# Revised_Schematic.net
KiCad netlist of a schematic drawn in EasyEDA Pro
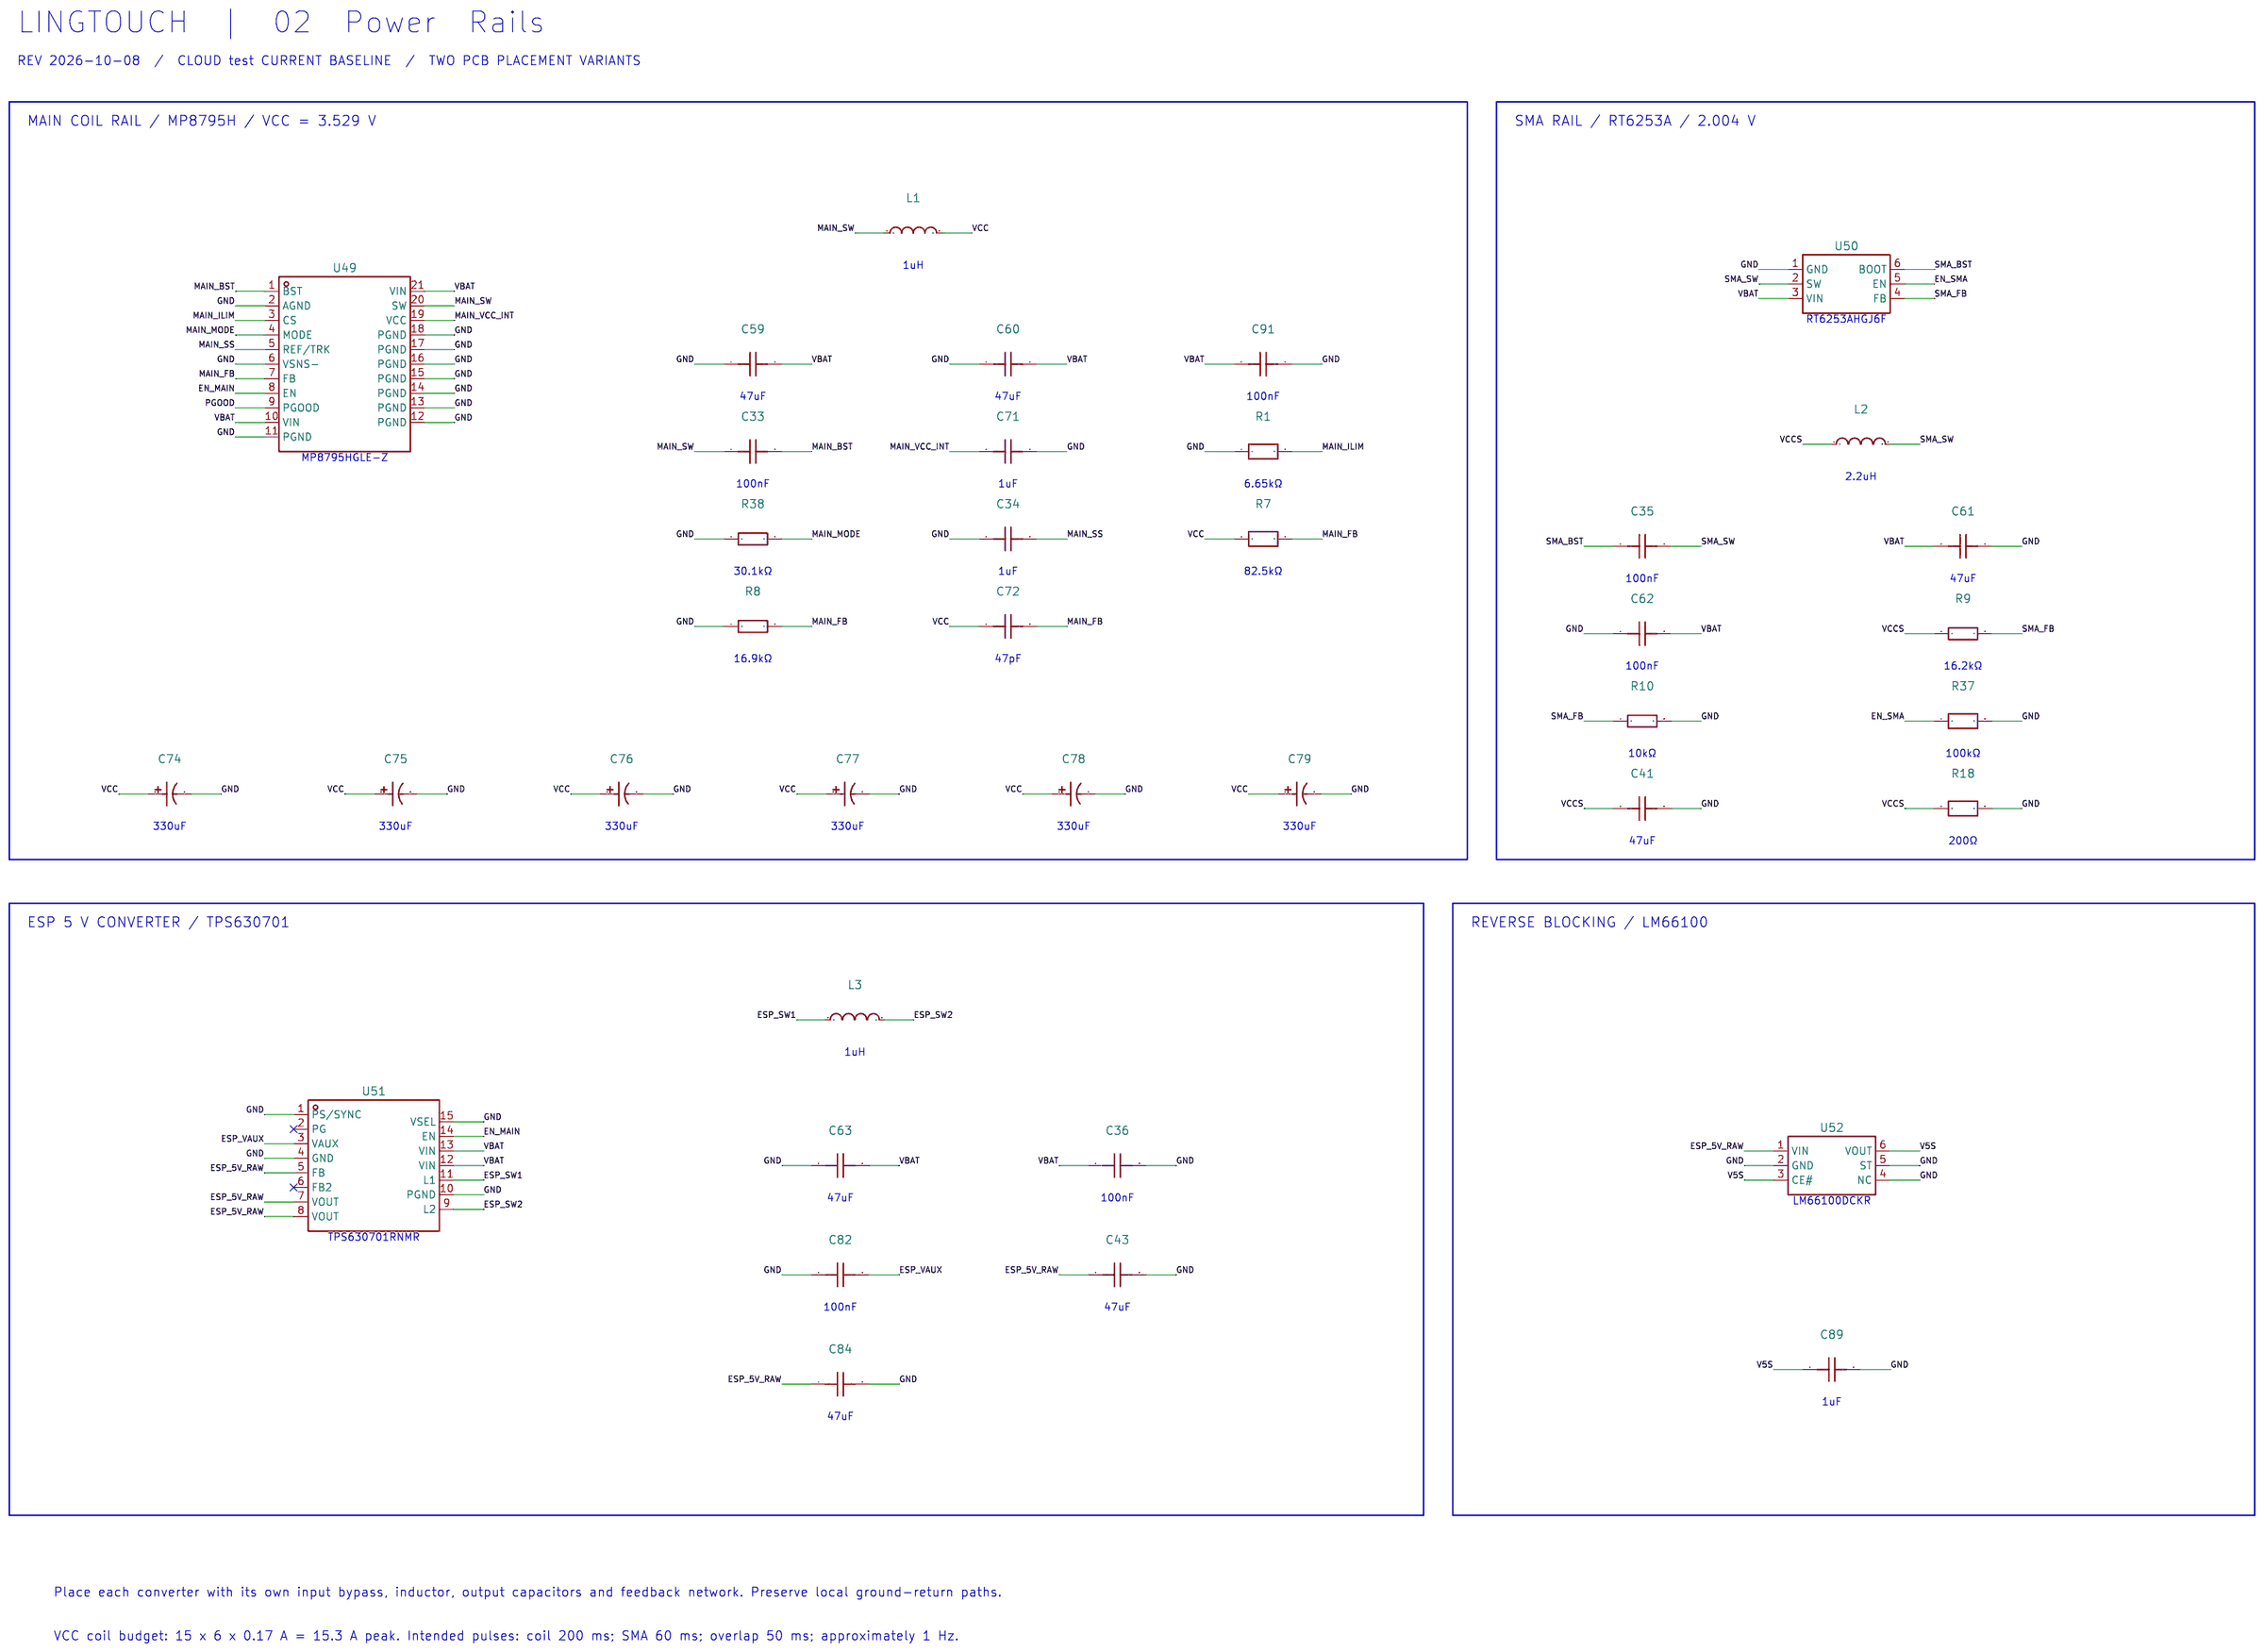
[diagram p0: 02_Power_Rails]
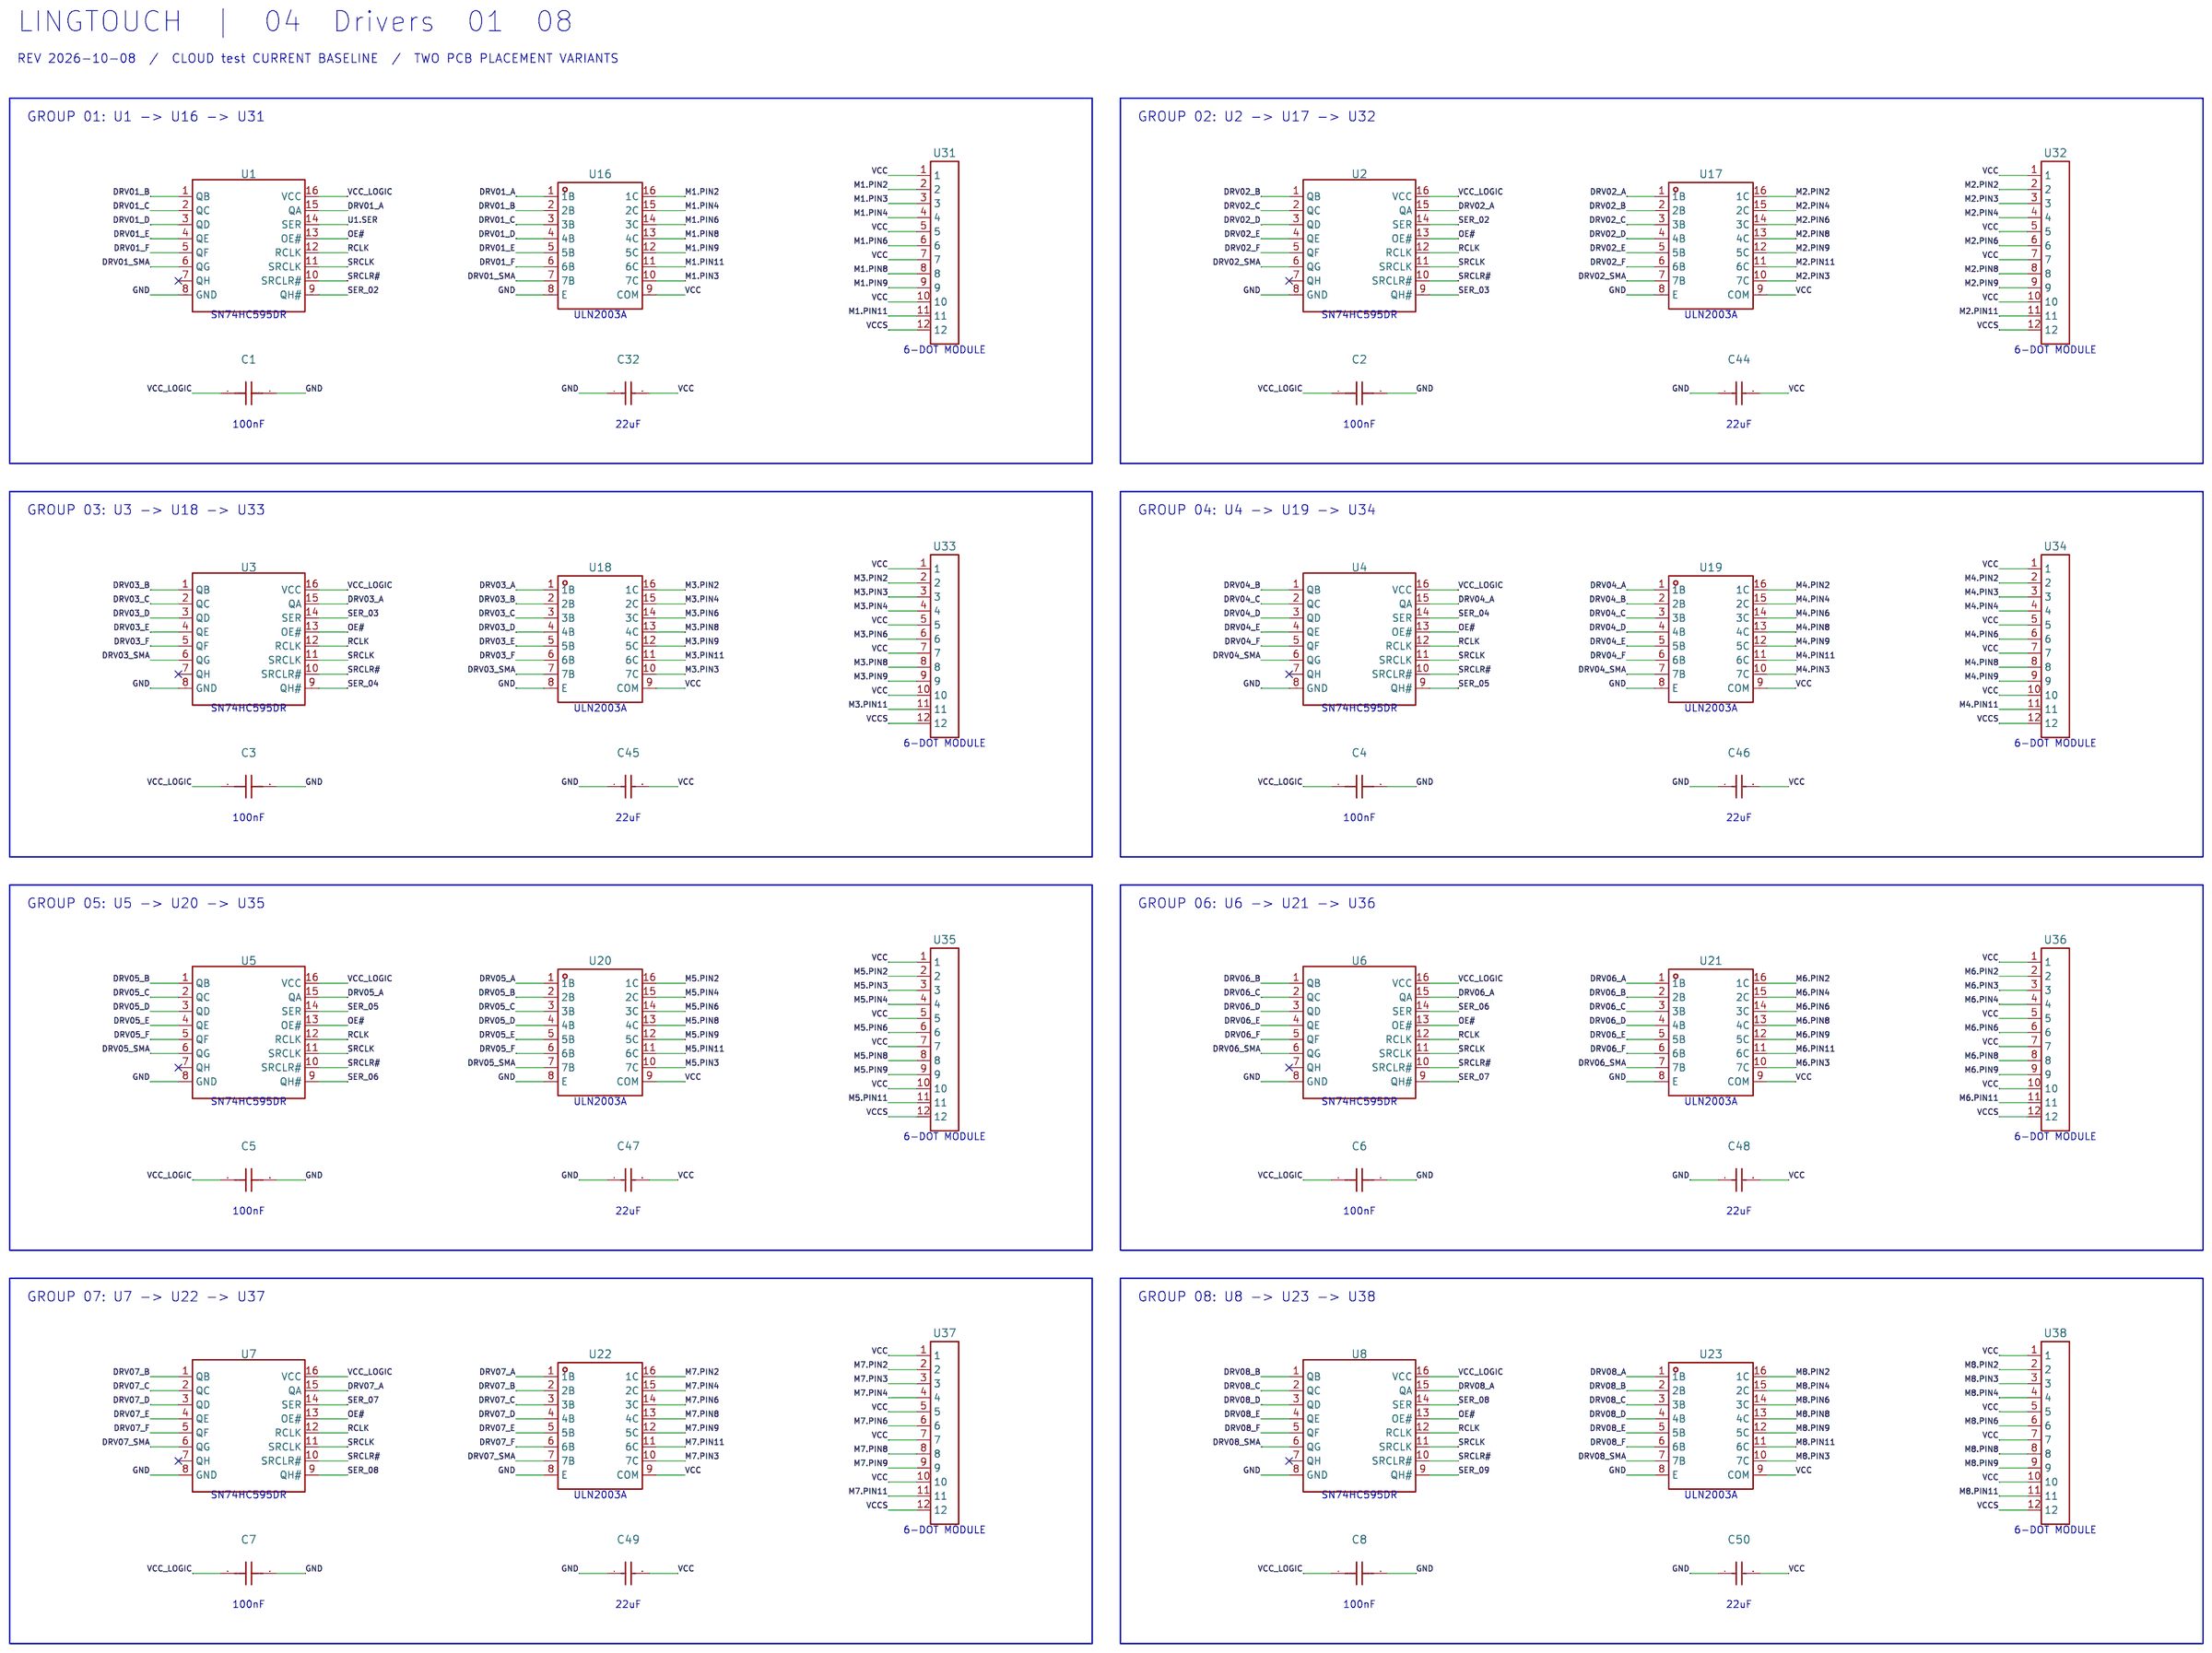
[diagram p1: 04_Drivers_01_08]
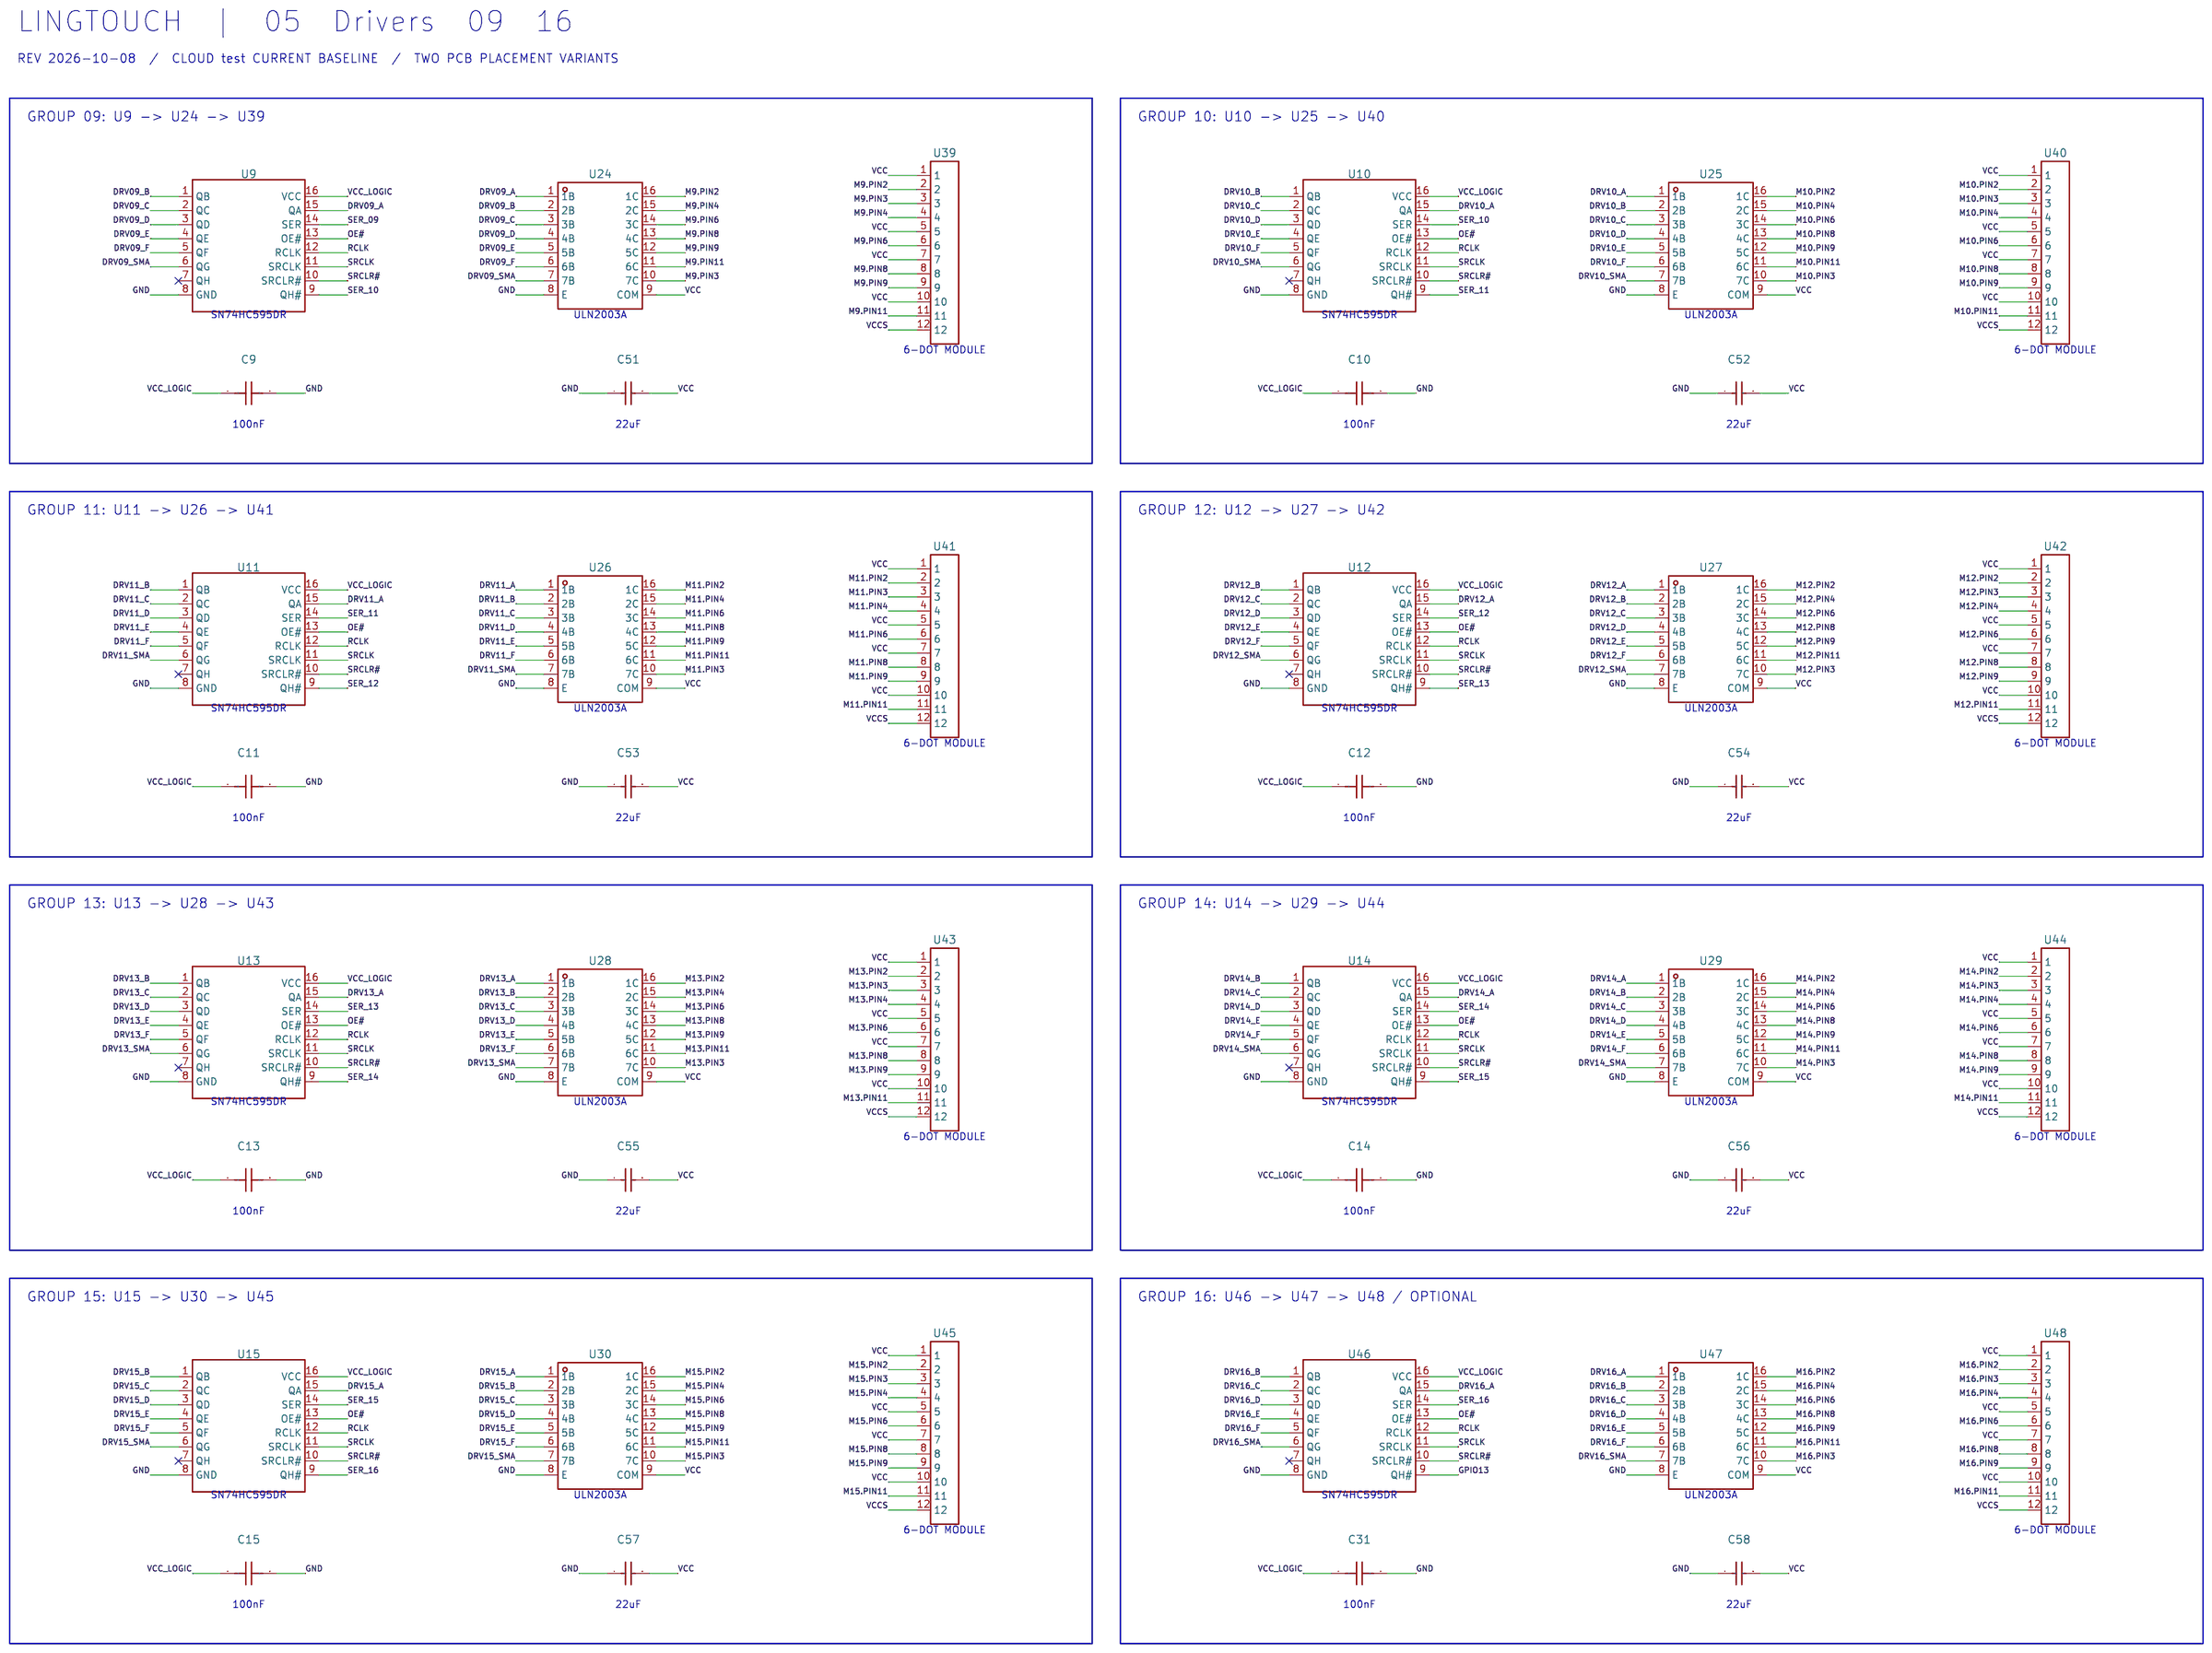
[diagram p2: 05_Drivers_09_16]
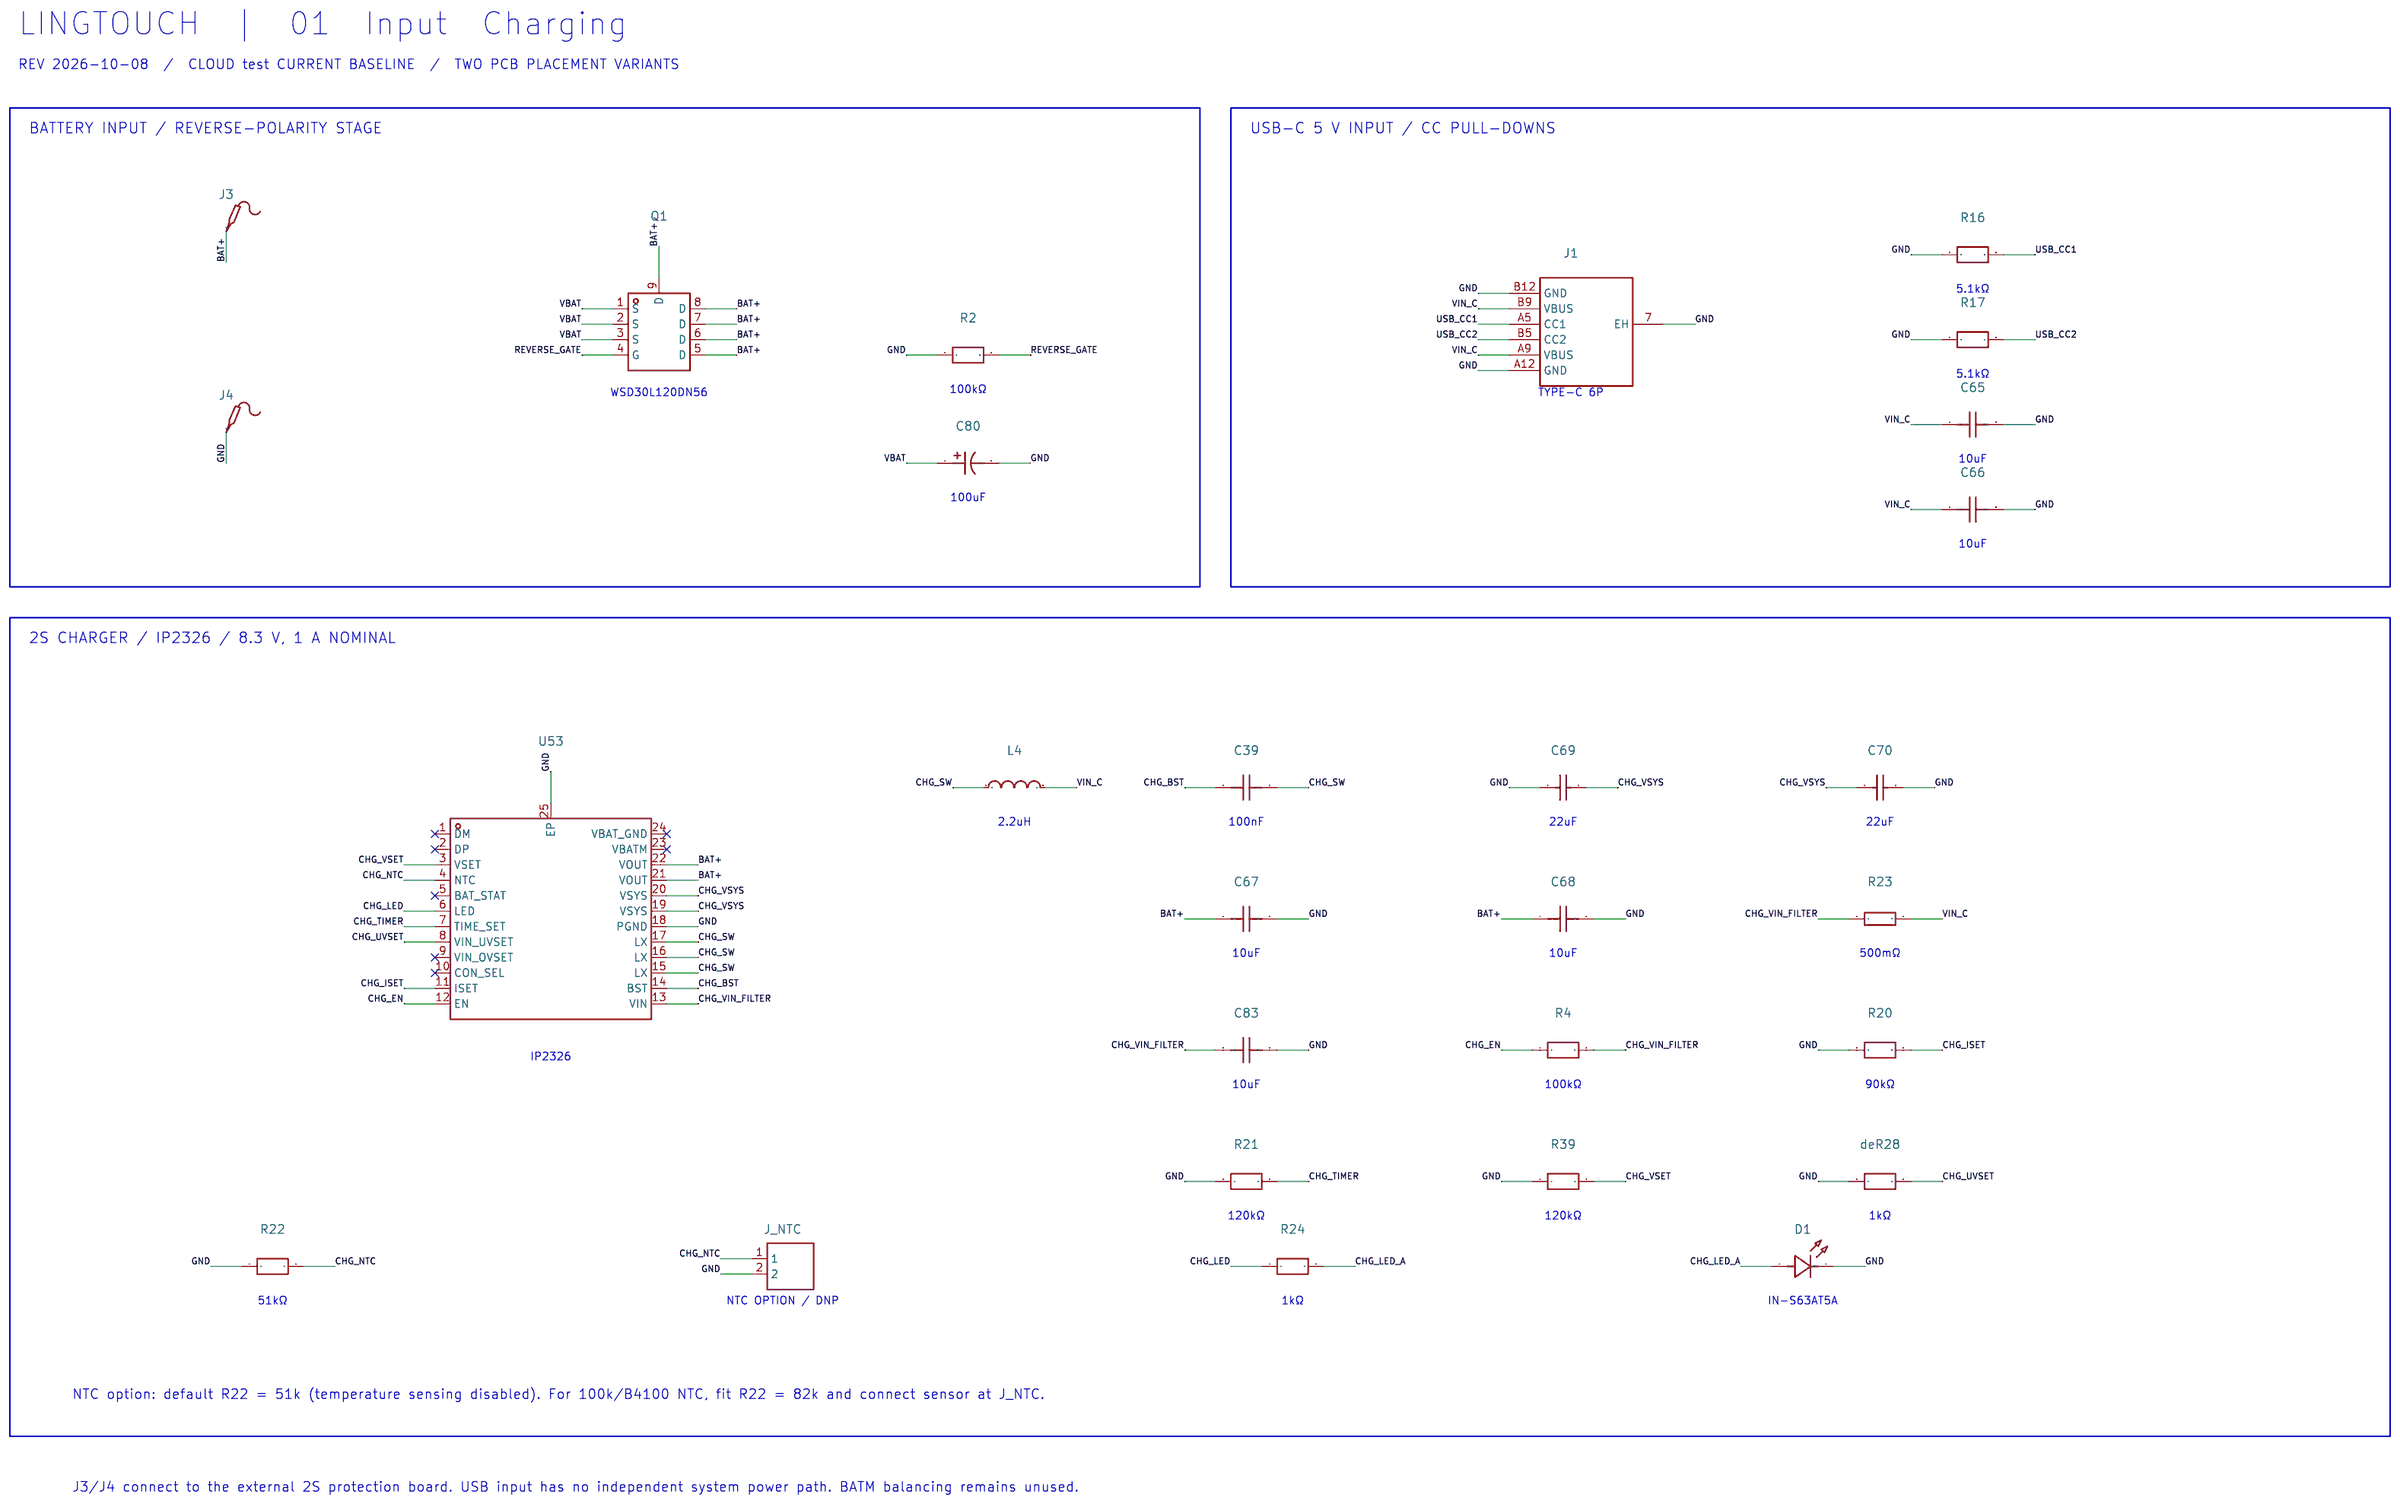
[diagram p3: 01_Input_Charging]
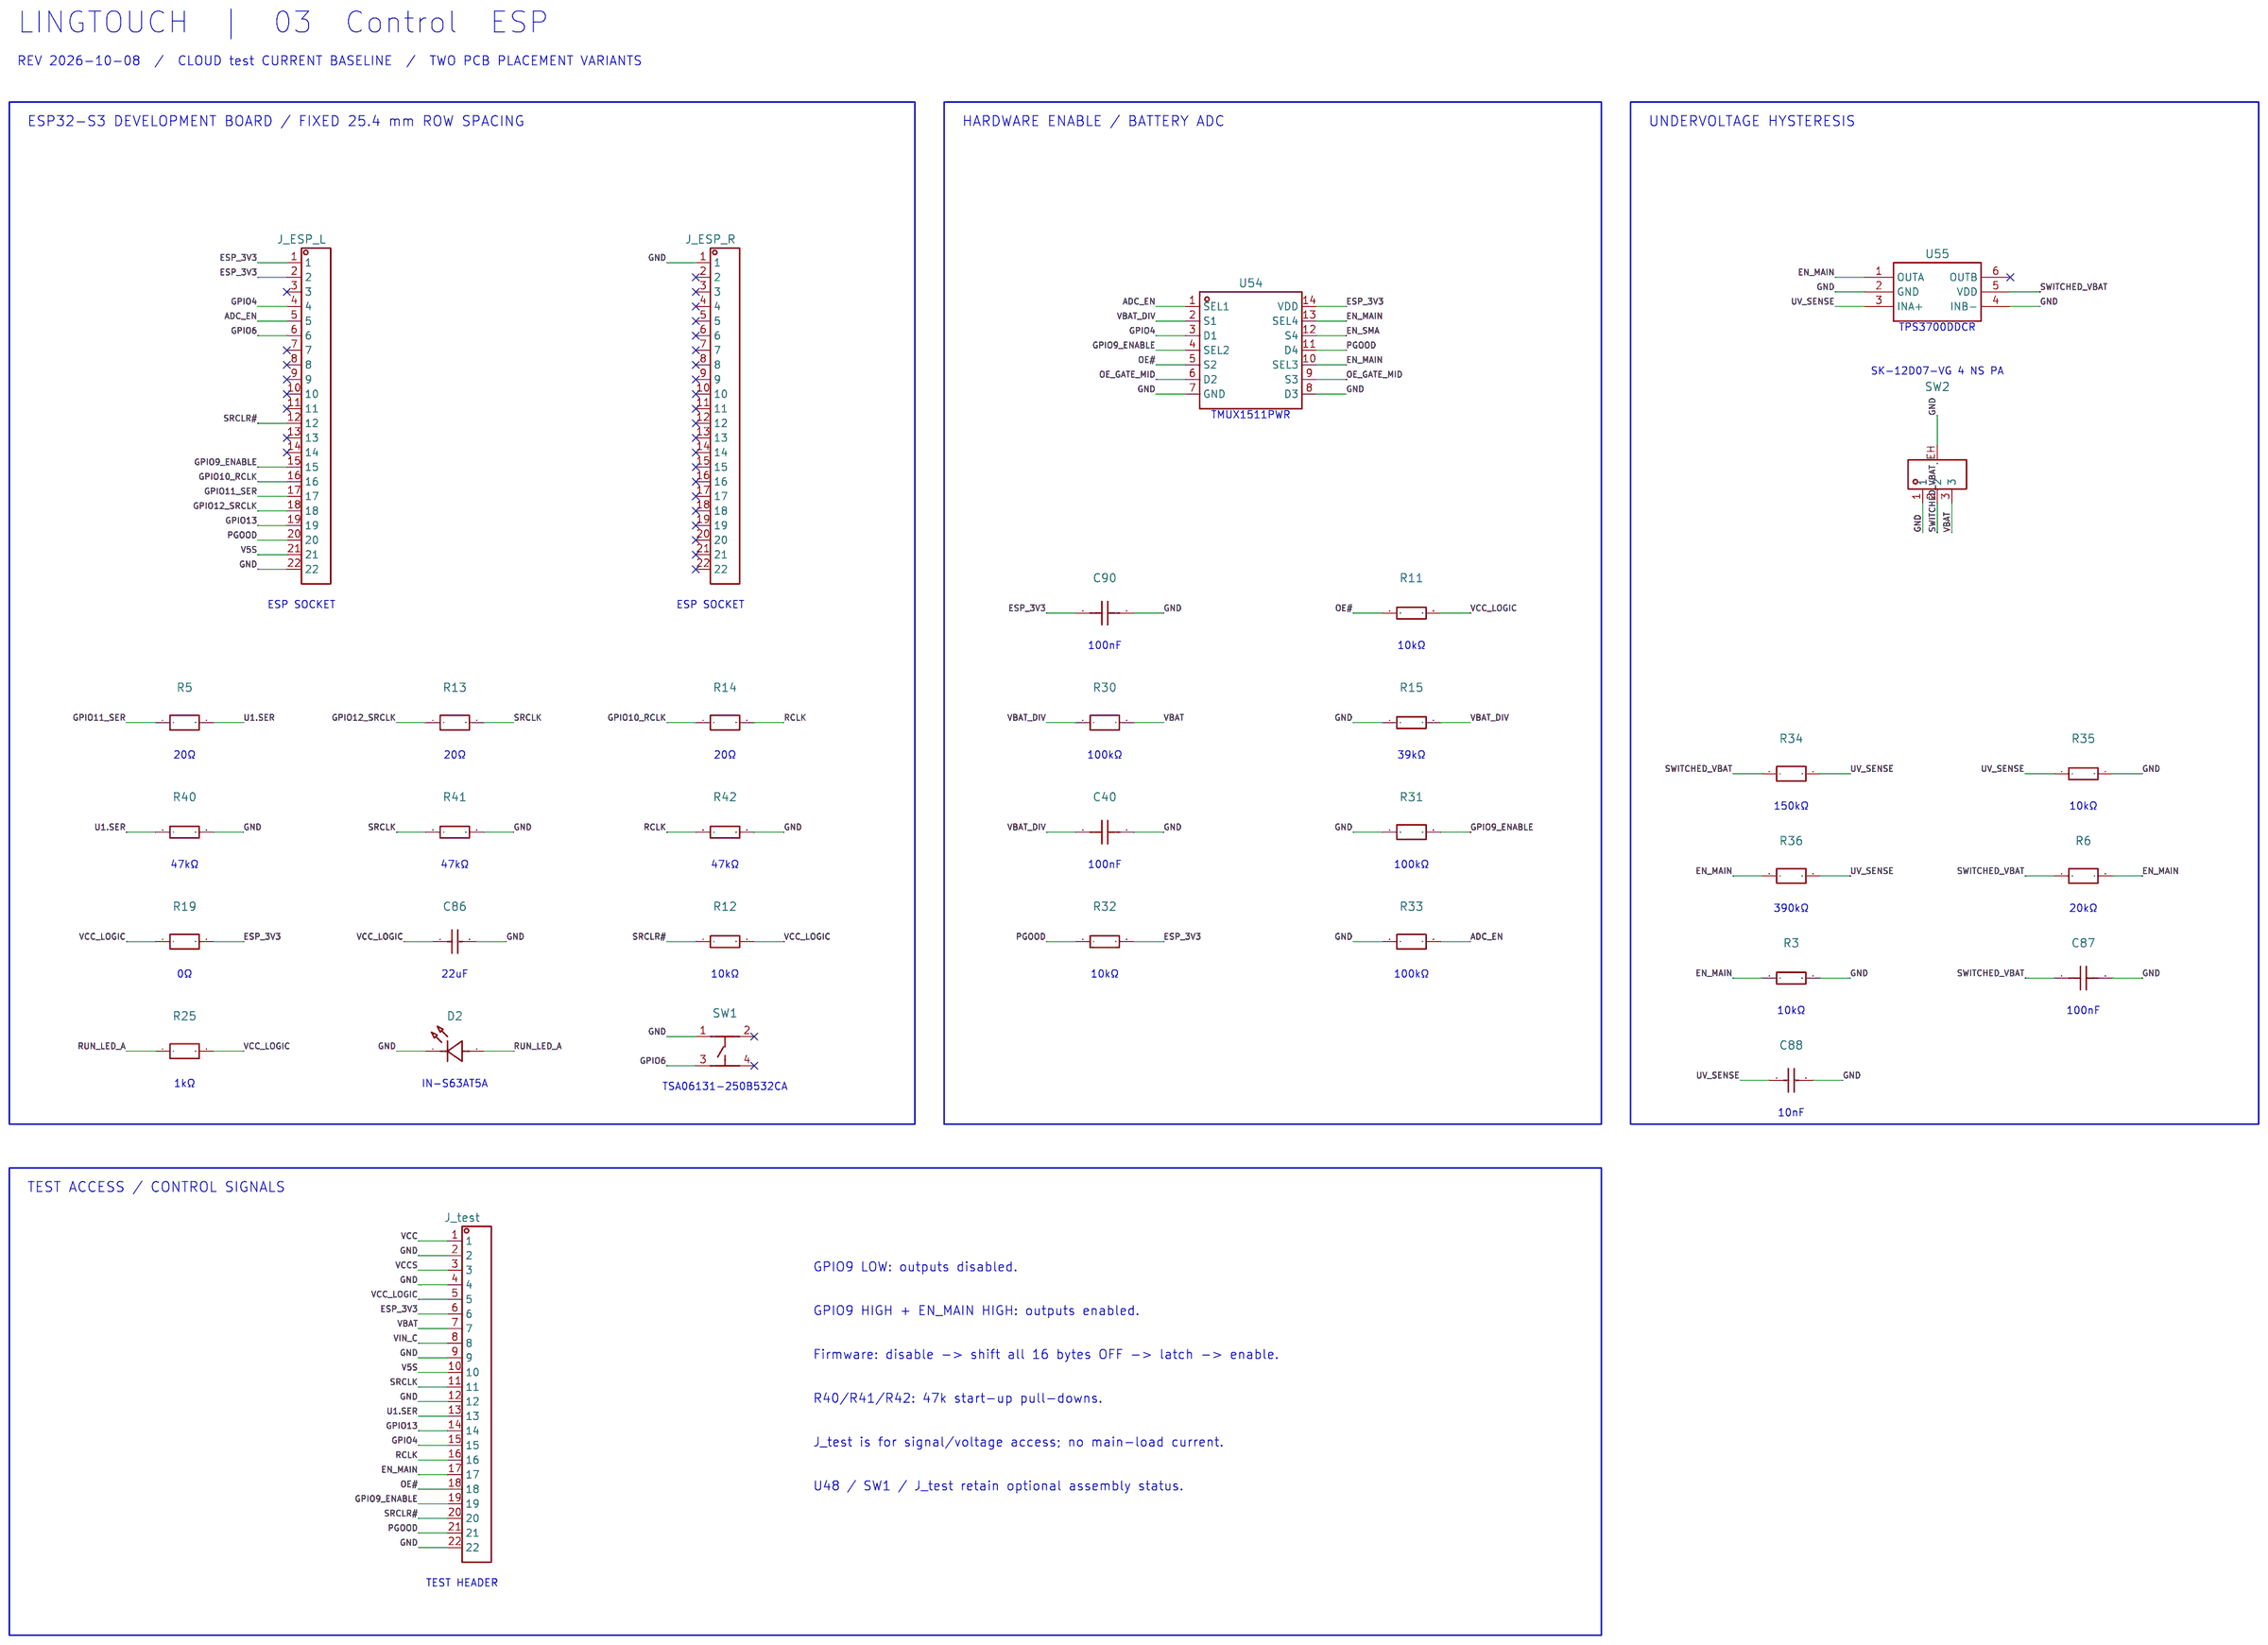
[diagram p4: 03_Control_ESP]

(export (version "E")
  (design (tool "Eeschema 10.0.6"))
  (components
    (comp (ref "C33")
      (value "100nF")
      (footprint "easyedapro:C0603")
      (description "容值:100nF;精度:±10%;额定电压:50V;温度系数:X7R;")
      (fields
        (field (name "Manufacturer Part") "CGA0603X7R104K500JT")
        (field (name "Manufacturer") "HRE(芯声)")
      )
      (libsource (lib "easyedapro") (part "CGA0603X7R104K500JT"))
    )
    (comp (ref "C34")
      (value "1uF")
      (footprint "easyedapro:C0603")
      (description "容值:1uF;精度:±10%;额定电压:16V;温度系数:X7R;")
      (fields
        (field (name "Manufacturer Part") "FCC0603B105K160CT")
        (field (name "Manufacturer") "FOJAN(富捷)")
      )
      (libsource (lib "easyedapro") (part "FCC0603B105K160CT"))
    )
    (comp (ref "C35")
      (value "100nF")
      (footprint "easyedapro:C0603")
      (description "容值:100nF;精度:±10%;额定电压:50V;温度系数:X7R;")
      (fields
        (field (name "Manufacturer Part") "CGA0603X7R104K500JT")
        (field (name "Manufacturer") "HRE(芯声)")
      )
      (libsource (lib "easyedapro") (part "CGA0603X7R104K500JT"))
    )
    (comp (ref "C36")
      (value "100nF")
      (footprint "easyedapro:C0603")
      (description "容值:100nF;精度:±10%;额定电压:50V;温度系数:X7R;")
      (fields
        (field (name "Manufacturer Part") "CGA0603X7R104K500JT")
        (field (name "Manufacturer") "HRE(芯声)")
      )
      (libsource (lib "easyedapro") (part "CGA0603X7R104K500JT"))
    )
    (comp (ref "C41")
      (value "47uF")
      (footprint "easyedapro:C1210")
      (fields
        (field (name "Manufacturer Part") "GRM32ER61C476KE15L")
        (field (name "Manufacturer") "muRata(村田)")
      )
      (libsource (lib "easyedapro") (part "GRM32ER61C476KE15L"))
    )
    (comp (ref "C43")
      (value "47uF")
      (footprint "easyedapro:C1210")
      (fields
        (field (name "Manufacturer Part") "GRM32ER61C476KE15L")
        (field (name "Manufacturer") "muRata(村田)")
      )
      (libsource (lib "easyedapro") (part "GRM32ER61C476KE15L"))
    )
    (comp (ref "C59")
      (value "47uF")
      (footprint "easyedapro:C1210")
      (fields
        (field (name "Manufacturer Part") "GRM32ER61C476KE15L")
        (field (name "Manufacturer") "muRata(村田)")
      )
      (libsource (lib "easyedapro") (part "GRM32ER61C476KE15L"))
    )
    (comp (ref "C60")
      (value "47uF")
      (footprint "easyedapro:C1210")
      (fields
        (field (name "Manufacturer Part") "GRM32ER61C476KE15L")
        (field (name "Manufacturer") "muRata(村田)")
      )
      (libsource (lib "easyedapro") (part "GRM32ER61C476KE15L"))
    )
    (comp (ref "C61")
      (value "47uF")
      (footprint "easyedapro:C1210")
      (fields
        (field (name "Manufacturer Part") "GRM32ER61C476KE15L")
        (field (name "Manufacturer") "muRata(村田)")
      )
      (libsource (lib "easyedapro") (part "GRM32ER61C476KE15L"))
    )
    (comp (ref "C62")
      (value "100nF")
      (footprint "easyedapro:C0603")
      (description "容值:100nF;精度:±10%;额定电压:50V;温度系数:X7R;")
      (fields
        (field (name "Manufacturer Part") "CGA0603X7R104K500JT")
        (field (name "Manufacturer") "HRE(芯声)")
      )
      (libsource (lib "easyedapro") (part "CGA0603X7R104K500JT"))
    )
    (comp (ref "C63")
      (value "47uF")
      (footprint "easyedapro:C1210")
      (fields
        (field (name "Manufacturer Part") "GRM32ER61C476KE15L")
        (field (name "Manufacturer") "muRata(村田)")
      )
      (libsource (lib "easyedapro") (part "GRM32ER61C476KE15L"))
    )
    (comp (ref "C71")
      (value "1uF")
      (footprint "easyedapro:C0603")
      (description "容值:1uF;精度:±10%;额定电压:16V;温度系数:X7R;")
      (fields
        (field (name "Manufacturer Part") "FCC0603B105K160CT")
        (field (name "Manufacturer") "FOJAN(富捷)")
      )
      (libsource (lib "easyedapro") (part "FCC0603B105K160CT"))
    )
    (comp (ref "C72")
      (value "47pF")
      (footprint "easyedapro:C0603")
      (fields (field (name "Manufacturer Part") "C1608C0G1H470J/10") (field (name "Manufacturer") "TDK"))
      (libsource (lib "easyedapro") (part "C1608C0G1H470J/10"))
    )
    (comp (ref "C74")
      (value "330uF")
      (footprint "easyedapro:CAP-SMD_BD6.3-L6.6-W6.6-FD")
      (description "容值:330uF;精度:±20%;额定电压:6.3V;纹波电流:3.39A@100kHz;等效串联电阻(ESR):17mΩ@100kHz;类型:聚合物;")
      (fields (field (name "Manufacturer Part") "6SVPC330M") (field (name "Manufacturer") "PANASONIC(松下)"))
      (libsource (lib "easyedapro") (part "6SVPC330M"))
    )
    (comp (ref "C75")
      (value "330uF")
      (footprint "easyedapro:CAP-SMD_BD6.3-L6.6-W6.6-FD")
      (description "容值:330uF;精度:±20%;额定电压:6.3V;纹波电流:3.39A@100kHz;等效串联电阻(ESR):17mΩ@100kHz;类型:聚合物;")
      (fields (field (name "Manufacturer Part") "6SVPC330M") (field (name "Manufacturer") "PANASONIC(松下)"))
      (libsource (lib "easyedapro") (part "6SVPC330M"))
    )
    (comp (ref "C76")
      (value "330uF")
      (footprint "easyedapro:CAP-SMD_BD6.3-L6.6-W6.6-FD")
      (description "容值:330uF;精度:±20%;额定电压:6.3V;纹波电流:3.39A@100kHz;等效串联电阻(ESR):17mΩ@100kHz;类型:聚合物;")
      (fields (field (name "Manufacturer Part") "6SVPC330M") (field (name "Manufacturer") "PANASONIC(松下)"))
      (libsource (lib "easyedapro") (part "6SVPC330M"))
    )
    (comp (ref "C77")
      (value "330uF")
      (footprint "easyedapro:CAP-SMD_BD6.3-L6.6-W6.6-FD")
      (description "容值:330uF;精度:±20%;额定电压:6.3V;纹波电流:3.39A@100kHz;等效串联电阻(ESR):17mΩ@100kHz;类型:聚合物;")
      (fields (field (name "Manufacturer Part") "6SVPC330M") (field (name "Manufacturer") "PANASONIC(松下)"))
      (libsource (lib "easyedapro") (part "6SVPC330M"))
    )
    (comp (ref "C78")
      (value "330uF")
      (footprint "easyedapro:CAP-SMD_BD6.3-L6.6-W6.6-FD")
      (description "容值:330uF;精度:±20%;额定电压:6.3V;纹波电流:3.39A@100kHz;等效串联电阻(ESR):17mΩ@100kHz;类型:聚合物;")
      (fields (field (name "Manufacturer Part") "6SVPC330M") (field (name "Manufacturer") "PANASONIC(松下)"))
      (libsource (lib "easyedapro") (part "6SVPC330M"))
    )
    (comp (ref "C79")
      (value "330uF")
      (footprint "easyedapro:CAP-SMD_BD6.3-L6.6-W6.6-FD")
      (description "容值:330uF;精度:±20%;额定电压:6.3V;纹波电流:3.39A@100kHz;等效串联电阻(ESR):17mΩ@100kHz;类型:聚合物;")
      (fields (field (name "Manufacturer Part") "6SVPC330M") (field (name "Manufacturer") "PANASONIC(松下)"))
      (libsource (lib "easyedapro") (part "6SVPC330M"))
    )
    (comp (ref "C82")
      (value "100nF")
      (footprint "easyedapro:C0603")
      (description "容值:100nF;精度:±10%;额定电压:50V;温度系数:X7R;")
      (fields
        (field (name "Manufacturer Part") "CGA0603X7R104K500JT")
        (field (name "Manufacturer") "HRE(芯声)")
      )
      (libsource (lib "easyedapro") (part "CGA0603X7R104K500JT"))
    )
    (comp (ref "C84")
      (value "47uF")
      (footprint "easyedapro:C1210")
      (fields
        (field (name "Manufacturer Part") "GRM32ER61C476KE15L")
        (field (name "Manufacturer") "muRata(村田)")
      )
      (libsource (lib "easyedapro") (part "GRM32ER61C476KE15L"))
    )
    (comp (ref "C89")
      (value "1uF")
      (footprint "easyedapro:C0603")
      (description "容值:1uF;精度:±10%;额定电压:16V;温度系数:X7R;")
      (fields
        (field (name "Manufacturer Part") "FCC0603B105K160CT")
        (field (name "Manufacturer") "FOJAN(富捷)")
      )
      (libsource (lib "easyedapro") (part "FCC0603B105K160CT"))
    )
    (comp (ref "C91")
      (value "100nF")
      (footprint "easyedapro:C0603")
      (description "容值:100nF;精度:±10%;额定电压:50V;温度系数:X7R;")
      (fields
        (field (name "Manufacturer Part") "CGA0603X7R104K500JT")
        (field (name "Manufacturer") "HRE(芯声)")
      )
      (libsource (lib "easyedapro") (part "CGA0603X7R104K500JT"))
    )
    (comp (ref "L1")
      (value "1uH")
      (footprint "easyedapro:IND-SMD_YSPI1365-1R0M")
      (description "电感值:1uH;精度:±20%;饱和电流(Isat):36A;")
      (fields (field (name "Manufacturer Part") "YSPI1365-1R0M") (field (name "Manufacturer") "YJYCOIN(益嘉源)"))
      (libsource (lib "easyedapro") (part "YSPI1365-1R0M"))
    )
    (comp (ref "L2")
      (value "2.2uH")
      (footprint "easyedapro:IND-SMD_L5.3-W5.1")
      (description "电感值:2.2uH;精度:±20%;额定电流:6.6A;饱和电流(Isat):9A;")
      (fields (field (name "Manufacturer Part") "SPM5030VT-2R2M-D") (field (name "Manufacturer") "TDK"))
      (libsource (lib "easyedapro") (part "SPM5030VT-2R2M-D"))
    )
    (comp (ref "L3")
      (value "1uH")
      (footprint "easyedapro:IND-SMD_L5.4-W5.1_SPM5020T-100M-LR")
      (fields (field (name "Manufacturer Part") "SPM5030VT-1R0M-D") (field (name "Manufacturer") "TDK"))
      (libsource (lib "easyedapro") (part "SPM5030VT-1R0M-D"))
    )
    (comp (ref "R1")
      (value "6.65kΩ")
      (footprint "easyedapro:R0603")
      (fields (field (name "Manufacturer Part") "PTFR0603B6K65P9") (field (name "Manufacturer") "RESI(开步睿思)"))
      (libsource (lib "easyedapro") (part "PTFR0603B6K65P9"))
    )
    (comp (ref "R7")
      (value "82.5kΩ")
      (footprint "easyedapro:R0603")
      (fields (field (name "Manufacturer Part") "FRC0603F8252TS") (field (name "Manufacturer") "FOJAN(富捷)"))
      (libsource (lib "easyedapro") (part "FRC0603F8252TS"))
    )
    (comp (ref "R8")
      (value "16.9kΩ")
      (footprint "easyedapro:R0603")
      (fields
        (field (name "Manufacturer Part") "0603WAF1692T5E")
        (field (name "Manufacturer") "UNI-ROYAL(厚声)")
      )
      (libsource (lib "easyedapro") (part "0603WAF1692T5E"))
    )
    (comp (ref "R9")
      (value "16.2kΩ")
      (footprint "easyedapro:R0603")
      (fields
        (field (name "Manufacturer Part") "0603WAF1622T5E")
        (field (name "Manufacturer") "UNI-ROYAL(厚声)")
      )
      (libsource (lib "easyedapro") (part "0603WAF1622T5E"))
    )
    (comp (ref "R10")
      (value "10kΩ")
      (footprint "easyedapro:R0603")
      (fields (field (name "Manufacturer Part") "RT0603BRD0710KL") (field (name "Manufacturer") "YAGEO(国巨)"))
      (libsource (lib "easyedapro") (part "RT0603BRD0710KL"))
    )
    (comp (ref "R18")
      (value "200Ω")
      (footprint "easyedapro:R0603")
      (fields (field (name "Manufacturer Part") "RCA03200RFLF") (field (name "Manufacturer") "HKR(香港电阻)"))
      (libsource (lib "easyedapro") (part "RCA03200RFLF"))
    )
    (comp (ref "R37")
      (value "100kΩ")
      (footprint "easyedapro:R0603")
      (fields (field (name "Manufacturer Part") "RCA03100KFLF") (field (name "Manufacturer") "HKR(香港电阻)"))
      (libsource (lib "easyedapro") (part "RCA03100KFLF"))
    )
    (comp (ref "R38")
      (value "30.1kΩ")
      (footprint "easyedapro:R0603")
      (fields
        (field (name "Manufacturer Part") "0603WAF3012T5E")
        (field (name "Manufacturer") "UNI-ROYAL(厚声)")
      )
      (libsource (lib "easyedapro") (part "0603WAF3012T5E"))
    )
    (comp (ref "U49")
      (value "MP8795HGLE-Z")
      (footprint "easyedapro:TQFN-21_L4.0-W3.0-P0.40-TL_MPQ8633BGLE-Z")
      (description "功能类型:降压型;工作电压:4V~16V;输出电压:600mV~5.5V;输出电流:20A;输出类型:可调;")
      (fields (field (name "Manufacturer") "MPS(芯源)"))
      (libsource (lib "easyedapro") (part "MP8795HGLE-Z"))
    )
    (comp (ref "U50")
      (value "RT6253AHGJ6F")
      (footprint "easyedapro:TSOT-23-6_L2.9-W1.6-P0.95-LS2.8-BR")
      (description "功能类型:降压型;工作电压:4.5V~17V;输出电压:765mV~7V;输出电流:3A;输出类型:可调;")
      (fields (field (name "Manufacturer") "RICHTEK(立锜)"))
      (libsource (lib "easyedapro") (part "RT6253AHGJ6F"))
    )
    (comp (ref "U51")
      (value "TPS630701RNMR")
      (footprint "easyedapro:VQFN-HR-15_L3.0-W2.5-P0.50-BL_TPS63070RNMR")
      (fields (field (name "Manufacturer") "TI(德州仪器)"))
      (libsource (lib "easyedapro") (part "TPS630701RNMR"))
    )
    (comp (ref "U52")
      (value "LM66100DCKR")
      (footprint "easyedapro:SC-70-6_L2.0-W1.3-P0.65-LS2.1-BL")
      (fields (field (name "Manufacturer") "TI(德州仪器)"))
      (libsource (lib "easyedapro") (part "LM66100DCKR"))
    )
    (comp (ref "C1")
      (value "100nF")
      (footprint "easyedapro:C0603")
      (description "容值:100nF;精度:±10%;额定电压:50V;温度系数:X7R;")
      (fields
        (field (name "Manufacturer Part") "CGA0603X7R104K500JT")
        (field (name "Manufacturer") "HRE(芯声)")
      )
      (libsource (lib "easyedapro") (part "CGA0603X7R104K500JT"))
    )
    (comp (ref "C2")
      (value "100nF")
      (footprint "easyedapro:C0603")
      (description "容值:100nF;精度:±10%;额定电压:50V;温度系数:X7R;")
      (fields
        (field (name "Manufacturer Part") "CGA0603X7R104K500JT")
        (field (name "Manufacturer") "HRE(芯声)")
      )
      (libsource (lib "easyedapro") (part "CGA0603X7R104K500JT"))
    )
    (comp (ref "C3")
      (value "100nF")
      (footprint "easyedapro:C0603")
      (description "容值:100nF;精度:±10%;额定电压:50V;温度系数:X7R;")
      (fields
        (field (name "Manufacturer Part") "CGA0603X7R104K500JT")
        (field (name "Manufacturer") "HRE(芯声)")
      )
      (libsource (lib "easyedapro") (part "CGA0603X7R104K500JT"))
    )
    (comp (ref "C4")
      (value "100nF")
      (footprint "easyedapro:C0603")
      (description "容值:100nF;精度:±10%;额定电压:50V;温度系数:X7R;")
      (fields
        (field (name "Manufacturer Part") "CGA0603X7R104K500JT")
        (field (name "Manufacturer") "HRE(芯声)")
      )
      (libsource (lib "easyedapro") (part "CGA0603X7R104K500JT"))
    )
    (comp (ref "C5")
      (value "100nF")
      (footprint "easyedapro:C0603")
      (description "容值:100nF;精度:±10%;额定电压:50V;温度系数:X7R;")
      (fields
        (field (name "Manufacturer Part") "CGA0603X7R104K500JT")
        (field (name "Manufacturer") "HRE(芯声)")
      )
      (libsource (lib "easyedapro") (part "CGA0603X7R104K500JT"))
    )
    (comp (ref "C6")
      (value "100nF")
      (footprint "easyedapro:C0603")
      (description "容值:100nF;精度:±10%;额定电压:50V;温度系数:X7R;")
      (fields
        (field (name "Manufacturer Part") "CGA0603X7R104K500JT")
        (field (name "Manufacturer") "HRE(芯声)")
      )
      (libsource (lib "easyedapro") (part "CGA0603X7R104K500JT"))
    )
    (comp (ref "C7")
      (value "100nF")
      (footprint "easyedapro:C0603")
      (description "容值:100nF;精度:±10%;额定电压:50V;温度系数:X7R;")
      (fields
        (field (name "Manufacturer Part") "CGA0603X7R104K500JT")
        (field (name "Manufacturer") "HRE(芯声)")
      )
      (libsource (lib "easyedapro") (part "CGA0603X7R104K500JT"))
    )
    (comp (ref "C8")
      (value "100nF")
      (footprint "easyedapro:C0603")
      (description "容值:100nF;精度:±10%;额定电压:50V;温度系数:X7R;")
      (fields
        (field (name "Manufacturer Part") "CGA0603X7R104K500JT")
        (field (name "Manufacturer") "HRE(芯声)")
      )
      (libsource (lib "easyedapro") (part "CGA0603X7R104K500JT"))
    )
    (comp (ref "C32")
      (value "22uF")
      (footprint "easyedapro:C1206")
      (fields
        (field (name "Manufacturer Part") "GRM31CR61E226KE15L")
        (field (name "Manufacturer") "muRata(村田)")
      )
      (libsource (lib "easyedapro") (part "GRM31CR61E226KE15L"))
    )
    (comp (ref "C44")
      (value "22uF")
      (footprint "easyedapro:C1206")
      (fields
        (field (name "Manufacturer Part") "GRM31CR61E226KE15L")
        (field (name "Manufacturer") "muRata(村田)")
      )
      (libsource (lib "easyedapro") (part "GRM31CR61E226KE15L"))
    )
    (comp (ref "C45")
      (value "22uF")
      (footprint "easyedapro:C1206")
      (fields
        (field (name "Manufacturer Part") "GRM31CR61E226KE15L")
        (field (name "Manufacturer") "muRata(村田)")
      )
      (libsource (lib "easyedapro") (part "GRM31CR61E226KE15L"))
    )
    (comp (ref "C46")
      (value "22uF")
      (footprint "easyedapro:C1206")
      (fields
        (field (name "Manufacturer Part") "GRM31CR61E226KE15L")
        (field (name "Manufacturer") "muRata(村田)")
      )
      (libsource (lib "easyedapro") (part "GRM31CR61E226KE15L"))
    )
    (comp (ref "C47")
      (value "22uF")
      (footprint "easyedapro:C1206")
      (fields
        (field (name "Manufacturer Part") "GRM31CR61E226KE15L")
        (field (name "Manufacturer") "muRata(村田)")
      )
      (libsource (lib "easyedapro") (part "GRM31CR61E226KE15L"))
    )
    (comp (ref "C48")
      (value "22uF")
      (footprint "easyedapro:C1206")
      (fields
        (field (name "Manufacturer Part") "GRM31CR61E226KE15L")
        (field (name "Manufacturer") "muRata(村田)")
      )
      (libsource (lib "easyedapro") (part "GRM31CR61E226KE15L"))
    )
    (comp (ref "C49")
      (value "22uF")
      (footprint "easyedapro:C1206")
      (fields
        (field (name "Manufacturer Part") "GRM31CR61E226KE15L")
        (field (name "Manufacturer") "muRata(村田)")
      )
      (libsource (lib "easyedapro") (part "GRM31CR61E226KE15L"))
    )
    (comp (ref "C50")
      (value "22uF")
      (footprint "easyedapro:C1206")
      (fields
        (field (name "Manufacturer Part") "GRM31CR61E226KE15L")
        (field (name "Manufacturer") "muRata(村田)")
      )
      (libsource (lib "easyedapro") (part "GRM31CR61E226KE15L"))
    )
    (comp (ref "U1")
      (value "SN74HC595DR")
      (footprint "easyedapro:SOIC-16_L9.9-W3.9-P1.27-LS6.0-BL")
      (description "功能:串行至串行或并行;工作电压:2V~6V;时钟频率(fc):29MHz;元件数:1;每个元件位数:8;")
      (fields (field (name "Manufacturer") "TI(德州仪器)"))
      (libsource (lib "easyedapro") (part "SN74HC595DR"))
    )
    (comp (ref "U2")
      (value "SN74HC595DR")
      (footprint "easyedapro:SOIC-16_L9.9-W3.9-P1.27-LS6.0-BL")
      (description "功能:串行至串行或并行;工作电压:2V~6V;时钟频率(fc):29MHz;元件数:1;每个元件位数:8;")
      (fields (field (name "Manufacturer") "TI(德州仪器)"))
      (libsource (lib "easyedapro") (part "SN74HC595DR"))
    )
    (comp (ref "U3")
      (value "SN74HC595DR")
      (footprint "easyedapro:SOIC-16_L9.9-W3.9-P1.27-LS6.0-BL")
      (description "功能:串行至串行或并行;工作电压:2V~6V;时钟频率(fc):29MHz;元件数:1;每个元件位数:8;")
      (fields (field (name "Manufacturer") "TI(德州仪器)"))
      (libsource (lib "easyedapro") (part "SN74HC595DR"))
    )
    (comp (ref "U4")
      (value "SN74HC595DR")
      (footprint "easyedapro:SOIC-16_L9.9-W3.9-P1.27-LS6.0-BL")
      (description "功能:串行至串行或并行;工作电压:2V~6V;时钟频率(fc):29MHz;元件数:1;每个元件位数:8;")
      (fields (field (name "Manufacturer") "TI(德州仪器)"))
      (libsource (lib "easyedapro") (part "SN74HC595DR"))
    )
    (comp (ref "U5")
      (value "SN74HC595DR")
      (footprint "easyedapro:SOIC-16_L9.9-W3.9-P1.27-LS6.0-BL")
      (description "功能:串行至串行或并行;工作电压:2V~6V;时钟频率(fc):29MHz;元件数:1;每个元件位数:8;")
      (fields (field (name "Manufacturer") "TI(德州仪器)"))
      (libsource (lib "easyedapro") (part "SN74HC595DR"))
    )
    (comp (ref "U6")
      (value "SN74HC595DR")
      (footprint "easyedapro:SOIC-16_L9.9-W3.9-P1.27-LS6.0-BL")
      (description "功能:串行至串行或并行;工作电压:2V~6V;时钟频率(fc):29MHz;元件数:1;每个元件位数:8;")
      (fields (field (name "Manufacturer") "TI(德州仪器)"))
      (libsource (lib "easyedapro") (part "SN74HC595DR"))
    )
    (comp (ref "U7")
      (value "SN74HC595DR")
      (footprint "easyedapro:SOIC-16_L9.9-W3.9-P1.27-LS6.0-BL")
      (description "功能:串行至串行或并行;工作电压:2V~6V;时钟频率(fc):29MHz;元件数:1;每个元件位数:8;")
      (fields (field (name "Manufacturer") "TI(德州仪器)"))
      (libsource (lib "easyedapro") (part "SN74HC595DR"))
    )
    (comp (ref "U8")
      (value "SN74HC595DR")
      (footprint "easyedapro:SOIC-16_L9.9-W3.9-P1.27-LS6.0-BL")
      (description "功能:串行至串行或并行;工作电压:2V~6V;时钟频率(fc):29MHz;元件数:1;每个元件位数:8;")
      (fields (field (name "Manufacturer") "TI(德州仪器)"))
      (libsource (lib "easyedapro") (part "SN74HC595DR"))
    )
    (comp (ref "U16")
      (value "ULN2003A")
      (footprint "easyedapro:SOP-16_L10.0-W3.9-P1.27-LS6.0-BL")
      (description "通道数:七路;集射极击穿电压(Vceo):50V;集电极电流(Ic):500mA;")
      (fields (field (name "Manufacturer") "Mixic(中科芯亿达)"))
      (libsource (lib "easyedapro") (part "ULN2003A_C181730"))
    )
    (comp (ref "U17")
      (value "ULN2003A")
      (footprint "easyedapro:SOP-16_L10.0-W3.9-P1.27-LS6.0-BL")
      (description "通道数:七路;集射极击穿电压(Vceo):50V;集电极电流(Ic):500mA;")
      (fields (field (name "Manufacturer") "Mixic(中科芯亿达)"))
      (libsource (lib "easyedapro") (part "ULN2003A_C181730"))
    )
    (comp (ref "U18")
      (value "ULN2003A")
      (footprint "easyedapro:SOP-16_L10.0-W3.9-P1.27-LS6.0-BL")
      (description "通道数:七路;集射极击穿电压(Vceo):50V;集电极电流(Ic):500mA;")
      (fields (field (name "Manufacturer") "Mixic(中科芯亿达)"))
      (libsource (lib "easyedapro") (part "ULN2003A_C181730"))
    )
    (comp (ref "U19")
      (value "ULN2003A")
      (footprint "easyedapro:SOP-16_L10.0-W3.9-P1.27-LS6.0-BL")
      (description "通道数:七路;集射极击穿电压(Vceo):50V;集电极电流(Ic):500mA;")
      (fields (field (name "Manufacturer") "Mixic(中科芯亿达)"))
      (libsource (lib "easyedapro") (part "ULN2003A_C181730"))
    )
    (comp (ref "U20")
      (value "ULN2003A")
      (footprint "easyedapro:SOP-16_L10.0-W3.9-P1.27-LS6.0-BL")
      (description "通道数:七路;集射极击穿电压(Vceo):50V;集电极电流(Ic):500mA;")
      (fields (field (name "Manufacturer") "Mixic(中科芯亿达)"))
      (libsource (lib "easyedapro") (part "ULN2003A_C181730"))
    )
    (comp (ref "U21")
      (value "ULN2003A")
      (footprint "easyedapro:SOP-16_L10.0-W3.9-P1.27-LS6.0-BL")
      (description "通道数:七路;集射极击穿电压(Vceo):50V;集电极电流(Ic):500mA;")
      (fields (field (name "Manufacturer") "Mixic(中科芯亿达)"))
      (libsource (lib "easyedapro") (part "ULN2003A_C181730"))
    )
    (comp (ref "U22")
      (value "ULN2003A")
      (footprint "easyedapro:SOP-16_L10.0-W3.9-P1.27-LS6.0-BL")
      (description "通道数:七路;集射极击穿电压(Vceo):50V;集电极电流(Ic):500mA;")
      (fields (field (name "Manufacturer") "Mixic(中科芯亿达)"))
      (libsource (lib "easyedapro") (part "ULN2003A_C181730"))
    )
    (comp (ref "U23")
      (value "ULN2003A")
      (footprint "easyedapro:SOP-16_L10.0-W3.9-P1.27-LS6.0-BL")
      (description "通道数:七路;集射极击穿电压(Vceo):50V;集电极电流(Ic):500mA;")
      (fields (field (name "Manufacturer") "Mixic(中科芯亿达)"))
      (libsource (lib "easyedapro") (part "ULN2003A_C181730"))
    )
    (comp (ref "U31")
      (value "HC-PM127-4.3H-1x12PZ")
      (footprint "easyedapro:HDR-TH_12P-P1.27-V-F")
      (fields (field (name "Manufacturer") "HC(虹成电子)"))
      (libsource (lib "easyedapro") (part "HC-PM127-4.3H-1X12PZ"))
    )
    (comp (ref "U32")
      (value "HC-PM127-4.3H-1x12PZ")
      (footprint "easyedapro:HDR-TH_12P-P1.27-V-F")
      (fields (field (name "Manufacturer") "HC(虹成电子)"))
      (libsource (lib "easyedapro") (part "HC-PM127-4.3H-1X12PZ"))
    )
    (comp (ref "U33")
      (value "HC-PM127-4.3H-1x12PZ")
      (footprint "easyedapro:HDR-TH_12P-P1.27-V-F")
      (fields (field (name "Manufacturer") "HC(虹成电子)"))
      (libsource (lib "easyedapro") (part "HC-PM127-4.3H-1X12PZ"))
    )
    (comp (ref "U34")
      (value "HC-PM127-4.3H-1x12PZ")
      (footprint "easyedapro:HDR-TH_12P-P1.27-V-F")
      (fields (field (name "Manufacturer") "HC(虹成电子)"))
      (libsource (lib "easyedapro") (part "HC-PM127-4.3H-1X12PZ"))
    )
    (comp (ref "U35")
      (value "HC-PM127-4.3H-1x12PZ")
      (footprint "easyedapro:HDR-TH_12P-P1.27-V-F")
      (fields (field (name "Manufacturer") "HC(虹成电子)"))
      (libsource (lib "easyedapro") (part "HC-PM127-4.3H-1X12PZ"))
    )
    (comp (ref "U36")
      (value "HC-PM127-4.3H-1x12PZ")
      (footprint "easyedapro:HDR-TH_12P-P1.27-V-F")
      (fields (field (name "Manufacturer") "HC(虹成电子)"))
      (libsource (lib "easyedapro") (part "HC-PM127-4.3H-1X12PZ"))
    )
    (comp (ref "U37")
      (value "HC-PM127-4.3H-1x12PZ")
      (footprint "easyedapro:HDR-TH_12P-P1.27-V-F")
      (fields (field (name "Manufacturer") "HC(虹成电子)"))
      (libsource (lib "easyedapro") (part "HC-PM127-4.3H-1X12PZ"))
    )
    (comp (ref "U38")
      (value "HC-PM127-4.3H-1x12PZ")
      (footprint "easyedapro:HDR-TH_12P-P1.27-V-F")
      (fields (field (name "Manufacturer") "HC(虹成电子)"))
      (libsource (lib "easyedapro") (part "HC-PM127-4.3H-1X12PZ"))
    )
    (comp (ref "C9")
      (value "100nF")
      (footprint "easyedapro:C0603")
      (description "容值:100nF;精度:±10%;额定电压:50V;温度系数:X7R;")
      (fields
        (field (name "Manufacturer Part") "CGA0603X7R104K500JT")
        (field (name "Manufacturer") "HRE(芯声)")
      )
      (libsource (lib "easyedapro") (part "CGA0603X7R104K500JT"))
    )
    (comp (ref "C10")
      (value "100nF")
      (footprint "easyedapro:C0603")
      (description "容值:100nF;精度:±10%;额定电压:50V;温度系数:X7R;")
      (fields
        (field (name "Manufacturer Part") "CGA0603X7R104K500JT")
        (field (name "Manufacturer") "HRE(芯声)")
      )
      (libsource (lib "easyedapro") (part "CGA0603X7R104K500JT"))
    )
    (comp (ref "C11")
      (value "100nF")
      (footprint "easyedapro:C0603")
      (description "容值:100nF;精度:±10%;额定电压:50V;温度系数:X7R;")
      (fields
        (field (name "Manufacturer Part") "CGA0603X7R104K500JT")
        (field (name "Manufacturer") "HRE(芯声)")
      )
      (libsource (lib "easyedapro") (part "CGA0603X7R104K500JT"))
    )
    (comp (ref "C12")
      (value "100nF")
      (footprint "easyedapro:C0603")
      (description "容值:100nF;精度:±10%;额定电压:50V;温度系数:X7R;")
      (fields
        (field (name "Manufacturer Part") "CGA0603X7R104K500JT")
        (field (name "Manufacturer") "HRE(芯声)")
      )
      (libsource (lib "easyedapro") (part "CGA0603X7R104K500JT"))
    )
    (comp (ref "C13")
      (value "100nF")
      (footprint "easyedapro:C0603")
      (description "容值:100nF;精度:±10%;额定电压:50V;温度系数:X7R;")
      (fields
        (field (name "Manufacturer Part") "CGA0603X7R104K500JT")
        (field (name "Manufacturer") "HRE(芯声)")
      )
      (libsource (lib "easyedapro") (part "CGA0603X7R104K500JT"))
    )
    (comp (ref "C14")
      (value "100nF")
      (footprint "easyedapro:C0603")
      (description "容值:100nF;精度:±10%;额定电压:50V;温度系数:X7R;")
      (fields
        (field (name "Manufacturer Part") "CGA0603X7R104K500JT")
        (field (name "Manufacturer") "HRE(芯声)")
      )
      (libsource (lib "easyedapro") (part "CGA0603X7R104K500JT"))
    )
    (comp (ref "C15")
      (value "100nF")
      (footprint "easyedapro:C0603")
      (description "容值:100nF;精度:±10%;额定电压:50V;温度系数:X7R;")
      (fields
        (field (name "Manufacturer Part") "CGA0603X7R104K500JT")
        (field (name "Manufacturer") "HRE(芯声)")
      )
      (libsource (lib "easyedapro") (part "CGA0603X7R104K500JT"))
    )
    (comp (ref "C31")
      (value "100nF")
      (footprint "easyedapro:C0603")
      (description "容值:100nF;精度:±10%;额定电压:50V;温度系数:X7R;")
      (fields
        (field (name "Manufacturer Part") "CGA0603X7R104K500JT")
        (field (name "Manufacturer") "HRE(芯声)")
      )
      (libsource (lib "easyedapro") (part "CGA0603X7R104K500JT"))
    )
    (comp (ref "C51")
      (value "22uF")
      (footprint "easyedapro:C1206")
      (fields
        (field (name "Manufacturer Part") "GRM31CR61E226KE15L")
        (field (name "Manufacturer") "muRata(村田)")
      )
      (libsource (lib "easyedapro") (part "GRM31CR61E226KE15L"))
    )
    (comp (ref "C52")
      (value "22uF")
      (footprint "easyedapro:C1206")
      (fields
        (field (name "Manufacturer Part") "GRM31CR61E226KE15L")
        (field (name "Manufacturer") "muRata(村田)")
      )
      (libsource (lib "easyedapro") (part "GRM31CR61E226KE15L"))
    )
    (comp (ref "C53")
      (value "22uF")
      (footprint "easyedapro:C1206")
      (fields
        (field (name "Manufacturer Part") "GRM31CR61E226KE15L")
        (field (name "Manufacturer") "muRata(村田)")
      )
      (libsource (lib "easyedapro") (part "GRM31CR61E226KE15L"))
    )
    (comp (ref "C54")
      (value "22uF")
      (footprint "easyedapro:C1206")
      (fields
        (field (name "Manufacturer Part") "GRM31CR61E226KE15L")
        (field (name "Manufacturer") "muRata(村田)")
      )
      (libsource (lib "easyedapro") (part "GRM31CR61E226KE15L"))
    )
    (comp (ref "C55")
      (value "22uF")
      (footprint "easyedapro:C1206")
      (fields
        (field (name "Manufacturer Part") "GRM31CR61E226KE15L")
        (field (name "Manufacturer") "muRata(村田)")
      )
      (libsource (lib "easyedapro") (part "GRM31CR61E226KE15L"))
    )
    (comp (ref "C56")
      (value "22uF")
      (footprint "easyedapro:C1206")
      (fields
        (field (name "Manufacturer Part") "GRM31CR61E226KE15L")
        (field (name "Manufacturer") "muRata(村田)")
      )
      (libsource (lib "easyedapro") (part "GRM31CR61E226KE15L"))
    )
    (comp (ref "C57")
      (value "22uF")
      (footprint "easyedapro:C1206")
      (fields
        (field (name "Manufacturer Part") "GRM31CR61E226KE15L")
        (field (name "Manufacturer") "muRata(村田)")
      )
      (libsource (lib "easyedapro") (part "GRM31CR61E226KE15L"))
    )
    (comp (ref "C58")
      (value "22uF")
      (footprint "easyedapro:C1206")
      (fields
        (field (name "Manufacturer Part") "GRM31CR61E226KE15L")
        (field (name "Manufacturer") "muRata(村田)")
      )
      (libsource (lib "easyedapro") (part "GRM31CR61E226KE15L"))
    )
    (comp (ref "U9")
      (value "SN74HC595DR")
      (footprint "easyedapro:SOIC-16_L9.9-W3.9-P1.27-LS6.0-BL")
      (description "功能:串行至串行或并行;工作电压:2V~6V;时钟频率(fc):29MHz;元件数:1;每个元件位数:8;")
      (fields (field (name "Manufacturer") "TI(德州仪器)"))
      (libsource (lib "easyedapro") (part "SN74HC595DR"))
    )
    (comp (ref "U10")
      (value "SN74HC595DR")
      (footprint "easyedapro:SOIC-16_L9.9-W3.9-P1.27-LS6.0-BL")
      (description "功能:串行至串行或并行;工作电压:2V~6V;时钟频率(fc):29MHz;元件数:1;每个元件位数:8;")
      (fields (field (name "Manufacturer") "TI(德州仪器)"))
      (libsource (lib "easyedapro") (part "SN74HC595DR"))
    )
    (comp (ref "U11")
      (value "SN74HC595DR")
      (footprint "easyedapro:SOIC-16_L9.9-W3.9-P1.27-LS6.0-BL")
      (description "功能:串行至串行或并行;工作电压:2V~6V;时钟频率(fc):29MHz;元件数:1;每个元件位数:8;")
      (fields (field (name "Manufacturer") "TI(德州仪器)"))
      (libsource (lib "easyedapro") (part "SN74HC595DR"))
    )
    (comp (ref "U12")
      (value "SN74HC595DR")
      (footprint "easyedapro:SOIC-16_L9.9-W3.9-P1.27-LS6.0-BL")
      (description "功能:串行至串行或并行;工作电压:2V~6V;时钟频率(fc):29MHz;元件数:1;每个元件位数:8;")
      (fields (field (name "Manufacturer") "TI(德州仪器)"))
      (libsource (lib "easyedapro") (part "SN74HC595DR"))
    )
    (comp (ref "U13")
      (value "SN74HC595DR")
      (footprint "easyedapro:SOIC-16_L9.9-W3.9-P1.27-LS6.0-BL")
      (description "功能:串行至串行或并行;工作电压:2V~6V;时钟频率(fc):29MHz;元件数:1;每个元件位数:8;")
      (fields (field (name "Manufacturer") "TI(德州仪器)"))
      (libsource (lib "easyedapro") (part "SN74HC595DR"))
    )
    (comp (ref "U14")
      (value "SN74HC595DR")
      (footprint "easyedapro:SOIC-16_L9.9-W3.9-P1.27-LS6.0-BL")
      (description "功能:串行至串行或并行;工作电压:2V~6V;时钟频率(fc):29MHz;元件数:1;每个元件位数:8;")
      (fields (field (name "Manufacturer") "TI(德州仪器)"))
      (libsource (lib "easyedapro") (part "SN74HC595DR"))
    )
    (comp (ref "U15")
      (value "SN74HC595DR")
      (footprint "easyedapro:SOIC-16_L9.9-W3.9-P1.27-LS6.0-BL")
      (description "功能:串行至串行或并行;工作电压:2V~6V;时钟频率(fc):29MHz;元件数:1;每个元件位数:8;")
      (fields (field (name "Manufacturer") "TI(德州仪器)"))
      (libsource (lib "easyedapro") (part "SN74HC595DR"))
    )
    (comp (ref "U24")
      (value "ULN2003A")
      (footprint "easyedapro:SOP-16_L10.0-W3.9-P1.27-LS6.0-BL")
      (description "通道数:七路;集射极击穿电压(Vceo):50V;集电极电流(Ic):500mA;")
      (fields (field (name "Manufacturer") "Mixic(中科芯亿达)"))
      (libsource (lib "easyedapro") (part "ULN2003A_C181730"))
    )
    (comp (ref "U25")
      (value "ULN2003A")
      (footprint "easyedapro:SOP-16_L10.0-W3.9-P1.27-LS6.0-BL")
      (description "通道数:七路;集射极击穿电压(Vceo):50V;集电极电流(Ic):500mA;")
      (fields (field (name "Manufacturer") "Mixic(中科芯亿达)"))
      (libsource (lib "easyedapro") (part "ULN2003A_C181730"))
    )
    (comp (ref "U26")
      (value "ULN2003A")
      (footprint "easyedapro:SOP-16_L10.0-W3.9-P1.27-LS6.0-BL")
      (description "通道数:七路;集射极击穿电压(Vceo):50V;集电极电流(Ic):500mA;")
      (fields (field (name "Manufacturer") "Mixic(中科芯亿达)"))
      (libsource (lib "easyedapro") (part "ULN2003A_C181730"))
    )
    (comp (ref "U27")
      (value "ULN2003A")
      (footprint "easyedapro:SOP-16_L10.0-W3.9-P1.27-LS6.0-BL")
      (description "通道数:七路;集射极击穿电压(Vceo):50V;集电极电流(Ic):500mA;")
      (fields (field (name "Manufacturer") "Mixic(中科芯亿达)"))
      (libsource (lib "easyedapro") (part "ULN2003A_C181730"))
    )
    (comp (ref "U28")
      (value "ULN2003A")
      (footprint "easyedapro:SOP-16_L10.0-W3.9-P1.27-LS6.0-BL")
      (description "通道数:七路;集射极击穿电压(Vceo):50V;集电极电流(Ic):500mA;")
      (fields (field (name "Manufacturer") "Mixic(中科芯亿达)"))
      (libsource (lib "easyedapro") (part "ULN2003A_C181730"))
    )
    (comp (ref "U29")
      (value "ULN2003A")
      (footprint "easyedapro:SOP-16_L10.0-W3.9-P1.27-LS6.0-BL")
      (description "通道数:七路;集射极击穿电压(Vceo):50V;集电极电流(Ic):500mA;")
      (fields (field (name "Manufacturer") "Mixic(中科芯亿达)"))
      (libsource (lib "easyedapro") (part "ULN2003A_C181730"))
    )
    (comp (ref "U30")
      (value "ULN2003A")
      (footprint "easyedapro:SOP-16_L10.0-W3.9-P1.27-LS6.0-BL")
      (description "通道数:七路;集射极击穿电压(Vceo):50V;集电极电流(Ic):500mA;")
      (fields (field (name "Manufacturer") "Mixic(中科芯亿达)"))
      (libsource (lib "easyedapro") (part "ULN2003A_C181730"))
    )
    (comp (ref "U39")
      (value "HC-PM127-4.3H-1x12PZ")
      (footprint "easyedapro:HDR-TH_12P-P1.27-V-F")
      (fields (field (name "Manufacturer") "HC(虹成电子)"))
      (libsource (lib "easyedapro") (part "HC-PM127-4.3H-1X12PZ"))
    )
    (comp (ref "U40")
      (value "HC-PM127-4.3H-1x12PZ")
      (footprint "easyedapro:HDR-TH_12P-P1.27-V-F")
      (fields (field (name "Manufacturer") "HC(虹成电子)"))
      (libsource (lib "easyedapro") (part "HC-PM127-4.3H-1X12PZ"))
    )
    (comp (ref "U41")
      (value "HC-PM127-4.3H-1x12PZ")
      (footprint "easyedapro:HDR-TH_12P-P1.27-V-F")
      (fields (field (name "Manufacturer") "HC(虹成电子)"))
      (libsource (lib "easyedapro") (part "HC-PM127-4.3H-1X12PZ"))
    )
    (comp (ref "U42")
      (value "HC-PM127-4.3H-1x12PZ")
      (footprint "easyedapro:HDR-TH_12P-P1.27-V-F")
      (fields (field (name "Manufacturer") "HC(虹成电子)"))
      (libsource (lib "easyedapro") (part "HC-PM127-4.3H-1X12PZ"))
    )
    (comp (ref "U43")
      (value "HC-PM127-4.3H-1x12PZ")
      (footprint "easyedapro:HDR-TH_12P-P1.27-V-F")
      (fields (field (name "Manufacturer") "HC(虹成电子)"))
      (libsource (lib "easyedapro") (part "HC-PM127-4.3H-1X12PZ"))
    )
    (comp (ref "U44")
      (value "HC-PM127-4.3H-1x12PZ")
      (footprint "easyedapro:HDR-TH_12P-P1.27-V-F")
      (fields (field (name "Manufacturer") "HC(虹成电子)"))
      (libsource (lib "easyedapro") (part "HC-PM127-4.3H-1X12PZ"))
    )
    (comp (ref "U45")
      (value "HC-PM127-4.3H-1x12PZ")
      (footprint "easyedapro:HDR-TH_12P-P1.27-V-F")
      (fields (field (name "Manufacturer") "HC(虹成电子)"))
      (libsource (lib "easyedapro") (part "HC-PM127-4.3H-1X12PZ"))
    )
    (comp (ref "U46")
      (value "SN74HC595DR")
      (footprint "easyedapro:SOIC-16_L9.9-W3.9-P1.27-LS6.0-BL")
      (description "功能:串行至串行或并行;工作电压:2V~6V;时钟频率(fc):29MHz;元件数:1;每个元件位数:8;")
      (fields (field (name "Manufacturer") "TI(德州仪器)"))
      (libsource (lib "easyedapro") (part "SN74HC595DR"))
    )
    (comp (ref "U47")
      (value "ULN2003A")
      (footprint "easyedapro:SOP-16_L10.0-W3.9-P1.27-LS6.0-BL")
      (description "通道数:七路;集射极击穿电压(Vceo):50V;集电极电流(Ic):500mA;")
      (fields (field (name "Manufacturer") "Mixic(中科芯亿达)"))
      (libsource (lib "easyedapro") (part "ULN2003A_C181730"))
    )
    (comp (ref "U48")
      (value "HC-PM127-4.3H-1x12PZ")
      (footprint "easyedapro:HDR-TH_12P-P1.27-V-F")
      (fields (field (name "Manufacturer") "HC(虹成电子)"))
      (libsource (lib "easyedapro") (part "HC-PM127-4.3H-1X12PZ"))
    )
    (comp (ref "C39")
      (value "100nF")
      (footprint "easyedapro:C0603")
      (description "容值:100nF;精度:±10%;额定电压:50V;温度系数:X7R;")
      (fields
        (field (name "Manufacturer Part") "CGA0603X7R104K500JT")
        (field (name "Manufacturer") "HRE(芯声)")
      )
      (libsource (lib "easyedapro") (part "CGA0603X7R104K500JT"))
    )
    (comp (ref "C65")
      (value "10uF")
      (footprint "easyedapro:C0805")
      (description "容值:10uF;精度:±10%;额定电压:25V;温度系数:X5R;")
      (fields
        (field (name "Manufacturer Part") "GRM21BR61E106KA73L")
        (field (name "Manufacturer") "muRata(村田)")
      )
      (libsource (lib "easyedapro") (part "GRM21BR61E106KA73L"))
    )
    (comp (ref "C66")
      (value "10uF")
      (footprint "easyedapro:C0805")
      (description "容值:10uF;精度:±10%;额定电压:25V;温度系数:X5R;")
      (fields
        (field (name "Manufacturer Part") "GRM21BR61E106KA73L")
        (field (name "Manufacturer") "muRata(村田)")
      )
      (libsource (lib "easyedapro") (part "GRM21BR61E106KA73L"))
    )
    (comp (ref "C67")
      (value "10uF")
      (footprint "easyedapro:C0805")
      (description "容值:10uF;精度:±10%;额定电压:25V;温度系数:X5R;")
      (fields
        (field (name "Manufacturer Part") "GRM21BR61E106KA73L")
        (field (name "Manufacturer") "muRata(村田)")
      )
      (libsource (lib "easyedapro") (part "GRM21BR61E106KA73L"))
    )
    (comp (ref "C68")
      (value "10uF")
      (footprint "easyedapro:C0805")
      (description "容值:10uF;精度:±10%;额定电压:25V;温度系数:X5R;")
      (fields
        (field (name "Manufacturer Part") "GRM21BR61E106KA73L")
        (field (name "Manufacturer") "muRata(村田)")
      )
      (libsource (lib "easyedapro") (part "GRM21BR61E106KA73L"))
    )
    (comp (ref "C69")
      (value "22uF")
      (footprint "easyedapro:C1206")
      (fields
        (field (name "Manufacturer Part") "GRM31CR61E226KE15L")
        (field (name "Manufacturer") "muRata(村田)")
      )
      (libsource (lib "easyedapro") (part "GRM31CR61E226KE15L"))
    )
    (comp (ref "C70")
      (value "22uF")
      (footprint "easyedapro:C1206")
      (fields
        (field (name "Manufacturer Part") "GRM31CR61E226KE15L")
        (field (name "Manufacturer") "muRata(村田)")
      )
      (libsource (lib "easyedapro") (part "GRM31CR61E226KE15L"))
    )
    (comp (ref "C80")
      (value "100uF")
      (footprint "easyedapro:CAP-SMD_BD6.3-L6.6-W6.6-LS7.2-FD")
      (description "容值:100uF;精度:±20%;额定电压:16V;纹波电流:93mA@120Hz;等效串联电阻(ESR):-;")
      (fields
        (field (name "Manufacturer Part") "RVT100UF16V67RV0016")
        (field (name "Manufacturer") "KNSCHA(科尼盛)")
      )
      (libsource (lib "easyedapro") (part "RVT100UF16V67RV0016"))
    )
    (comp (ref "C83")
      (value "10uF")
      (footprint "easyedapro:C0805")
      (description "容值:10uF;精度:±10%;额定电压:25V;温度系数:X5R;")
      (fields
        (field (name "Manufacturer Part") "GRM21BR61E106KA73L")
        (field (name "Manufacturer") "muRata(村田)")
      )
      (libsource (lib "easyedapro") (part "GRM21BR61E106KA73L"))
    )
    (comp (ref "D1")
      (value "IN-S63AT5A")
      (footprint "easyedapro:LED0603-RD")
      (fields (field (name "Manufacturer") "Inolux"))
      (libsource (lib "easyedapro") (part "IN-S63AT5A"))
    )
    (comp (ref "deR28")
      (value "1kΩ")
      (footprint "easyedapro:R0603")
      (fields (field (name "Manufacturer Part") "RCA031KFLF") (field (name "Manufacturer") "HKR(香港电阻)"))
      (libsource (lib "easyedapro") (part "RCA031KFLF"))
    )
    (comp (ref "J1")
      (value "TYPE-C 6P")
      (footprint "easyedapro:TYPE-C-SMD_TYPE-C-6P_1")
      (description "连接器类型:Type-C;协议标准:-;公母:母;安装方式:卧贴;触点数量:6P;端口数量:1;额定电流 - 电源:3A;工作温度:-40℃~+85℃;")
      (fields (field (name "Manufacturer") "SHOU HAN(首韩)"))
      (libsource (lib "easyedapro") (part "TYPE-C 6P"))
    )
    (comp (ref "J3")
      (value "~")
      (footprint "easyedapro:Test-Point-0.5mm")
      (description "Test Point 测试点")
      (libsource (lib "easyedapro") (part "Test-Point"))
    )
    (comp (ref "J4")
      (value "~")
      (footprint "easyedapro:Test-Point-0.5mm")
      (description "Test Point 测试点")
      (libsource (lib "easyedapro") (part "Test-Point"))
    )
    (comp (ref "J_NTC")
      (value "B-2100S02P-A110")
      (footprint "easyedapro:HDR-TH_2P-P2.54-V-M-1")
      (fields (field (name "Manufacturer") "Ckmtw(灿科盟)"))
      (libsource (lib "easyedapro") (part "210S-1*2P L=11.6MMGold-plated black"))
    )
    (comp (ref "L4")
      (value "2.2uH")
      (footprint "easyedapro:IND-SMD_L5.3-W5.1")
      (description "电感值:2.2uH;精度:±20%;额定电流:6.6A;饱和电流(Isat):9A;")
      (fields (field (name "Manufacturer Part") "SPM5030VT-2R2M-D") (field (name "Manufacturer") "TDK"))
      (libsource (lib "easyedapro") (part "SPM5030VT-2R2M-D"))
    )
    (comp (ref "Q1")
      (value "WSD30L120DN56")
      (footprint "easyedapro:POWERVDFN-8_L6.0-W5.0-P1.27-BL")
      (description "数量:1个P沟道;漏源电压(Vdss):30V;连续漏极电流(Id):120A;导通电阻(RDS(on)):6.8mΩ@4.5V;耗散功率(Pd):78W;阈值电压(Vgs(th)):2.5V;")
      (fields (field (name "Manufacturer") "WINSOK(微硕)"))
      (libsource (lib "easyedapro") (part "WSD30L120DN56"))
    )
    (comp (ref "R2")
      (value "100kΩ")
      (footprint "easyedapro:R0603")
      (fields (field (name "Manufacturer Part") "RCA03100KFLF") (field (name "Manufacturer") "HKR(香港电阻)"))
      (libsource (lib "easyedapro") (part "RCA03100KFLF"))
    )
    (comp (ref "R4")
      (value "100kΩ")
      (footprint "easyedapro:R0603")
      (fields (field (name "Manufacturer Part") "RCA03100KFLF") (field (name "Manufacturer") "HKR(香港电阻)"))
      (libsource (lib "easyedapro") (part "RCA03100KFLF"))
    )
    (comp (ref "R16")
      (value "5.1kΩ")
      (footprint "easyedapro:R0603")
      (fields (field (name "Manufacturer Part") "RCA035K1FLF") (field (name "Manufacturer") "HKR(香港电阻)"))
      (libsource (lib "easyedapro") (part "RCA035K1FLF"))
    )
    (comp (ref "R17")
      (value "5.1kΩ")
      (footprint "easyedapro:R0603")
      (fields (field (name "Manufacturer Part") "RCA035K1FLF") (field (name "Manufacturer") "HKR(香港电阻)"))
      (libsource (lib "easyedapro") (part "RCA035K1FLF"))
    )
    (comp (ref "R20")
      (value "90kΩ")
      (footprint "easyedapro:R0603")
      (description "电阻类型:厚膜电阻;阻值:90kΩ;精度:±1%;功率:100mW;最大工作电压:75V;温度系数:±100ppm/℃;")
      (fields
        (field (name "Manufacturer Part") "0603WAF9002T5E")
        (field (name "Manufacturer") "UNI-ROYAL(厚声)")
      )
      (libsource (lib "easyedapro") (part "0603WAF9002T5E"))
    )
    (comp (ref "R21")
      (value "120kΩ")
      (footprint "easyedapro:R0603")
      (fields (field (name "Manufacturer Part") "RCA03120KFLF") (field (name "Manufacturer") "HKR(香港电阻)"))
      (libsource (lib "easyedapro") (part "RCA03120KFLF"))
    )
    (comp (ref "R22")
      (value "51kΩ")
      (footprint "easyedapro:R0603")
      (fields (field (name "Manufacturer Part") "RCA0351KFLF") (field (name "Manufacturer") "HKR(香港电阻)"))
      (libsource (lib "easyedapro") (part "RCA0351KFLF"))
    )
    (comp (ref "R23")
      (value "500mΩ")
      (footprint "easyedapro:R0603")
      (fields (field (name "Manufacturer Part") "RL0603FR-070R5L") (field (name "Manufacturer") "YAGEO(国巨)"))
      (libsource (lib "easyedapro") (part "RL0603FR-070R5L"))
    )
    (comp (ref "R24")
      (value "1kΩ")
      (footprint "easyedapro:R0603")
      (fields (field (name "Manufacturer Part") "RCA031KFLF") (field (name "Manufacturer") "HKR(香港电阻)"))
      (libsource (lib "easyedapro") (part "RCA031KFLF"))
    )
    (comp (ref "R39")
      (value "120kΩ")
      (footprint "easyedapro:R0603")
      (fields (field (name "Manufacturer Part") "RCA03120KFLF") (field (name "Manufacturer") "HKR(香港电阻)"))
      (libsource (lib "easyedapro") (part "RCA03120KFLF"))
    )
    (comp (ref "U53")
      (value "IP2326")
      (footprint "easyedapro:VQFN-24_L4.0-W4.0-P0.50-BL-EP2.5")
      (description "工作电压:4.5V~9.5V;最大充电电流:1.5A;电池类型:锂电池;电池节数:2~3;")
      (fields (field (name "Manufacturer") "INJOINIC(英集芯)"))
      (libsource (lib "easyedapro") (part "IP2326"))
    )
    (comp (ref "C40")
      (value "100nF")
      (footprint "easyedapro:C0603")
      (description "容值:100nF;精度:±10%;额定电压:50V;温度系数:X7R;")
      (fields
        (field (name "Manufacturer Part") "CGA0603X7R104K500JT")
        (field (name "Manufacturer") "HRE(芯声)")
      )
      (libsource (lib "easyedapro") (part "CGA0603X7R104K500JT"))
    )
    (comp (ref "C86")
      (value "22uF")
      (footprint "easyedapro:C1206")
      (fields
        (field (name "Manufacturer Part") "GRM31CR61E226KE15L")
        (field (name "Manufacturer") "muRata(村田)")
      )
      (libsource (lib "easyedapro") (part "GRM31CR61E226KE15L"))
    )
    (comp (ref "C87")
      (value "100nF")
      (footprint "easyedapro:C0603")
      (description "容值:100nF;精度:±10%;额定电压:50V;温度系数:X7R;")
      (fields
        (field (name "Manufacturer Part") "CGA0603X7R104K500JT")
        (field (name "Manufacturer") "HRE(芯声)")
      )
      (libsource (lib "easyedapro") (part "CGA0603X7R104K500JT"))
    )
    (comp (ref "C88")
      (value "10nF")
      (footprint "easyedapro:C0603")
      (fields
        (field (name "Manufacturer Part") "GRM188R71H103KA01D")
        (field (name "Manufacturer") "muRata(村田)")
      )
      (libsource (lib "easyedapro") (part "GRM188R71H103KA01D"))
    )
    (comp (ref "C90")
      (value "100nF")
      (footprint "easyedapro:C0603")
      (description "容值:100nF;精度:±10%;额定电压:50V;温度系数:X7R;")
      (fields
        (field (name "Manufacturer Part") "CGA0603X7R104K500JT")
        (field (name "Manufacturer") "HRE(芯声)")
      )
      (libsource (lib "easyedapro") (part "CGA0603X7R104K500JT"))
    )
    (comp (ref "D2")
      (value "IN-S63AT5A")
      (footprint "easyedapro:LED0603-RD")
      (fields (field (name "Manufacturer") "Inolux"))
      (libsource (lib "easyedapro") (part "IN-S63AT5A"))
    )
    (comp (ref "J_ESP_L")
      (value "CS-1165SDIG-1*22")
      (footprint "easyedapro:HDR-TH_22P-P2.54-V-F")
      (fields (field (name "Manufacturer") "CST(永丰盈)"))
      (libsource (lib "easyedapro") (part "CS-1165SDIG-1*22"))
    )
    (comp (ref "J_ESP_R")
      (value "CS-1165SDIG-1*22")
      (footprint "easyedapro:HDR-TH_22P-P2.54-V-F")
      (fields (field (name "Manufacturer") "CST(永丰盈)"))
      (libsource (lib "easyedapro") (part "CS-1165SDIG-1*22"))
    )
    (comp (ref "J_test")
      (value "CS-1165SDIG-1*22")
      (footprint "easyedapro:HDR-TH_22P-P2.54-V-F")
      (fields (field (name "Manufacturer") "CST(永丰盈)"))
      (libsource (lib "easyedapro") (part "CS-1165SDIG-1*22"))
    )
    (comp (ref "R3")
      (value "10kΩ")
      (footprint "easyedapro:R0603")
      (fields (field (name "Manufacturer Part") "RT0603BRD0710KL") (field (name "Manufacturer") "YAGEO(国巨)"))
      (libsource (lib "easyedapro") (part "RT0603BRD0710KL"))
    )
    (comp (ref "R5")
      (value "20Ω")
      (footprint "easyedapro:R0603")
      (fields (field (name "Manufacturer Part") "RCA0320RFLF") (field (name "Manufacturer") "HKR(香港电阻)"))
      (libsource (lib "easyedapro") (part "RCA0320RFLF"))
    )
    (comp (ref "R6")
      (value "20kΩ")
      (footprint "easyedapro:R0603")
      (fields (field (name "Manufacturer Part") "RT0603BRD0720KL") (field (name "Manufacturer") "YAGEO(国巨)"))
      (libsource (lib "easyedapro") (part "RT0603BRD0720KL"))
    )
    (comp (ref "R11")
      (value "10kΩ")
      (footprint "easyedapro:R0603")
      (fields (field (name "Manufacturer Part") "RT0603BRD0710KL") (field (name "Manufacturer") "YAGEO(国巨)"))
      (libsource (lib "easyedapro") (part "RT0603BRD0710KL"))
    )
    (comp (ref "R12")
      (value "10kΩ")
      (footprint "easyedapro:R0603")
      (fields (field (name "Manufacturer Part") "RT0603BRD0710KL") (field (name "Manufacturer") "YAGEO(国巨)"))
      (libsource (lib "easyedapro") (part "RT0603BRD0710KL"))
    )
    (comp (ref "R13")
      (value "20Ω")
      (footprint "easyedapro:R0603")
      (fields (field (name "Manufacturer Part") "RCA0320RFLF") (field (name "Manufacturer") "HKR(香港电阻)"))
      (libsource (lib "easyedapro") (part "RCA0320RFLF"))
    )
    (comp (ref "R14")
      (value "20Ω")
      (footprint "easyedapro:R0603")
      (fields (field (name "Manufacturer Part") "RCA0320RFLF") (field (name "Manufacturer") "HKR(香港电阻)"))
      (libsource (lib "easyedapro") (part "RCA0320RFLF"))
    )
    (comp (ref "R15")
      (value "39kΩ")
      (footprint "easyedapro:R0603")
      (fields (field (name "Manufacturer Part") "RCT0339KFLF") (field (name "Manufacturer") "HKR(香港电阻)"))
      (libsource (lib "easyedapro") (part "RCT0339KFLF"))
    )
    (comp (ref "R19")
      (value "0Ω")
      (footprint "easyedapro:R0805")
      (description "电阻类型:厚膜电阻;阻值:0Ω;精度:±5%;功率:125mW;工作电压:150V;")
      (fields (field (name "Manufacturer Part") "FRC0805P000 TS") (field (name "Manufacturer") "FOJAN(富捷)"))
      (libsource (lib "easyedapro") (part "FRC0805P000 TS"))
    )
    (comp (ref "R25")
      (value "1kΩ")
      (footprint "easyedapro:R0603")
      (fields (field (name "Manufacturer Part") "RCA031KFLF") (field (name "Manufacturer") "HKR(香港电阻)"))
      (libsource (lib "easyedapro") (part "RCA031KFLF"))
    )
    (comp (ref "R30")
      (value "100kΩ")
      (footprint "easyedapro:R0603")
      (fields (field (name "Manufacturer Part") "RCA03100KFLF") (field (name "Manufacturer") "HKR(香港电阻)"))
      (libsource (lib "easyedapro") (part "RCA03100KFLF"))
    )
    (comp (ref "R31")
      (value "100kΩ")
      (footprint "easyedapro:R0603")
      (fields (field (name "Manufacturer Part") "RCA03100KFLF") (field (name "Manufacturer") "HKR(香港电阻)"))
      (libsource (lib "easyedapro") (part "RCA03100KFLF"))
    )
    (comp (ref "R32")
      (value "10kΩ")
      (footprint "easyedapro:R0603")
      (fields (field (name "Manufacturer Part") "RT0603BRD0710KL") (field (name "Manufacturer") "YAGEO(国巨)"))
      (libsource (lib "easyedapro") (part "RT0603BRD0710KL"))
    )
    (comp (ref "R33")
      (value "100kΩ")
      (footprint "easyedapro:R0603")
      (fields (field (name "Manufacturer Part") "RCA03100KFLF") (field (name "Manufacturer") "HKR(香港电阻)"))
      (libsource (lib "easyedapro") (part "RCA03100KFLF"))
    )
    (comp (ref "R34")
      (value "150kΩ")
      (footprint "easyedapro:R0603")
      (fields (field (name "Manufacturer Part") "FRC0603F1503TS") (field (name "Manufacturer") "FOJAN(富捷)"))
      (libsource (lib "easyedapro") (part "FRC0603F1503TS"))
    )
    (comp (ref "R35")
      (value "10kΩ")
      (footprint "easyedapro:R0603")
      (fields (field (name "Manufacturer Part") "RT0603BRD0710KL") (field (name "Manufacturer") "YAGEO(国巨)"))
      (libsource (lib "easyedapro") (part "RT0603BRD0710KL"))
    )
    (comp (ref "R36")
      (value "390kΩ")
      (footprint "easyedapro:R0603")
      (fields (field (name "Manufacturer Part") "TD03G3903BT") (field (name "Manufacturer") "FH(风华)"))
      (libsource (lib "easyedapro") (part "TD03G3903BT"))
    )
    (comp (ref "R40")
      (value "47kΩ")
      (footprint "easyedapro:R0603")
      (description "电阻类型:厚膜电阻;阻值:47kΩ;精度:±1%;功率:100mW;工作电压:75V;温度系数:±100ppm/℃;")
      (fields
        (field (name "Manufacturer Part") "0603WAF4702T5E")
        (field (name "Manufacturer") "UNI-ROYAL(厚声)")
      )
      (libsource (lib "easyedapro") (part "0603WAF4702T5E"))
    )
    (comp (ref "R41")
      (value "47kΩ")
      (footprint "easyedapro:R0603")
      (description "电阻类型:厚膜电阻;阻值:47kΩ;精度:±1%;功率:100mW;工作电压:75V;温度系数:±100ppm/℃;")
      (fields
        (field (name "Manufacturer Part") "0603WAF4702T5E")
        (field (name "Manufacturer") "UNI-ROYAL(厚声)")
      )
      (libsource (lib "easyedapro") (part "0603WAF4702T5E"))
    )
    (comp (ref "R42")
      (value "47kΩ")
      (footprint "easyedapro:R0603")
      (description "电阻类型:厚膜电阻;阻值:47kΩ;精度:±1%;功率:100mW;工作电压:75V;温度系数:±100ppm/℃;")
      (fields
        (field (name "Manufacturer Part") "0603WAF4702T5E")
        (field (name "Manufacturer") "UNI-ROYAL(厚声)")
      )
      (libsource (lib "easyedapro") (part "0603WAF4702T5E"))
    )
    (comp (ref "SW1")
      (value "TSA06131-250B532CA")
      (footprint "easyedapro:SW-TH_4P-L6.1-W6.1-P4.50-LS6.5")
      (description "6*6*25插件轻触开关、280g、Fe盖、PC黑柄")
      (fields (field (name "Manufacturer") "Khon(康宏电子)"))
      (libsource (lib "easyedapro") (part "TSA06131-250B532CA"))
    )
    (comp (ref "SW2")
      (value "SK-12D07-VG 4 NS PA")
      (footprint "easyedapro:SW-TH_SK-12D07-VG4-NS-PA")
      (description "电路结构:单刀双掷;安装方式:直插;额定电压(DC):30V;")
      (fields (field (name "Manufacturer") "C&K"))
      (libsource (lib "easyedapro") (part "SK-12D07-VG 4 NS PA"))
    )
    (comp (ref "U54")
      (value "TMUX1511PWR")
      (footprint "easyedapro:TSSOP-14_L5.0-W4.4-P0.65-LS6.4-BL")
      (fields (field (name "Manufacturer") "TI(德州仪器)"))
      (libsource (lib "easyedapro") (part "TMUX1511PWR"))
    )
    (comp (ref "U55")
      (value "TPS3700DDCR")
      (footprint "easyedapro:SOT-23-6_L2.9-W1.6-P0.95-LS2.8-BL")
      (fields (field (name "Manufacturer") "TI(德州仪器)"))
      (libsource (lib "easyedapro") (part "TPS3700DDCR"))
    )
  )
  (nets
    (net (code "1") (name "ADC_EN") (class "Default")
      (node (ref "J_ESP_L") (pin "5") (pinfunction "5_5") (pintype "unspecified"))
      (node (ref "R33") (pin "2") (pinfunction "2_2") (pintype "unspecified"))
      (node (ref "U54") (pin "1") (pinfunction "SEL1_1") (pintype "unspecified"))
    )
    (net (code "2") (name "BAT+") (class "Default")
      (node (ref "C67") (pin "1") (pinfunction "1_1") (pintype "unspecified"))
      (node (ref "C68") (pin "1") (pinfunction "1_1") (pintype "unspecified"))
      (node (ref "J3") (pin "1") (pinfunction "1_1") (pintype "input"))
      (node (ref "Q1") (pin "5") (pinfunction "D_5") (pintype "unspecified"))
      (node (ref "Q1") (pin "6") (pinfunction "D_6") (pintype "unspecified"))
      (node (ref "Q1") (pin "7") (pinfunction "D_7") (pintype "unspecified"))
      (node (ref "Q1") (pin "8") (pinfunction "D_8") (pintype "unspecified"))
      (node (ref "Q1") (pin "9") (pinfunction "D_9") (pintype "unspecified"))
      (node (ref "U53") (pin "21") (pinfunction "VOUT_21") (pintype "unspecified"))
      (node (ref "U53") (pin "22") (pinfunction "VOUT_22") (pintype "unspecified"))
    )
    (net (code "3") (name "CHG_BST") (class "Default")
      (node (ref "C39") (pin "1") (pinfunction "1_1") (pintype "unspecified"))
      (node (ref "U53") (pin "14") (pinfunction "BST_14") (pintype "unspecified"))
    )
    (net (code "4") (name "CHG_EN") (class "Default")
      (node (ref "R4") (pin "1") (pinfunction "1_1") (pintype "unspecified"))
      (node (ref "U53") (pin "12") (pinfunction "EN_12") (pintype "unspecified"))
    )
    (net (code "5") (name "CHG_ISET") (class "Default")
      (node (ref "R20") (pin "2") (pinfunction "2_2") (pintype "unspecified"))
      (node (ref "U53") (pin "11") (pinfunction "ISET_11") (pintype "unspecified"))
    )
    (net (code "6") (name "CHG_LED") (class "Default")
      (node (ref "R24") (pin "1") (pinfunction "1_1") (pintype "unspecified"))
      (node (ref "U53") (pin "6") (pinfunction "LED_6") (pintype "unspecified"))
    )
    (net (code "7") (name "CHG_LED_A") (class "Default")
      (node (ref "D1") (pin "2") (pinfunction "A_2") (pintype "unspecified"))
      (node (ref "R24") (pin "2") (pinfunction "2_2") (pintype "unspecified"))
    )
    (net (code "8") (name "CHG_NTC") (class "Default")
      (node (ref "J_NTC") (pin "1") (pinfunction "1_1") (pintype "unspecified"))
      (node (ref "R22") (pin "2") (pinfunction "2_2") (pintype "unspecified"))
      (node (ref "U53") (pin "4") (pinfunction "NTC_4") (pintype "unspecified"))
    )
    (net (code "9") (name "CHG_SW") (class "Default")
      (node (ref "C39") (pin "2") (pinfunction "2_2") (pintype "unspecified"))
      (node (ref "L4") (pin "1") (pinfunction "1_1") (pintype "unspecified"))
      (node (ref "U53") (pin "15") (pinfunction "LX_15") (pintype "unspecified"))
      (node (ref "U53") (pin "16") (pinfunction "LX_16") (pintype "unspecified"))
      (node (ref "U53") (pin "17") (pinfunction "LX_17") (pintype "unspecified"))
    )
    (net (code "10") (name "CHG_TIMER") (class "Default")
      (node (ref "R21") (pin "2") (pinfunction "2_2") (pintype "unspecified"))
      (node (ref "U53") (pin "7") (pinfunction "TIME_SET_7") (pintype "unspecified"))
    )
    (net (code "11") (name "CHG_UVSET") (class "Default")
      (node (ref "U53") (pin "8") (pinfunction "VIN_UVSET_8") (pintype "unspecified"))
      (node (ref "deR28") (pin "2") (pinfunction "2_2") (pintype "unspecified"))
    )
    (net (code "12") (name "CHG_VIN_FILTER") (class "Default")
      (node (ref "C83") (pin "1") (pinfunction "1_1") (pintype "unspecified"))
      (node (ref "R23") (pin "1") (pinfunction "1_1") (pintype "unspecified"))
      (node (ref "R4") (pin "2") (pinfunction "2_2") (pintype "unspecified"))
      (node (ref "U53") (pin "13") (pinfunction "VIN_13") (pintype "unspecified"))
    )
    (net (code "13") (name "CHG_VSET") (class "Default")
      (node (ref "R39") (pin "2") (pinfunction "2_2") (pintype "unspecified"))
      (node (ref "U53") (pin "3") (pinfunction "VSET_3") (pintype "unspecified"))
    )
    (net (code "14") (name "CHG_VSYS") (class "Default")
      (node (ref "C69") (pin "2") (pinfunction "2_2") (pintype "input"))
      (node (ref "C70") (pin "1") (pinfunction "1_1") (pintype "input"))
      (node (ref "U53") (pin "19") (pinfunction "VSYS_19") (pintype "unspecified"))
      (node (ref "U53") (pin "20") (pinfunction "VSYS_20") (pintype "unspecified"))
    )
    (net (code "15") (name "DRV01_A") (class "Default")
      (node (ref "U1") (pin "15") (pinfunction "QA_15") (pintype "unspecified"))
      (node (ref "U16") (pin "1") (pinfunction "1B_1") (pintype "unspecified"))
    )
    (net (code "16") (name "DRV01_B") (class "Default")
      (node (ref "U1") (pin "1") (pinfunction "QB_1") (pintype "unspecified"))
      (node (ref "U16") (pin "2") (pinfunction "2B_2") (pintype "unspecified"))
    )
    (net (code "17") (name "DRV01_C") (class "Default")
      (node (ref "U1") (pin "2") (pinfunction "QC_2") (pintype "unspecified"))
      (node (ref "U16") (pin "3") (pinfunction "3B_3") (pintype "unspecified"))
    )
    (net (code "18") (name "DRV01_D") (class "Default")
      (node (ref "U1") (pin "3") (pinfunction "QD_3") (pintype "unspecified"))
      (node (ref "U16") (pin "4") (pinfunction "4B_4") (pintype "unspecified"))
    )
    (net (code "19") (name "DRV01_E") (class "Default")
      (node (ref "U1") (pin "4") (pinfunction "QE_4") (pintype "unspecified"))
      (node (ref "U16") (pin "5") (pinfunction "5B_5") (pintype "unspecified"))
    )
    (net (code "20") (name "DRV01_F") (class "Default")
      (node (ref "U1") (pin "5") (pinfunction "QF_5") (pintype "unspecified"))
      (node (ref "U16") (pin "6") (pinfunction "6B_6") (pintype "unspecified"))
    )
    (net (code "21") (name "DRV01_SMA") (class "Default")
      (node (ref "U1") (pin "6") (pinfunction "QG_6") (pintype "unspecified"))
      (node (ref "U16") (pin "7") (pinfunction "7B_7") (pintype "unspecified"))
    )
    (net (code "22") (name "DRV02_A") (class "Default")
      (node (ref "U17") (pin "1") (pinfunction "1B_1") (pintype "unspecified"))
      (node (ref "U2") (pin "15") (pinfunction "QA_15") (pintype "unspecified"))
    )
    (net (code "23") (name "DRV02_B") (class "Default")
      (node (ref "U17") (pin "2") (pinfunction "2B_2") (pintype "unspecified"))
      (node (ref "U2") (pin "1") (pinfunction "QB_1") (pintype "unspecified"))
    )
    (net (code "24") (name "DRV02_C") (class "Default")
      (node (ref "U17") (pin "3") (pinfunction "3B_3") (pintype "unspecified"))
      (node (ref "U2") (pin "2") (pinfunction "QC_2") (pintype "unspecified"))
    )
    (net (code "25") (name "DRV02_D") (class "Default")
      (node (ref "U17") (pin "4") (pinfunction "4B_4") (pintype "unspecified"))
      (node (ref "U2") (pin "3") (pinfunction "QD_3") (pintype "unspecified"))
    )
    (net (code "26") (name "DRV02_E") (class "Default")
      (node (ref "U17") (pin "5") (pinfunction "5B_5") (pintype "unspecified"))
      (node (ref "U2") (pin "4") (pinfunction "QE_4") (pintype "unspecified"))
    )
    (net (code "27") (name "DRV02_F") (class "Default")
      (node (ref "U17") (pin "6") (pinfunction "6B_6") (pintype "unspecified"))
      (node (ref "U2") (pin "5") (pinfunction "QF_5") (pintype "unspecified"))
    )
    (net (code "28") (name "DRV02_SMA") (class "Default")
      (node (ref "U17") (pin "7") (pinfunction "7B_7") (pintype "unspecified"))
      (node (ref "U2") (pin "6") (pinfunction "QG_6") (pintype "unspecified"))
    )
    (net (code "29") (name "DRV03_A") (class "Default")
      (node (ref "U18") (pin "1") (pinfunction "1B_1") (pintype "unspecified"))
      (node (ref "U3") (pin "15") (pinfunction "QA_15") (pintype "unspecified"))
    )
    (net (code "30") (name "DRV03_B") (class "Default")
      (node (ref "U18") (pin "2") (pinfunction "2B_2") (pintype "unspecified"))
      (node (ref "U3") (pin "1") (pinfunction "QB_1") (pintype "unspecified"))
    )
    (net (code "31") (name "DRV03_C") (class "Default")
      (node (ref "U18") (pin "3") (pinfunction "3B_3") (pintype "unspecified"))
      (node (ref "U3") (pin "2") (pinfunction "QC_2") (pintype "unspecified"))
    )
    (net (code "32") (name "DRV03_D") (class "Default")
      (node (ref "U18") (pin "4") (pinfunction "4B_4") (pintype "unspecified"))
      (node (ref "U3") (pin "3") (pinfunction "QD_3") (pintype "unspecified"))
    )
    (net (code "33") (name "DRV03_E") (class "Default")
      (node (ref "U18") (pin "5") (pinfunction "5B_5") (pintype "unspecified"))
      (node (ref "U3") (pin "4") (pinfunction "QE_4") (pintype "unspecified"))
    )
    (net (code "34") (name "DRV03_F") (class "Default")
      (node (ref "U18") (pin "6") (pinfunction "6B_6") (pintype "unspecified"))
      (node (ref "U3") (pin "5") (pinfunction "QF_5") (pintype "unspecified"))
    )
    (net (code "35") (name "DRV03_SMA") (class "Default")
      (node (ref "U18") (pin "7") (pinfunction "7B_7") (pintype "unspecified"))
      (node (ref "U3") (pin "6") (pinfunction "QG_6") (pintype "unspecified"))
    )
    (net (code "36") (name "DRV04_A") (class "Default")
      (node (ref "U19") (pin "1") (pinfunction "1B_1") (pintype "unspecified"))
      (node (ref "U4") (pin "15") (pinfunction "QA_15") (pintype "unspecified"))
    )
    (net (code "37") (name "DRV04_B") (class "Default")
      (node (ref "U19") (pin "2") (pinfunction "2B_2") (pintype "unspecified"))
      (node (ref "U4") (pin "1") (pinfunction "QB_1") (pintype "unspecified"))
    )
    (net (code "38") (name "DRV04_C") (class "Default")
      (node (ref "U19") (pin "3") (pinfunction "3B_3") (pintype "unspecified"))
      (node (ref "U4") (pin "2") (pinfunction "QC_2") (pintype "unspecified"))
    )
    (net (code "39") (name "DRV04_D") (class "Default")
      (node (ref "U19") (pin "4") (pinfunction "4B_4") (pintype "unspecified"))
      (node (ref "U4") (pin "3") (pinfunction "QD_3") (pintype "unspecified"))
    )
    (net (code "40") (name "DRV04_E") (class "Default")
      (node (ref "U19") (pin "5") (pinfunction "5B_5") (pintype "unspecified"))
      (node (ref "U4") (pin "4") (pinfunction "QE_4") (pintype "unspecified"))
    )
    (net (code "41") (name "DRV04_F") (class "Default")
      (node (ref "U19") (pin "6") (pinfunction "6B_6") (pintype "unspecified"))
      (node (ref "U4") (pin "5") (pinfunction "QF_5") (pintype "unspecified"))
    )
    (net (code "42") (name "DRV04_SMA") (class "Default")
      (node (ref "U19") (pin "7") (pinfunction "7B_7") (pintype "unspecified"))
      (node (ref "U4") (pin "6") (pinfunction "QG_6") (pintype "unspecified"))
    )
    (net (code "43") (name "DRV05_A") (class "Default")
      (node (ref "U20") (pin "1") (pinfunction "1B_1") (pintype "unspecified"))
      (node (ref "U5") (pin "15") (pinfunction "QA_15") (pintype "unspecified"))
    )
    (net (code "44") (name "DRV05_B") (class "Default")
      (node (ref "U20") (pin "2") (pinfunction "2B_2") (pintype "unspecified"))
      (node (ref "U5") (pin "1") (pinfunction "QB_1") (pintype "unspecified"))
    )
    (net (code "45") (name "DRV05_C") (class "Default")
      (node (ref "U20") (pin "3") (pinfunction "3B_3") (pintype "unspecified"))
      (node (ref "U5") (pin "2") (pinfunction "QC_2") (pintype "unspecified"))
    )
    (net (code "46") (name "DRV05_D") (class "Default")
      (node (ref "U20") (pin "4") (pinfunction "4B_4") (pintype "unspecified"))
      (node (ref "U5") (pin "3") (pinfunction "QD_3") (pintype "unspecified"))
    )
    (net (code "47") (name "DRV05_E") (class "Default")
      (node (ref "U20") (pin "5") (pinfunction "5B_5") (pintype "unspecified"))
      (node (ref "U5") (pin "4") (pinfunction "QE_4") (pintype "unspecified"))
    )
    (net (code "48") (name "DRV05_F") (class "Default")
      (node (ref "U20") (pin "6") (pinfunction "6B_6") (pintype "unspecified"))
      (node (ref "U5") (pin "5") (pinfunction "QF_5") (pintype "unspecified"))
    )
    (net (code "49") (name "DRV05_SMA") (class "Default")
      (node (ref "U20") (pin "7") (pinfunction "7B_7") (pintype "unspecified"))
      (node (ref "U5") (pin "6") (pinfunction "QG_6") (pintype "unspecified"))
    )
    (net (code "50") (name "DRV06_A") (class "Default")
      (node (ref "U21") (pin "1") (pinfunction "1B_1") (pintype "unspecified"))
      (node (ref "U6") (pin "15") (pinfunction "QA_15") (pintype "unspecified"))
    )
    (net (code "51") (name "DRV06_B") (class "Default")
      (node (ref "U21") (pin "2") (pinfunction "2B_2") (pintype "unspecified"))
      (node (ref "U6") (pin "1") (pinfunction "QB_1") (pintype "unspecified"))
    )
    (net (code "52") (name "DRV06_C") (class "Default")
      (node (ref "U21") (pin "3") (pinfunction "3B_3") (pintype "unspecified"))
      (node (ref "U6") (pin "2") (pinfunction "QC_2") (pintype "unspecified"))
    )
    (net (code "53") (name "DRV06_D") (class "Default")
      (node (ref "U21") (pin "4") (pinfunction "4B_4") (pintype "unspecified"))
      (node (ref "U6") (pin "3") (pinfunction "QD_3") (pintype "unspecified"))
    )
    (net (code "54") (name "DRV06_E") (class "Default")
      (node (ref "U21") (pin "5") (pinfunction "5B_5") (pintype "unspecified"))
      (node (ref "U6") (pin "4") (pinfunction "QE_4") (pintype "unspecified"))
    )
    (net (code "55") (name "DRV06_F") (class "Default")
      (node (ref "U21") (pin "6") (pinfunction "6B_6") (pintype "unspecified"))
      (node (ref "U6") (pin "5") (pinfunction "QF_5") (pintype "unspecified"))
    )
    (net (code "56") (name "DRV06_SMA") (class "Default")
      (node (ref "U21") (pin "7") (pinfunction "7B_7") (pintype "unspecified"))
      (node (ref "U6") (pin "6") (pinfunction "QG_6") (pintype "unspecified"))
    )
    (net (code "57") (name "DRV07_A") (class "Default")
      (node (ref "U22") (pin "1") (pinfunction "1B_1") (pintype "unspecified"))
      (node (ref "U7") (pin "15") (pinfunction "QA_15") (pintype "unspecified"))
    )
    (net (code "58") (name "DRV07_B") (class "Default")
      (node (ref "U22") (pin "2") (pinfunction "2B_2") (pintype "unspecified"))
      (node (ref "U7") (pin "1") (pinfunction "QB_1") (pintype "unspecified"))
    )
    (net (code "59") (name "DRV07_C") (class "Default")
      (node (ref "U22") (pin "3") (pinfunction "3B_3") (pintype "unspecified"))
      (node (ref "U7") (pin "2") (pinfunction "QC_2") (pintype "unspecified"))
    )
    (net (code "60") (name "DRV07_D") (class "Default")
      (node (ref "U22") (pin "4") (pinfunction "4B_4") (pintype "unspecified"))
      (node (ref "U7") (pin "3") (pinfunction "QD_3") (pintype "unspecified"))
    )
    (net (code "61") (name "DRV07_E") (class "Default")
      (node (ref "U22") (pin "5") (pinfunction "5B_5") (pintype "unspecified"))
      (node (ref "U7") (pin "4") (pinfunction "QE_4") (pintype "unspecified"))
    )
    (net (code "62") (name "DRV07_F") (class "Default")
      (node (ref "U22") (pin "6") (pinfunction "6B_6") (pintype "unspecified"))
      (node (ref "U7") (pin "5") (pinfunction "QF_5") (pintype "unspecified"))
    )
    (net (code "63") (name "DRV07_SMA") (class "Default")
      (node (ref "U22") (pin "7") (pinfunction "7B_7") (pintype "unspecified"))
      (node (ref "U7") (pin "6") (pinfunction "QG_6") (pintype "unspecified"))
    )
    (net (code "64") (name "DRV08_A") (class "Default")
      (node (ref "U23") (pin "1") (pinfunction "1B_1") (pintype "unspecified"))
      (node (ref "U8") (pin "15") (pinfunction "QA_15") (pintype "unspecified"))
    )
    (net (code "65") (name "DRV08_B") (class "Default")
      (node (ref "U23") (pin "2") (pinfunction "2B_2") (pintype "unspecified"))
      (node (ref "U8") (pin "1") (pinfunction "QB_1") (pintype "unspecified"))
    )
    (net (code "66") (name "DRV08_C") (class "Default")
      (node (ref "U23") (pin "3") (pinfunction "3B_3") (pintype "unspecified"))
      (node (ref "U8") (pin "2") (pinfunction "QC_2") (pintype "unspecified"))
    )
    (net (code "67") (name "DRV08_D") (class "Default")
      (node (ref "U23") (pin "4") (pinfunction "4B_4") (pintype "unspecified"))
      (node (ref "U8") (pin "3") (pinfunction "QD_3") (pintype "unspecified"))
    )
    (net (code "68") (name "DRV08_E") (class "Default")
      (node (ref "U23") (pin "5") (pinfunction "5B_5") (pintype "unspecified"))
      (node (ref "U8") (pin "4") (pinfunction "QE_4") (pintype "unspecified"))
    )
    (net (code "69") (name "DRV08_F") (class "Default")
      (node (ref "U23") (pin "6") (pinfunction "6B_6") (pintype "unspecified"))
      (node (ref "U8") (pin "5") (pinfunction "QF_5") (pintype "unspecified"))
    )
    (net (code "70") (name "DRV08_SMA") (class "Default")
      (node (ref "U23") (pin "7") (pinfunction "7B_7") (pintype "unspecified"))
      (node (ref "U8") (pin "6") (pinfunction "QG_6") (pintype "unspecified"))
    )
    (net (code "71") (name "DRV09_A") (class "Default")
      (node (ref "U24") (pin "1") (pinfunction "1B_1") (pintype "unspecified"))
      (node (ref "U9") (pin "15") (pinfunction "QA_15") (pintype "unspecified"))
    )
    (net (code "72") (name "DRV09_B") (class "Default")
      (node (ref "U24") (pin "2") (pinfunction "2B_2") (pintype "unspecified"))
      (node (ref "U9") (pin "1") (pinfunction "QB_1") (pintype "unspecified"))
    )
    (net (code "73") (name "DRV09_C") (class "Default")
      (node (ref "U24") (pin "3") (pinfunction "3B_3") (pintype "unspecified"))
      (node (ref "U9") (pin "2") (pinfunction "QC_2") (pintype "unspecified"))
    )
    (net (code "74") (name "DRV09_D") (class "Default")
      (node (ref "U24") (pin "4") (pinfunction "4B_4") (pintype "unspecified"))
      (node (ref "U9") (pin "3") (pinfunction "QD_3") (pintype "unspecified"))
    )
    (net (code "75") (name "DRV09_E") (class "Default")
      (node (ref "U24") (pin "5") (pinfunction "5B_5") (pintype "unspecified"))
      (node (ref "U9") (pin "4") (pinfunction "QE_4") (pintype "unspecified"))
    )
    (net (code "76") (name "DRV09_F") (class "Default")
      (node (ref "U24") (pin "6") (pinfunction "6B_6") (pintype "unspecified"))
      (node (ref "U9") (pin "5") (pinfunction "QF_5") (pintype "unspecified"))
    )
    (net (code "77") (name "DRV09_SMA") (class "Default")
      (node (ref "U24") (pin "7") (pinfunction "7B_7") (pintype "unspecified"))
      (node (ref "U9") (pin "6") (pinfunction "QG_6") (pintype "unspecified"))
    )
    (net (code "78") (name "DRV10_A") (class "Default")
      (node (ref "U10") (pin "15") (pinfunction "QA_15") (pintype "unspecified"))
      (node (ref "U25") (pin "1") (pinfunction "1B_1") (pintype "unspecified"))
    )
    (net (code "79") (name "DRV10_B") (class "Default")
      (node (ref "U10") (pin "1") (pinfunction "QB_1") (pintype "unspecified"))
      (node (ref "U25") (pin "2") (pinfunction "2B_2") (pintype "unspecified"))
    )
    (net (code "80") (name "DRV10_C") (class "Default")
      (node (ref "U10") (pin "2") (pinfunction "QC_2") (pintype "unspecified"))
      (node (ref "U25") (pin "3") (pinfunction "3B_3") (pintype "unspecified"))
    )
    (net (code "81") (name "DRV10_D") (class "Default")
      (node (ref "U10") (pin "3") (pinfunction "QD_3") (pintype "unspecified"))
      (node (ref "U25") (pin "4") (pinfunction "4B_4") (pintype "unspecified"))
    )
    (net (code "82") (name "DRV10_E") (class "Default")
      (node (ref "U10") (pin "4") (pinfunction "QE_4") (pintype "unspecified"))
      (node (ref "U25") (pin "5") (pinfunction "5B_5") (pintype "unspecified"))
    )
    (net (code "83") (name "DRV10_F") (class "Default")
      (node (ref "U10") (pin "5") (pinfunction "QF_5") (pintype "unspecified"))
      (node (ref "U25") (pin "6") (pinfunction "6B_6") (pintype "unspecified"))
    )
    (net (code "84") (name "DRV10_SMA") (class "Default")
      (node (ref "U10") (pin "6") (pinfunction "QG_6") (pintype "unspecified"))
      (node (ref "U25") (pin "7") (pinfunction "7B_7") (pintype "unspecified"))
    )
    (net (code "85") (name "DRV11_A") (class "Default")
      (node (ref "U11") (pin "15") (pinfunction "QA_15") (pintype "unspecified"))
      (node (ref "U26") (pin "1") (pinfunction "1B_1") (pintype "unspecified"))
    )
    (net (code "86") (name "DRV11_B") (class "Default")
      (node (ref "U11") (pin "1") (pinfunction "QB_1") (pintype "unspecified"))
      (node (ref "U26") (pin "2") (pinfunction "2B_2") (pintype "unspecified"))
    )
    (net (code "87") (name "DRV11_C") (class "Default")
      (node (ref "U11") (pin "2") (pinfunction "QC_2") (pintype "unspecified"))
      (node (ref "U26") (pin "3") (pinfunction "3B_3") (pintype "unspecified"))
    )
    (net (code "88") (name "DRV11_D") (class "Default")
      (node (ref "U11") (pin "3") (pinfunction "QD_3") (pintype "unspecified"))
      (node (ref "U26") (pin "4") (pinfunction "4B_4") (pintype "unspecified"))
    )
    (net (code "89") (name "DRV11_E") (class "Default")
      (node (ref "U11") (pin "4") (pinfunction "QE_4") (pintype "unspecified"))
      (node (ref "U26") (pin "5") (pinfunction "5B_5") (pintype "unspecified"))
    )
    (net (code "90") (name "DRV11_F") (class "Default")
      (node (ref "U11") (pin "5") (pinfunction "QF_5") (pintype "unspecified"))
      (node (ref "U26") (pin "6") (pinfunction "6B_6") (pintype "unspecified"))
    )
    (net (code "91") (name "DRV11_SMA") (class "Default")
      (node (ref "U11") (pin "6") (pinfunction "QG_6") (pintype "unspecified"))
      (node (ref "U26") (pin "7") (pinfunction "7B_7") (pintype "unspecified"))
    )
    (net (code "92") (name "DRV12_A") (class "Default")
      (node (ref "U12") (pin "15") (pinfunction "QA_15") (pintype "unspecified"))
      (node (ref "U27") (pin "1") (pinfunction "1B_1") (pintype "unspecified"))
    )
    (net (code "93") (name "DRV12_B") (class "Default")
      (node (ref "U12") (pin "1") (pinfunction "QB_1") (pintype "unspecified"))
      (node (ref "U27") (pin "2") (pinfunction "2B_2") (pintype "unspecified"))
    )
    (net (code "94") (name "DRV12_C") (class "Default")
      (node (ref "U12") (pin "2") (pinfunction "QC_2") (pintype "unspecified"))
      (node (ref "U27") (pin "3") (pinfunction "3B_3") (pintype "unspecified"))
    )
    (net (code "95") (name "DRV12_D") (class "Default")
      (node (ref "U12") (pin "3") (pinfunction "QD_3") (pintype "unspecified"))
      (node (ref "U27") (pin "4") (pinfunction "4B_4") (pintype "unspecified"))
    )
    (net (code "96") (name "DRV12_E") (class "Default")
      (node (ref "U12") (pin "4") (pinfunction "QE_4") (pintype "unspecified"))
      (node (ref "U27") (pin "5") (pinfunction "5B_5") (pintype "unspecified"))
    )
    (net (code "97") (name "DRV12_F") (class "Default")
      (node (ref "U12") (pin "5") (pinfunction "QF_5") (pintype "unspecified"))
      (node (ref "U27") (pin "6") (pinfunction "6B_6") (pintype "unspecified"))
    )
    (net (code "98") (name "DRV12_SMA") (class "Default")
      (node (ref "U12") (pin "6") (pinfunction "QG_6") (pintype "unspecified"))
      (node (ref "U27") (pin "7") (pinfunction "7B_7") (pintype "unspecified"))
    )
    (net (code "99") (name "DRV13_A") (class "Default")
      (node (ref "U13") (pin "15") (pinfunction "QA_15") (pintype "unspecified"))
      (node (ref "U28") (pin "1") (pinfunction "1B_1") (pintype "unspecified"))
    )
    (net (code "100") (name "DRV13_B") (class "Default")
      (node (ref "U13") (pin "1") (pinfunction "QB_1") (pintype "unspecified"))
      (node (ref "U28") (pin "2") (pinfunction "2B_2") (pintype "unspecified"))
    )
    (net (code "101") (name "DRV13_C") (class "Default")
      (node (ref "U13") (pin "2") (pinfunction "QC_2") (pintype "unspecified"))
      (node (ref "U28") (pin "3") (pinfunction "3B_3") (pintype "unspecified"))
    )
    (net (code "102") (name "DRV13_D") (class "Default")
      (node (ref "U13") (pin "3") (pinfunction "QD_3") (pintype "unspecified"))
      (node (ref "U28") (pin "4") (pinfunction "4B_4") (pintype "unspecified"))
    )
    (net (code "103") (name "DRV13_E") (class "Default")
      (node (ref "U13") (pin "4") (pinfunction "QE_4") (pintype "unspecified"))
      (node (ref "U28") (pin "5") (pinfunction "5B_5") (pintype "unspecified"))
    )
    (net (code "104") (name "DRV13_F") (class "Default")
      (node (ref "U13") (pin "5") (pinfunction "QF_5") (pintype "unspecified"))
      (node (ref "U28") (pin "6") (pinfunction "6B_6") (pintype "unspecified"))
    )
    (net (code "105") (name "DRV13_SMA") (class "Default")
      (node (ref "U13") (pin "6") (pinfunction "QG_6") (pintype "unspecified"))
      (node (ref "U28") (pin "7") (pinfunction "7B_7") (pintype "unspecified"))
    )
    (net (code "106") (name "DRV14_A") (class "Default")
      (node (ref "U14") (pin "15") (pinfunction "QA_15") (pintype "unspecified"))
      (node (ref "U29") (pin "1") (pinfunction "1B_1") (pintype "unspecified"))
    )
    (net (code "107") (name "DRV14_B") (class "Default")
      (node (ref "U14") (pin "1") (pinfunction "QB_1") (pintype "unspecified"))
      (node (ref "U29") (pin "2") (pinfunction "2B_2") (pintype "unspecified"))
    )
    (net (code "108") (name "DRV14_C") (class "Default")
      (node (ref "U14") (pin "2") (pinfunction "QC_2") (pintype "unspecified"))
      (node (ref "U29") (pin "3") (pinfunction "3B_3") (pintype "unspecified"))
    )
    (net (code "109") (name "DRV14_D") (class "Default")
      (node (ref "U14") (pin "3") (pinfunction "QD_3") (pintype "unspecified"))
      (node (ref "U29") (pin "4") (pinfunction "4B_4") (pintype "unspecified"))
    )
    (net (code "110") (name "DRV14_E") (class "Default")
      (node (ref "U14") (pin "4") (pinfunction "QE_4") (pintype "unspecified"))
      (node (ref "U29") (pin "5") (pinfunction "5B_5") (pintype "unspecified"))
    )
    (net (code "111") (name "DRV14_F") (class "Default")
      (node (ref "U14") (pin "5") (pinfunction "QF_5") (pintype "unspecified"))
      (node (ref "U29") (pin "6") (pinfunction "6B_6") (pintype "unspecified"))
    )
    (net (code "112") (name "DRV14_SMA") (class "Default")
      (node (ref "U14") (pin "6") (pinfunction "QG_6") (pintype "unspecified"))
      (node (ref "U29") (pin "7") (pinfunction "7B_7") (pintype "unspecified"))
    )
    (net (code "113") (name "DRV15_A") (class "Default")
      (node (ref "U15") (pin "15") (pinfunction "QA_15") (pintype "unspecified"))
      (node (ref "U30") (pin "1") (pinfunction "1B_1") (pintype "unspecified"))
    )
    (net (code "114") (name "DRV15_B") (class "Default")
      (node (ref "U15") (pin "1") (pinfunction "QB_1") (pintype "unspecified"))
      (node (ref "U30") (pin "2") (pinfunction "2B_2") (pintype "unspecified"))
    )
    (net (code "115") (name "DRV15_C") (class "Default")
      (node (ref "U15") (pin "2") (pinfunction "QC_2") (pintype "unspecified"))
      (node (ref "U30") (pin "3") (pinfunction "3B_3") (pintype "unspecified"))
    )
    (net (code "116") (name "DRV15_D") (class "Default")
      (node (ref "U15") (pin "3") (pinfunction "QD_3") (pintype "unspecified"))
      (node (ref "U30") (pin "4") (pinfunction "4B_4") (pintype "unspecified"))
    )
    (net (code "117") (name "DRV15_E") (class "Default")
      (node (ref "U15") (pin "4") (pinfunction "QE_4") (pintype "unspecified"))
      (node (ref "U30") (pin "5") (pinfunction "5B_5") (pintype "unspecified"))
    )
    (net (code "118") (name "DRV15_F") (class "Default")
      (node (ref "U15") (pin "5") (pinfunction "QF_5") (pintype "unspecified"))
      (node (ref "U30") (pin "6") (pinfunction "6B_6") (pintype "unspecified"))
    )
    (net (code "119") (name "DRV15_SMA") (class "Default")
      (node (ref "U15") (pin "6") (pinfunction "QG_6") (pintype "unspecified"))
      (node (ref "U30") (pin "7") (pinfunction "7B_7") (pintype "unspecified"))
    )
    (net (code "120") (name "DRV16_A") (class "Default")
      (node (ref "U46") (pin "15") (pinfunction "QA_15") (pintype "unspecified"))
      (node (ref "U47") (pin "1") (pinfunction "1B_1") (pintype "unspecified"))
    )
    (net (code "121") (name "DRV16_B") (class "Default")
      (node (ref "U46") (pin "1") (pinfunction "QB_1") (pintype "unspecified"))
      (node (ref "U47") (pin "2") (pinfunction "2B_2") (pintype "unspecified"))
    )
    (net (code "122") (name "DRV16_C") (class "Default")
      (node (ref "U46") (pin "2") (pinfunction "QC_2") (pintype "unspecified"))
      (node (ref "U47") (pin "3") (pinfunction "3B_3") (pintype "unspecified"))
    )
    (net (code "123") (name "DRV16_D") (class "Default")
      (node (ref "U46") (pin "3") (pinfunction "QD_3") (pintype "unspecified"))
      (node (ref "U47") (pin "4") (pinfunction "4B_4") (pintype "unspecified"))
    )
    (net (code "124") (name "DRV16_E") (class "Default")
      (node (ref "U46") (pin "4") (pinfunction "QE_4") (pintype "unspecified"))
      (node (ref "U47") (pin "5") (pinfunction "5B_5") (pintype "unspecified"))
    )
    (net (code "125") (name "DRV16_F") (class "Default")
      (node (ref "U46") (pin "5") (pinfunction "QF_5") (pintype "unspecified"))
      (node (ref "U47") (pin "6") (pinfunction "6B_6") (pintype "unspecified"))
    )
    (net (code "126") (name "DRV16_SMA") (class "Default")
      (node (ref "U46") (pin "6") (pinfunction "QG_6") (pintype "unspecified"))
      (node (ref "U47") (pin "7") (pinfunction "7B_7") (pintype "unspecified"))
    )
    (net (code "127") (name "EN_MAIN") (class "Default")
      (node (ref "J_test") (pin "17") (pinfunction "17_17") (pintype "unspecified"))
      (node (ref "R3") (pin "1") (pinfunction "1_1") (pintype "input"))
      (node (ref "R36") (pin "1") (pinfunction "1_1") (pintype "unspecified"))
      (node (ref "R6") (pin "2") (pinfunction "2_2") (pintype "unspecified"))
      (node (ref "U49") (pin "8") (pinfunction "EN_8") (pintype "unspecified"))
      (node (ref "U51") (pin "14") (pinfunction "EN_14") (pintype "unspecified"))
      (node (ref "U54") (pin "10") (pinfunction "SEL3_10") (pintype "unspecified"))
      (node (ref "U54") (pin "13") (pinfunction "SEL4_13") (pintype "unspecified"))
      (node (ref "U55") (pin "1") (pinfunction "OUTA_1") (pintype "unspecified"))
    )
    (net (code "128") (name "EN_SMA") (class "Default")
      (node (ref "R37") (pin "1") (pinfunction "1_1") (pintype "unspecified"))
      (node (ref "U50") (pin "5") (pinfunction "EN_5") (pintype "unspecified"))
      (node (ref "U54") (pin "12") (pinfunction "S4_12") (pintype "unspecified"))
    )
    (net (code "129") (name "ESP_3V3") (class "Default")
      (node (ref "C90") (pin "1") (pinfunction "1_1") (pintype "unspecified"))
      (node (ref "J_ESP_L") (pin "1") (pinfunction "1_1") (pintype "unspecified"))
      (node (ref "J_ESP_L") (pin "2") (pinfunction "2_2") (pintype "unspecified"))
      (node (ref "J_test") (pin "6") (pinfunction "6_6") (pintype "unspecified"))
      (node (ref "R19") (pin "2") (pinfunction "2_2") (pintype "unspecified"))
      (node (ref "R32") (pin "2") (pinfunction "2_2") (pintype "input"))
      (node (ref "U54") (pin "14") (pinfunction "VDD_14") (pintype "unspecified"))
    )
    (net (code "130") (name "ESP_5V_RAW") (class "Default")
      (node (ref "C43") (pin "1") (pinfunction "1_1") (pintype "unspecified"))
      (node (ref "C84") (pin "1") (pinfunction "1_1") (pintype "unspecified"))
      (node (ref "U51") (pin "5") (pinfunction "FB_5") (pintype "unspecified"))
      (node (ref "U51") (pin "7") (pinfunction "VOUT_7") (pintype "unspecified"))
      (node (ref "U51") (pin "8") (pinfunction "VOUT_8") (pintype "unspecified"))
      (node (ref "U52") (pin "1") (pinfunction "VIN_1") (pintype "unspecified"))
    )
    (net (code "131") (name "ESP_SW1") (class "Default")
      (node (ref "L3") (pin "1") (pinfunction "1_1") (pintype "unspecified"))
      (node (ref "U51") (pin "11") (pinfunction "L1_11") (pintype "unspecified"))
    )
    (net (code "132") (name "ESP_SW2") (class "Default")
      (node (ref "L3") (pin "2") (pinfunction "2_2") (pintype "unspecified"))
      (node (ref "U51") (pin "9") (pinfunction "L2_9") (pintype "unspecified"))
    )
    (net (code "133") (name "ESP_VAUX") (class "Default")
      (node (ref "C82") (pin "2") (pinfunction "2_2") (pintype "unspecified"))
      (node (ref "U51") (pin "3") (pinfunction "VAUX_3") (pintype "unspecified"))
    )
    (net (code "134") (name "GND") (class "Default")
      (node (ref "C1") (pin "2") (pinfunction "2_2") (pintype "unspecified"))
      (node (ref "C10") (pin "2") (pinfunction "2_2") (pintype "unspecified"))
      (node (ref "C11") (pin "2") (pinfunction "2_2") (pintype "unspecified"))
      (node (ref "C12") (pin "2") (pinfunction "2_2") (pintype "unspecified"))
      (node (ref "C13") (pin "2") (pinfunction "2_2") (pintype "unspecified"))
      (node (ref "C14") (pin "2") (pinfunction "2_2") (pintype "unspecified"))
      (node (ref "C15") (pin "2") (pinfunction "2_2") (pintype "unspecified"))
      (node (ref "C2") (pin "2") (pinfunction "2_2") (pintype "unspecified"))
      (node (ref "C3") (pin "2") (pinfunction "2_2") (pintype "unspecified"))
      (node (ref "C31") (pin "2") (pinfunction "2_2") (pintype "unspecified"))
      (node (ref "C32") (pin "1") (pinfunction "1_1") (pintype "input"))
      (node (ref "C34") (pin "1") (pinfunction "1_1") (pintype "unspecified"))
      (node (ref "C36") (pin "2") (pinfunction "2_2") (pintype "unspecified"))
      (node (ref "C4") (pin "2") (pinfunction "2_2") (pintype "unspecified"))
      (node (ref "C40") (pin "2") (pinfunction "2_2") (pintype "unspecified"))
      (node (ref "C41") (pin "2") (pinfunction "2_2") (pintype "unspecified"))
      (node (ref "C43") (pin "2") (pinfunction "2_2") (pintype "unspecified"))
      (node (ref "C44") (pin "1") (pinfunction "1_1") (pintype "input"))
      (node (ref "C45") (pin "1") (pinfunction "1_1") (pintype "input"))
      (node (ref "C46") (pin "1") (pinfunction "1_1") (pintype "input"))
      (node (ref "C47") (pin "1") (pinfunction "1_1") (pintype "input"))
      (node (ref "C48") (pin "1") (pinfunction "1_1") (pintype "input"))
      (node (ref "C49") (pin "1") (pinfunction "1_1") (pintype "input"))
      (node (ref "C5") (pin "2") (pinfunction "2_2") (pintype "unspecified"))
      (node (ref "C50") (pin "1") (pinfunction "1_1") (pintype "input"))
      (node (ref "C51") (pin "1") (pinfunction "1_1") (pintype "input"))
      (node (ref "C52") (pin "1") (pinfunction "1_1") (pintype "input"))
      (node (ref "C53") (pin "1") (pinfunction "1_1") (pintype "input"))
      (node (ref "C54") (pin "1") (pinfunction "1_1") (pintype "input"))
      (node (ref "C55") (pin "1") (pinfunction "1_1") (pintype "input"))
      (node (ref "C56") (pin "1") (pinfunction "1_1") (pintype "input"))
      (node (ref "C57") (pin "1") (pinfunction "1_1") (pintype "input"))
      (node (ref "C58") (pin "1") (pinfunction "1_1") (pintype "input"))
      (node (ref "C59") (pin "1") (pinfunction "1_1") (pintype "unspecified"))
      (node (ref "C6") (pin "2") (pinfunction "2_2") (pintype "unspecified"))
      (node (ref "C60") (pin "1") (pinfunction "1_1") (pintype "unspecified"))
      (node (ref "C61") (pin "2") (pinfunction "2_2") (pintype "unspecified"))
      (node (ref "C62") (pin "1") (pinfunction "1_1") (pintype "unspecified"))
      (node (ref "C63") (pin "1") (pinfunction "1_1") (pintype "unspecified"))
      (node (ref "C65") (pin "2") (pinfunction "2_2") (pintype "unspecified"))
      (node (ref "C66") (pin "2") (pinfunction "2_2") (pintype "unspecified"))
      (node (ref "C67") (pin "2") (pinfunction "2_2") (pintype "unspecified"))
      (node (ref "C68") (pin "2") (pinfunction "2_2") (pintype "unspecified"))
      (node (ref "C69") (pin "1") (pinfunction "1_1") (pintype "input"))
      (node (ref "C7") (pin "2") (pinfunction "2_2") (pintype "unspecified"))
      (node (ref "C70") (pin "2") (pinfunction "2_2") (pintype "input"))
      (node (ref "C71") (pin "2") (pinfunction "2_2") (pintype "unspecified"))
      (node (ref "C74") (pin "2") (pinfunction "2_2") (pintype "input"))
      (node (ref "C75") (pin "2") (pinfunction "2_2") (pintype "input"))
      (node (ref "C76") (pin "2") (pinfunction "2_2") (pintype "input"))
      (node (ref "C77") (pin "2") (pinfunction "2_2") (pintype "input"))
      (node (ref "C78") (pin "2") (pinfunction "2_2") (pintype "input"))
      (node (ref "C79") (pin "2") (pinfunction "2_2") (pintype "input"))
      (node (ref "C8") (pin "2") (pinfunction "2_2") (pintype "unspecified"))
      (node (ref "C80") (pin "2") (pinfunction "2_2") (pintype "input"))
      (node (ref "C82") (pin "1") (pinfunction "1_1") (pintype "unspecified"))
      (node (ref "C83") (pin "2") (pinfunction "2_2") (pintype "unspecified"))
      (node (ref "C84") (pin "2") (pinfunction "2_2") (pintype "unspecified"))
      (node (ref "C86") (pin "2") (pinfunction "2_2") (pintype "input"))
      (node (ref "C87") (pin "2") (pinfunction "2_2") (pintype "unspecified"))
      (node (ref "C88") (pin "2") (pinfunction "2_2") (pintype "input"))
      (node (ref "C89") (pin "2") (pinfunction "2_2") (pintype "unspecified"))
      (node (ref "C9") (pin "2") (pinfunction "2_2") (pintype "unspecified"))
      (node (ref "C90") (pin "2") (pinfunction "2_2") (pintype "unspecified"))
      (node (ref "C91") (pin "2") (pinfunction "2_2") (pintype "unspecified"))
      (node (ref "D1") (pin "1") (pinfunction "C_1") (pintype "unspecified"))
      (node (ref "D2") (pin "1") (pinfunction "C_1") (pintype "unspecified"))
      (node (ref "J1") (pin "7") (pinfunction "EH_7") (pintype "unspecified"))
      (node (ref "J1") (pin "A12") (pinfunction "GND_A12") (pintype "unspecified"))
      (node (ref "J1") (pin "B12") (pinfunction "GND_B12") (pintype "unspecified"))
      (node (ref "J4") (pin "1") (pinfunction "1_1") (pintype "input"))
      (node (ref "J_ESP_L") (pin "22") (pinfunction "22_22") (pintype "unspecified"))
      (node (ref "J_ESP_R") (pin "1") (pinfunction "1_1") (pintype "unspecified"))
      (node (ref "J_NTC") (pin "2") (pinfunction "2_2") (pintype "unspecified"))
      (node (ref "J_test") (pin "12") (pinfunction "12_12") (pintype "unspecified"))
      (node (ref "J_test") (pin "2") (pinfunction "2_2") (pintype "unspecified"))
      (node (ref "J_test") (pin "22") (pinfunction "22_22") (pintype "unspecified"))
      (node (ref "J_test") (pin "4") (pinfunction "4_4") (pintype "unspecified"))
      (node (ref "J_test") (pin "9") (pinfunction "9_9") (pintype "unspecified"))
      (node (ref "R1") (pin "1") (pinfunction "1_1") (pintype "unspecified"))
      (node (ref "R10") (pin "2") (pinfunction "2_2") (pintype "input"))
      (node (ref "R15") (pin "1") (pinfunction "1_1") (pintype "unspecified"))
      (node (ref "R16") (pin "1") (pinfunction "1_1") (pintype "unspecified"))
      (node (ref "R17") (pin "1") (pinfunction "1_1") (pintype "unspecified"))
      (node (ref "R18") (pin "2") (pinfunction "2_2") (pintype "unspecified"))
      (node (ref "R2") (pin "1") (pinfunction "1_1") (pintype "unspecified"))
      (node (ref "R20") (pin "1") (pinfunction "1_1") (pintype "unspecified"))
      (node (ref "R21") (pin "1") (pinfunction "1_1") (pintype "unspecified"))
      (node (ref "R22") (pin "1") (pinfunction "1_1") (pintype "unspecified"))
      (node (ref "R3") (pin "2") (pinfunction "2_2") (pintype "input"))
      (node (ref "R31") (pin "1") (pinfunction "1_1") (pintype "unspecified"))
      (node (ref "R33") (pin "1") (pinfunction "1_1") (pintype "unspecified"))
      (node (ref "R35") (pin "2") (pinfunction "2_2") (pintype "input"))
      (node (ref "R37") (pin "2") (pinfunction "2_2") (pintype "unspecified"))
      (node (ref "R38") (pin "1") (pinfunction "1_1") (pintype "input"))
      (node (ref "R39") (pin "1") (pinfunction "1_1") (pintype "unspecified"))
      (node (ref "R40") (pin "2") (pinfunction "2_2") (pintype "input"))
      (node (ref "R41") (pin "2") (pinfunction "2_2") (pintype "input"))
      (node (ref "R42") (pin "2") (pinfunction "2_2") (pintype "input"))
      (node (ref "R8") (pin "1") (pinfunction "1_1") (pintype "input"))
      (node (ref "SW1") (pin "1") (pinfunction "1_1") (pintype "unspecified"))
      (node (ref "SW2") (pin "1") (pinfunction "1_1") (pintype "unspecified"))
      (node (ref "SW2") (pin "EH") (pinfunction "EH_EH") (pintype "unspecified"))
      (node (ref "U1") (pin "8") (pinfunction "GND_8") (pintype "unspecified"))
      (node (ref "U10") (pin "8") (pinfunction "GND_8") (pintype "unspecified"))
      (node (ref "U11") (pin "8") (pinfunction "GND_8") (pintype "unspecified"))
      (node (ref "U12") (pin "8") (pinfunction "GND_8") (pintype "unspecified"))
      (node (ref "U13") (pin "8") (pinfunction "GND_8") (pintype "unspecified"))
      (node (ref "U14") (pin "8") (pinfunction "GND_8") (pintype "unspecified"))
      (node (ref "U15") (pin "8") (pinfunction "GND_8") (pintype "unspecified"))
      (node (ref "U16") (pin "8") (pinfunction "E_8") (pintype "unspecified"))
      (node (ref "U17") (pin "8") (pinfunction "E_8") (pintype "unspecified"))
      (node (ref "U18") (pin "8") (pinfunction "E_8") (pintype "unspecified"))
      (node (ref "U19") (pin "8") (pinfunction "E_8") (pintype "unspecified"))
      (node (ref "U2") (pin "8") (pinfunction "GND_8") (pintype "unspecified"))
      (node (ref "U20") (pin "8") (pinfunction "E_8") (pintype "unspecified"))
      (node (ref "U21") (pin "8") (pinfunction "E_8") (pintype "unspecified"))
      (node (ref "U22") (pin "8") (pinfunction "E_8") (pintype "unspecified"))
      (node (ref "U23") (pin "8") (pinfunction "E_8") (pintype "unspecified"))
      (node (ref "U24") (pin "8") (pinfunction "E_8") (pintype "unspecified"))
      (node (ref "U25") (pin "8") (pinfunction "E_8") (pintype "unspecified"))
      (node (ref "U26") (pin "8") (pinfunction "E_8") (pintype "unspecified"))
      (node (ref "U27") (pin "8") (pinfunction "E_8") (pintype "unspecified"))
      (node (ref "U28") (pin "8") (pinfunction "E_8") (pintype "unspecified"))
      (node (ref "U29") (pin "8") (pinfunction "E_8") (pintype "unspecified"))
      (node (ref "U3") (pin "8") (pinfunction "GND_8") (pintype "unspecified"))
      (node (ref "U30") (pin "8") (pinfunction "E_8") (pintype "unspecified"))
      (node (ref "U4") (pin "8") (pinfunction "GND_8") (pintype "unspecified"))
      (node (ref "U46") (pin "8") (pinfunction "GND_8") (pintype "unspecified"))
      (node (ref "U47") (pin "8") (pinfunction "E_8") (pintype "unspecified"))
      (node (ref "U49") (pin "11") (pinfunction "PGND_11") (pintype "unspecified"))
      (node (ref "U49") (pin "12") (pinfunction "PGND_12") (pintype "unspecified"))
      (node (ref "U49") (pin "13") (pinfunction "PGND_13") (pintype "unspecified"))
      (node (ref "U49") (pin "14") (pinfunction "PGND_14") (pintype "unspecified"))
      (node (ref "U49") (pin "15") (pinfunction "PGND_15") (pintype "unspecified"))
      (node (ref "U49") (pin "16") (pinfunction "PGND_16") (pintype "unspecified"))
      (node (ref "U49") (pin "17") (pinfunction "PGND_17") (pintype "unspecified"))
      (node (ref "U49") (pin "18") (pinfunction "PGND_18") (pintype "unspecified"))
      (node (ref "U49") (pin "2") (pinfunction "AGND_2") (pintype "unspecified"))
      (node (ref "U49") (pin "6") (pinfunction "VSNS-_6") (pintype "unspecified"))
      (node (ref "U5") (pin "8") (pinfunction "GND_8") (pintype "unspecified"))
      (node (ref "U50") (pin "1") (pinfunction "GND_1") (pintype "unspecified"))
      (node (ref "U51") (pin "1") (pinfunction "PS/SYNC_1") (pintype "unspecified"))
      (node (ref "U51") (pin "10") (pinfunction "PGND_10") (pintype "unspecified"))
      (node (ref "U51") (pin "15") (pinfunction "VSEL_15") (pintype "unspecified"))
      (node (ref "U51") (pin "4") (pinfunction "GND_4") (pintype "unspecified"))
      (node (ref "U52") (pin "2") (pinfunction "GND_2") (pintype "unspecified"))
      (node (ref "U52") (pin "4") (pinfunction "NC_4") (pintype "unspecified"))
      (node (ref "U52") (pin "5") (pinfunction "ST_5") (pintype "unspecified"))
      (node (ref "U53") (pin "18") (pinfunction "PGND_18") (pintype "unspecified"))
      (node (ref "U53") (pin "25") (pinfunction "EP_25") (pintype "unspecified"))
      (node (ref "U54") (pin "7") (pinfunction "GND_7") (pintype "unspecified"))
      (node (ref "U54") (pin "8") (pinfunction "D3_8") (pintype "unspecified"))
      (node (ref "U55") (pin "2") (pinfunction "GND_2") (pintype "unspecified"))
      (node (ref "U55") (pin "4") (pinfunction "INB-_4") (pintype "unspecified"))
      (node (ref "U6") (pin "8") (pinfunction "GND_8") (pintype "unspecified"))
      (node (ref "U7") (pin "8") (pinfunction "GND_8") (pintype "unspecified"))
      (node (ref "U8") (pin "8") (pinfunction "GND_8") (pintype "unspecified"))
      (node (ref "U9") (pin "8") (pinfunction "GND_8") (pintype "unspecified"))
      (node (ref "deR28") (pin "1") (pinfunction "1_1") (pintype "unspecified"))
    )
    (net (code "135") (name "GPIO4") (class "Default")
      (node (ref "J_ESP_L") (pin "4") (pinfunction "4_4") (pintype "unspecified"))
      (node (ref "J_test") (pin "15") (pinfunction "15_15") (pintype "unspecified"))
      (node (ref "U54") (pin "3") (pinfunction "D1_3") (pintype "unspecified"))
    )
    (net (code "136") (name "GPIO6") (class "Default")
      (node (ref "J_ESP_L") (pin "6") (pinfunction "6_6") (pintype "unspecified"))
      (node (ref "SW1") (pin "3") (pinfunction "3_3") (pintype "unspecified"))
    )
    (net (code "137") (name "GPIO9_ENABLE") (class "Default")
      (node (ref "J_ESP_L") (pin "15") (pinfunction "15_15") (pintype "unspecified"))
      (node (ref "J_test") (pin "19") (pinfunction "19_19") (pintype "unspecified"))
      (node (ref "R31") (pin "2") (pinfunction "2_2") (pintype "unspecified"))
      (node (ref "U54") (pin "4") (pinfunction "SEL2_4") (pintype "unspecified"))
    )
    (net (code "138") (name "GPIO10_RCLK") (class "Default")
      (node (ref "J_ESP_L") (pin "16") (pinfunction "16_16") (pintype "unspecified"))
      (node (ref "R14") (pin "1") (pinfunction "1_1") (pintype "unspecified"))
    )
    (net (code "139") (name "GPIO11_SER") (class "Default")
      (node (ref "J_ESP_L") (pin "17") (pinfunction "17_17") (pintype "unspecified"))
      (node (ref "R5") (pin "1") (pinfunction "1_1") (pintype "unspecified"))
    )
    (net (code "140") (name "GPIO12_SRCLK") (class "Default")
      (node (ref "J_ESP_L") (pin "18") (pinfunction "18_18") (pintype "unspecified"))
      (node (ref "R13") (pin "1") (pinfunction "1_1") (pintype "unspecified"))
    )
    (net (code "141") (name "GPIO13") (class "Default")
      (node (ref "J_ESP_L") (pin "19") (pinfunction "19_19") (pintype "unspecified"))
      (node (ref "J_test") (pin "14") (pinfunction "14_14") (pintype "unspecified"))
      (node (ref "U46") (pin "9") (pinfunction "QH#_9") (pintype "unspecified"))
    )
    (net (code "142") (name "M1.PIN2") (class "Default")
      (node (ref "U16") (pin "16") (pinfunction "1C_16") (pintype "unspecified"))
      (node (ref "U31") (pin "2") (pinfunction "2_2") (pintype "unspecified"))
    )
    (net (code "143") (name "M1.PIN3") (class "Default")
      (node (ref "U16") (pin "10") (pinfunction "7C_10") (pintype "unspecified"))
      (node (ref "U31") (pin "3") (pinfunction "3_3") (pintype "unspecified"))
    )
    (net (code "144") (name "M1.PIN4") (class "Default")
      (node (ref "U16") (pin "15") (pinfunction "2C_15") (pintype "unspecified"))
      (node (ref "U31") (pin "4") (pinfunction "4_4") (pintype "unspecified"))
    )
    (net (code "145") (name "M1.PIN6") (class "Default")
      (node (ref "U16") (pin "14") (pinfunction "3C_14") (pintype "unspecified"))
      (node (ref "U31") (pin "6") (pinfunction "6_6") (pintype "unspecified"))
    )
    (net (code "146") (name "M1.PIN8") (class "Default")
      (node (ref "U16") (pin "13") (pinfunction "4C_13") (pintype "unspecified"))
      (node (ref "U31") (pin "8") (pinfunction "8_8") (pintype "unspecified"))
    )
    (net (code "147") (name "M1.PIN9") (class "Default")
      (node (ref "U16") (pin "12") (pinfunction "5C_12") (pintype "unspecified"))
      (node (ref "U31") (pin "9") (pinfunction "9_9") (pintype "unspecified"))
    )
    (net (code "148") (name "M1.PIN11") (class "Default")
      (node (ref "U16") (pin "11") (pinfunction "6C_11") (pintype "unspecified"))
      (node (ref "U31") (pin "11") (pinfunction "11_11") (pintype "unspecified"))
    )
    (net (code "149") (name "M2.PIN2") (class "Default")
      (node (ref "U17") (pin "16") (pinfunction "1C_16") (pintype "unspecified"))
      (node (ref "U32") (pin "2") (pinfunction "2_2") (pintype "unspecified"))
    )
    (net (code "150") (name "M2.PIN3") (class "Default")
      (node (ref "U17") (pin "10") (pinfunction "7C_10") (pintype "unspecified"))
      (node (ref "U32") (pin "3") (pinfunction "3_3") (pintype "unspecified"))
    )
    (net (code "151") (name "M2.PIN4") (class "Default")
      (node (ref "U17") (pin "15") (pinfunction "2C_15") (pintype "unspecified"))
      (node (ref "U32") (pin "4") (pinfunction "4_4") (pintype "unspecified"))
    )
    (net (code "152") (name "M2.PIN6") (class "Default")
      (node (ref "U17") (pin "14") (pinfunction "3C_14") (pintype "unspecified"))
      (node (ref "U32") (pin "6") (pinfunction "6_6") (pintype "unspecified"))
    )
    (net (code "153") (name "M2.PIN8") (class "Default")
      (node (ref "U17") (pin "13") (pinfunction "4C_13") (pintype "unspecified"))
      (node (ref "U32") (pin "8") (pinfunction "8_8") (pintype "unspecified"))
    )
    (net (code "154") (name "M2.PIN9") (class "Default")
      (node (ref "U17") (pin "12") (pinfunction "5C_12") (pintype "unspecified"))
      (node (ref "U32") (pin "9") (pinfunction "9_9") (pintype "unspecified"))
    )
    (net (code "155") (name "M2.PIN11") (class "Default")
      (node (ref "U17") (pin "11") (pinfunction "6C_11") (pintype "unspecified"))
      (node (ref "U32") (pin "11") (pinfunction "11_11") (pintype "unspecified"))
    )
    (net (code "156") (name "M3.PIN2") (class "Default")
      (node (ref "U18") (pin "16") (pinfunction "1C_16") (pintype "unspecified"))
      (node (ref "U33") (pin "2") (pinfunction "2_2") (pintype "unspecified"))
    )
    (net (code "157") (name "M3.PIN3") (class "Default")
      (node (ref "U18") (pin "10") (pinfunction "7C_10") (pintype "unspecified"))
      (node (ref "U33") (pin "3") (pinfunction "3_3") (pintype "unspecified"))
    )
    (net (code "158") (name "M3.PIN4") (class "Default")
      (node (ref "U18") (pin "15") (pinfunction "2C_15") (pintype "unspecified"))
      (node (ref "U33") (pin "4") (pinfunction "4_4") (pintype "unspecified"))
    )
    (net (code "159") (name "M3.PIN6") (class "Default")
      (node (ref "U18") (pin "14") (pinfunction "3C_14") (pintype "unspecified"))
      (node (ref "U33") (pin "6") (pinfunction "6_6") (pintype "unspecified"))
    )
    (net (code "160") (name "M3.PIN8") (class "Default")
      (node (ref "U18") (pin "13") (pinfunction "4C_13") (pintype "unspecified"))
      (node (ref "U33") (pin "8") (pinfunction "8_8") (pintype "unspecified"))
    )
    (net (code "161") (name "M3.PIN9") (class "Default")
      (node (ref "U18") (pin "12") (pinfunction "5C_12") (pintype "unspecified"))
      (node (ref "U33") (pin "9") (pinfunction "9_9") (pintype "unspecified"))
    )
    (net (code "162") (name "M3.PIN11") (class "Default")
      (node (ref "U18") (pin "11") (pinfunction "6C_11") (pintype "unspecified"))
      (node (ref "U33") (pin "11") (pinfunction "11_11") (pintype "unspecified"))
    )
    (net (code "163") (name "M4.PIN2") (class "Default")
      (node (ref "U19") (pin "16") (pinfunction "1C_16") (pintype "unspecified"))
      (node (ref "U34") (pin "2") (pinfunction "2_2") (pintype "unspecified"))
    )
    (net (code "164") (name "M4.PIN3") (class "Default")
      (node (ref "U19") (pin "10") (pinfunction "7C_10") (pintype "unspecified"))
      (node (ref "U34") (pin "3") (pinfunction "3_3") (pintype "unspecified"))
    )
    (net (code "165") (name "M4.PIN4") (class "Default")
      (node (ref "U19") (pin "15") (pinfunction "2C_15") (pintype "unspecified"))
      (node (ref "U34") (pin "4") (pinfunction "4_4") (pintype "unspecified"))
    )
    (net (code "166") (name "M4.PIN6") (class "Default")
      (node (ref "U19") (pin "14") (pinfunction "3C_14") (pintype "unspecified"))
      (node (ref "U34") (pin "6") (pinfunction "6_6") (pintype "unspecified"))
    )
    (net (code "167") (name "M4.PIN8") (class "Default")
      (node (ref "U19") (pin "13") (pinfunction "4C_13") (pintype "unspecified"))
      (node (ref "U34") (pin "8") (pinfunction "8_8") (pintype "unspecified"))
    )
    (net (code "168") (name "M4.PIN9") (class "Default")
      (node (ref "U19") (pin "12") (pinfunction "5C_12") (pintype "unspecified"))
      (node (ref "U34") (pin "9") (pinfunction "9_9") (pintype "unspecified"))
    )
    (net (code "169") (name "M4.PIN11") (class "Default")
      (node (ref "U19") (pin "11") (pinfunction "6C_11") (pintype "unspecified"))
      (node (ref "U34") (pin "11") (pinfunction "11_11") (pintype "unspecified"))
    )
    (net (code "170") (name "M5.PIN2") (class "Default")
      (node (ref "U20") (pin "16") (pinfunction "1C_16") (pintype "unspecified"))
      (node (ref "U35") (pin "2") (pinfunction "2_2") (pintype "unspecified"))
    )
    (net (code "171") (name "M5.PIN3") (class "Default")
      (node (ref "U20") (pin "10") (pinfunction "7C_10") (pintype "unspecified"))
      (node (ref "U35") (pin "3") (pinfunction "3_3") (pintype "unspecified"))
    )
    (net (code "172") (name "M5.PIN4") (class "Default")
      (node (ref "U20") (pin "15") (pinfunction "2C_15") (pintype "unspecified"))
      (node (ref "U35") (pin "4") (pinfunction "4_4") (pintype "unspecified"))
    )
    (net (code "173") (name "M5.PIN6") (class "Default")
      (node (ref "U20") (pin "14") (pinfunction "3C_14") (pintype "unspecified"))
      (node (ref "U35") (pin "6") (pinfunction "6_6") (pintype "unspecified"))
    )
    (net (code "174") (name "M5.PIN8") (class "Default")
      (node (ref "U20") (pin "13") (pinfunction "4C_13") (pintype "unspecified"))
      (node (ref "U35") (pin "8") (pinfunction "8_8") (pintype "unspecified"))
    )
    (net (code "175") (name "M5.PIN9") (class "Default")
      (node (ref "U20") (pin "12") (pinfunction "5C_12") (pintype "unspecified"))
      (node (ref "U35") (pin "9") (pinfunction "9_9") (pintype "unspecified"))
    )
    (net (code "176") (name "M5.PIN11") (class "Default")
      (node (ref "U20") (pin "11") (pinfunction "6C_11") (pintype "unspecified"))
      (node (ref "U35") (pin "11") (pinfunction "11_11") (pintype "unspecified"))
    )
    (net (code "177") (name "M6.PIN2") (class "Default")
      (node (ref "U21") (pin "16") (pinfunction "1C_16") (pintype "unspecified"))
      (node (ref "U36") (pin "2") (pinfunction "2_2") (pintype "unspecified"))
    )
    (net (code "178") (name "M6.PIN3") (class "Default")
      (node (ref "U21") (pin "10") (pinfunction "7C_10") (pintype "unspecified"))
      (node (ref "U36") (pin "3") (pinfunction "3_3") (pintype "unspecified"))
    )
    (net (code "179") (name "M6.PIN4") (class "Default")
      (node (ref "U21") (pin "15") (pinfunction "2C_15") (pintype "unspecified"))
      (node (ref "U36") (pin "4") (pinfunction "4_4") (pintype "unspecified"))
    )
    (net (code "180") (name "M6.PIN6") (class "Default")
      (node (ref "U21") (pin "14") (pinfunction "3C_14") (pintype "unspecified"))
      (node (ref "U36") (pin "6") (pinfunction "6_6") (pintype "unspecified"))
    )
    (net (code "181") (name "M6.PIN8") (class "Default")
      (node (ref "U21") (pin "13") (pinfunction "4C_13") (pintype "unspecified"))
      (node (ref "U36") (pin "8") (pinfunction "8_8") (pintype "unspecified"))
    )
    (net (code "182") (name "M6.PIN9") (class "Default")
      (node (ref "U21") (pin "12") (pinfunction "5C_12") (pintype "unspecified"))
      (node (ref "U36") (pin "9") (pinfunction "9_9") (pintype "unspecified"))
    )
    (net (code "183") (name "M6.PIN11") (class "Default")
      (node (ref "U21") (pin "11") (pinfunction "6C_11") (pintype "unspecified"))
      (node (ref "U36") (pin "11") (pinfunction "11_11") (pintype "unspecified"))
    )
    (net (code "184") (name "M7.PIN2") (class "Default")
      (node (ref "U22") (pin "16") (pinfunction "1C_16") (pintype "unspecified"))
      (node (ref "U37") (pin "2") (pinfunction "2_2") (pintype "unspecified"))
    )
    (net (code "185") (name "M7.PIN3") (class "Default")
      (node (ref "U22") (pin "10") (pinfunction "7C_10") (pintype "unspecified"))
      (node (ref "U37") (pin "3") (pinfunction "3_3") (pintype "unspecified"))
    )
    (net (code "186") (name "M7.PIN4") (class "Default")
      (node (ref "U22") (pin "15") (pinfunction "2C_15") (pintype "unspecified"))
      (node (ref "U37") (pin "4") (pinfunction "4_4") (pintype "unspecified"))
    )
    (net (code "187") (name "M7.PIN6") (class "Default")
      (node (ref "U22") (pin "14") (pinfunction "3C_14") (pintype "unspecified"))
      (node (ref "U37") (pin "6") (pinfunction "6_6") (pintype "unspecified"))
    )
    (net (code "188") (name "M7.PIN8") (class "Default")
      (node (ref "U22") (pin "13") (pinfunction "4C_13") (pintype "unspecified"))
      (node (ref "U37") (pin "8") (pinfunction "8_8") (pintype "unspecified"))
    )
    (net (code "189") (name "M7.PIN9") (class "Default")
      (node (ref "U22") (pin "12") (pinfunction "5C_12") (pintype "unspecified"))
      (node (ref "U37") (pin "9") (pinfunction "9_9") (pintype "unspecified"))
    )
    (net (code "190") (name "M7.PIN11") (class "Default")
      (node (ref "U22") (pin "11") (pinfunction "6C_11") (pintype "unspecified"))
      (node (ref "U37") (pin "11") (pinfunction "11_11") (pintype "unspecified"))
    )
    (net (code "191") (name "M8.PIN2") (class "Default")
      (node (ref "U23") (pin "16") (pinfunction "1C_16") (pintype "unspecified"))
      (node (ref "U38") (pin "2") (pinfunction "2_2") (pintype "unspecified"))
    )
    (net (code "192") (name "M8.PIN3") (class "Default")
      (node (ref "U23") (pin "10") (pinfunction "7C_10") (pintype "unspecified"))
      (node (ref "U38") (pin "3") (pinfunction "3_3") (pintype "unspecified"))
    )
    (net (code "193") (name "M8.PIN4") (class "Default")
      (node (ref "U23") (pin "15") (pinfunction "2C_15") (pintype "unspecified"))
      (node (ref "U38") (pin "4") (pinfunction "4_4") (pintype "unspecified"))
    )
    (net (code "194") (name "M8.PIN6") (class "Default")
      (node (ref "U23") (pin "14") (pinfunction "3C_14") (pintype "unspecified"))
      (node (ref "U38") (pin "6") (pinfunction "6_6") (pintype "unspecified"))
    )
    (net (code "195") (name "M8.PIN8") (class "Default")
      (node (ref "U23") (pin "13") (pinfunction "4C_13") (pintype "unspecified"))
      (node (ref "U38") (pin "8") (pinfunction "8_8") (pintype "unspecified"))
    )
    (net (code "196") (name "M8.PIN9") (class "Default")
      (node (ref "U23") (pin "12") (pinfunction "5C_12") (pintype "unspecified"))
      (node (ref "U38") (pin "9") (pinfunction "9_9") (pintype "unspecified"))
    )
    (net (code "197") (name "M8.PIN11") (class "Default")
      (node (ref "U23") (pin "11") (pinfunction "6C_11") (pintype "unspecified"))
      (node (ref "U38") (pin "11") (pinfunction "11_11") (pintype "unspecified"))
    )
    (net (code "198") (name "M9.PIN2") (class "Default")
      (node (ref "U24") (pin "16") (pinfunction "1C_16") (pintype "unspecified"))
      (node (ref "U39") (pin "2") (pinfunction "2_2") (pintype "unspecified"))
    )
    (net (code "199") (name "M9.PIN3") (class "Default")
      (node (ref "U24") (pin "10") (pinfunction "7C_10") (pintype "unspecified"))
      (node (ref "U39") (pin "3") (pinfunction "3_3") (pintype "unspecified"))
    )
    (net (code "200") (name "M9.PIN4") (class "Default")
      (node (ref "U24") (pin "15") (pinfunction "2C_15") (pintype "unspecified"))
      (node (ref "U39") (pin "4") (pinfunction "4_4") (pintype "unspecified"))
    )
    (net (code "201") (name "M9.PIN6") (class "Default")
      (node (ref "U24") (pin "14") (pinfunction "3C_14") (pintype "unspecified"))
      (node (ref "U39") (pin "6") (pinfunction "6_6") (pintype "unspecified"))
    )
    (net (code "202") (name "M9.PIN8") (class "Default")
      (node (ref "U24") (pin "13") (pinfunction "4C_13") (pintype "unspecified"))
      (node (ref "U39") (pin "8") (pinfunction "8_8") (pintype "unspecified"))
    )
    (net (code "203") (name "M9.PIN9") (class "Default")
      (node (ref "U24") (pin "12") (pinfunction "5C_12") (pintype "unspecified"))
      (node (ref "U39") (pin "9") (pinfunction "9_9") (pintype "unspecified"))
    )
    (net (code "204") (name "M9.PIN11") (class "Default")
      (node (ref "U24") (pin "11") (pinfunction "6C_11") (pintype "unspecified"))
      (node (ref "U39") (pin "11") (pinfunction "11_11") (pintype "unspecified"))
    )
    (net (code "205") (name "M10.PIN2") (class "Default")
      (node (ref "U25") (pin "16") (pinfunction "1C_16") (pintype "unspecified"))
      (node (ref "U40") (pin "2") (pinfunction "2_2") (pintype "unspecified"))
    )
    (net (code "206") (name "M10.PIN3") (class "Default")
      (node (ref "U25") (pin "10") (pinfunction "7C_10") (pintype "unspecified"))
      (node (ref "U40") (pin "3") (pinfunction "3_3") (pintype "unspecified"))
    )
    (net (code "207") (name "M10.PIN4") (class "Default")
      (node (ref "U25") (pin "15") (pinfunction "2C_15") (pintype "unspecified"))
      (node (ref "U40") (pin "4") (pinfunction "4_4") (pintype "unspecified"))
    )
    (net (code "208") (name "M10.PIN6") (class "Default")
      (node (ref "U25") (pin "14") (pinfunction "3C_14") (pintype "unspecified"))
      (node (ref "U40") (pin "6") (pinfunction "6_6") (pintype "unspecified"))
    )
    (net (code "209") (name "M10.PIN8") (class "Default")
      (node (ref "U25") (pin "13") (pinfunction "4C_13") (pintype "unspecified"))
      (node (ref "U40") (pin "8") (pinfunction "8_8") (pintype "unspecified"))
    )
    (net (code "210") (name "M10.PIN9") (class "Default")
      (node (ref "U25") (pin "12") (pinfunction "5C_12") (pintype "unspecified"))
      (node (ref "U40") (pin "9") (pinfunction "9_9") (pintype "unspecified"))
    )
    (net (code "211") (name "M10.PIN11") (class "Default")
      (node (ref "U25") (pin "11") (pinfunction "6C_11") (pintype "unspecified"))
      (node (ref "U40") (pin "11") (pinfunction "11_11") (pintype "unspecified"))
    )
    (net (code "212") (name "M11.PIN2") (class "Default")
      (node (ref "U26") (pin "16") (pinfunction "1C_16") (pintype "unspecified"))
      (node (ref "U41") (pin "2") (pinfunction "2_2") (pintype "unspecified"))
    )
    (net (code "213") (name "M11.PIN3") (class "Default")
      (node (ref "U26") (pin "10") (pinfunction "7C_10") (pintype "unspecified"))
      (node (ref "U41") (pin "3") (pinfunction "3_3") (pintype "unspecified"))
    )
    (net (code "214") (name "M11.PIN4") (class "Default")
      (node (ref "U26") (pin "15") (pinfunction "2C_15") (pintype "unspecified"))
      (node (ref "U41") (pin "4") (pinfunction "4_4") (pintype "unspecified"))
    )
    (net (code "215") (name "M11.PIN6") (class "Default")
      (node (ref "U26") (pin "14") (pinfunction "3C_14") (pintype "unspecified"))
      (node (ref "U41") (pin "6") (pinfunction "6_6") (pintype "unspecified"))
    )
    (net (code "216") (name "M11.PIN8") (class "Default")
      (node (ref "U26") (pin "13") (pinfunction "4C_13") (pintype "unspecified"))
      (node (ref "U41") (pin "8") (pinfunction "8_8") (pintype "unspecified"))
    )
    (net (code "217") (name "M11.PIN9") (class "Default")
      (node (ref "U26") (pin "12") (pinfunction "5C_12") (pintype "unspecified"))
      (node (ref "U41") (pin "9") (pinfunction "9_9") (pintype "unspecified"))
    )
    (net (code "218") (name "M11.PIN11") (class "Default")
      (node (ref "U26") (pin "11") (pinfunction "6C_11") (pintype "unspecified"))
      (node (ref "U41") (pin "11") (pinfunction "11_11") (pintype "unspecified"))
    )
    (net (code "219") (name "M12.PIN2") (class "Default")
      (node (ref "U27") (pin "16") (pinfunction "1C_16") (pintype "unspecified"))
      (node (ref "U42") (pin "2") (pinfunction "2_2") (pintype "unspecified"))
    )
    (net (code "220") (name "M12.PIN3") (class "Default")
      (node (ref "U27") (pin "10") (pinfunction "7C_10") (pintype "unspecified"))
      (node (ref "U42") (pin "3") (pinfunction "3_3") (pintype "unspecified"))
    )
    (net (code "221") (name "M12.PIN4") (class "Default")
      (node (ref "U27") (pin "15") (pinfunction "2C_15") (pintype "unspecified"))
      (node (ref "U42") (pin "4") (pinfunction "4_4") (pintype "unspecified"))
    )
    (net (code "222") (name "M12.PIN6") (class "Default")
      (node (ref "U27") (pin "14") (pinfunction "3C_14") (pintype "unspecified"))
      (node (ref "U42") (pin "6") (pinfunction "6_6") (pintype "unspecified"))
    )
    (net (code "223") (name "M12.PIN8") (class "Default")
      (node (ref "U27") (pin "13") (pinfunction "4C_13") (pintype "unspecified"))
      (node (ref "U42") (pin "8") (pinfunction "8_8") (pintype "unspecified"))
    )
    (net (code "224") (name "M12.PIN9") (class "Default")
      (node (ref "U27") (pin "12") (pinfunction "5C_12") (pintype "unspecified"))
      (node (ref "U42") (pin "9") (pinfunction "9_9") (pintype "unspecified"))
    )
    (net (code "225") (name "M12.PIN11") (class "Default")
      (node (ref "U27") (pin "11") (pinfunction "6C_11") (pintype "unspecified"))
      (node (ref "U42") (pin "11") (pinfunction "11_11") (pintype "unspecified"))
    )
    (net (code "226") (name "M13.PIN2") (class "Default")
      (node (ref "U28") (pin "16") (pinfunction "1C_16") (pintype "unspecified"))
      (node (ref "U43") (pin "2") (pinfunction "2_2") (pintype "unspecified"))
    )
    (net (code "227") (name "M13.PIN3") (class "Default")
      (node (ref "U28") (pin "10") (pinfunction "7C_10") (pintype "unspecified"))
      (node (ref "U43") (pin "3") (pinfunction "3_3") (pintype "unspecified"))
    )
    (net (code "228") (name "M13.PIN4") (class "Default")
      (node (ref "U28") (pin "15") (pinfunction "2C_15") (pintype "unspecified"))
      (node (ref "U43") (pin "4") (pinfunction "4_4") (pintype "unspecified"))
    )
    (net (code "229") (name "M13.PIN6") (class "Default")
      (node (ref "U28") (pin "14") (pinfunction "3C_14") (pintype "unspecified"))
      (node (ref "U43") (pin "6") (pinfunction "6_6") (pintype "unspecified"))
    )
    (net (code "230") (name "M13.PIN8") (class "Default")
      (node (ref "U28") (pin "13") (pinfunction "4C_13") (pintype "unspecified"))
      (node (ref "U43") (pin "8") (pinfunction "8_8") (pintype "unspecified"))
    )
    (net (code "231") (name "M13.PIN9") (class "Default")
      (node (ref "U28") (pin "12") (pinfunction "5C_12") (pintype "unspecified"))
      (node (ref "U43") (pin "9") (pinfunction "9_9") (pintype "unspecified"))
    )
    (net (code "232") (name "M13.PIN11") (class "Default")
      (node (ref "U28") (pin "11") (pinfunction "6C_11") (pintype "unspecified"))
      (node (ref "U43") (pin "11") (pinfunction "11_11") (pintype "unspecified"))
    )
    (net (code "233") (name "M14.PIN2") (class "Default")
      (node (ref "U29") (pin "16") (pinfunction "1C_16") (pintype "unspecified"))
      (node (ref "U44") (pin "2") (pinfunction "2_2") (pintype "unspecified"))
    )
    (net (code "234") (name "M14.PIN3") (class "Default")
      (node (ref "U29") (pin "10") (pinfunction "7C_10") (pintype "unspecified"))
      (node (ref "U44") (pin "3") (pinfunction "3_3") (pintype "unspecified"))
    )
    (net (code "235") (name "M14.PIN4") (class "Default")
      (node (ref "U29") (pin "15") (pinfunction "2C_15") (pintype "unspecified"))
      (node (ref "U44") (pin "4") (pinfunction "4_4") (pintype "unspecified"))
    )
    (net (code "236") (name "M14.PIN6") (class "Default")
      (node (ref "U29") (pin "14") (pinfunction "3C_14") (pintype "unspecified"))
      (node (ref "U44") (pin "6") (pinfunction "6_6") (pintype "unspecified"))
    )
    (net (code "237") (name "M14.PIN8") (class "Default")
      (node (ref "U29") (pin "13") (pinfunction "4C_13") (pintype "unspecified"))
      (node (ref "U44") (pin "8") (pinfunction "8_8") (pintype "unspecified"))
    )
    (net (code "238") (name "M14.PIN9") (class "Default")
      (node (ref "U29") (pin "12") (pinfunction "5C_12") (pintype "unspecified"))
      (node (ref "U44") (pin "9") (pinfunction "9_9") (pintype "unspecified"))
    )
    (net (code "239") (name "M14.PIN11") (class "Default")
      (node (ref "U29") (pin "11") (pinfunction "6C_11") (pintype "unspecified"))
      (node (ref "U44") (pin "11") (pinfunction "11_11") (pintype "unspecified"))
    )
    (net (code "240") (name "M15.PIN2") (class "Default")
      (node (ref "U30") (pin "16") (pinfunction "1C_16") (pintype "unspecified"))
      (node (ref "U45") (pin "2") (pinfunction "2_2") (pintype "unspecified"))
    )
    (net (code "241") (name "M15.PIN3") (class "Default")
      (node (ref "U30") (pin "10") (pinfunction "7C_10") (pintype "unspecified"))
      (node (ref "U45") (pin "3") (pinfunction "3_3") (pintype "unspecified"))
    )
    (net (code "242") (name "M15.PIN4") (class "Default")
      (node (ref "U30") (pin "15") (pinfunction "2C_15") (pintype "unspecified"))
      (node (ref "U45") (pin "4") (pinfunction "4_4") (pintype "unspecified"))
    )
    (net (code "243") (name "M15.PIN6") (class "Default")
      (node (ref "U30") (pin "14") (pinfunction "3C_14") (pintype "unspecified"))
      (node (ref "U45") (pin "6") (pinfunction "6_6") (pintype "unspecified"))
    )
    (net (code "244") (name "M15.PIN8") (class "Default")
      (node (ref "U30") (pin "13") (pinfunction "4C_13") (pintype "unspecified"))
      (node (ref "U45") (pin "8") (pinfunction "8_8") (pintype "unspecified"))
    )
    (net (code "245") (name "M15.PIN9") (class "Default")
      (node (ref "U30") (pin "12") (pinfunction "5C_12") (pintype "unspecified"))
      (node (ref "U45") (pin "9") (pinfunction "9_9") (pintype "unspecified"))
    )
    (net (code "246") (name "M15.PIN11") (class "Default")
      (node (ref "U30") (pin "11") (pinfunction "6C_11") (pintype "unspecified"))
      (node (ref "U45") (pin "11") (pinfunction "11_11") (pintype "unspecified"))
    )
    (net (code "247") (name "M16.PIN2") (class "Default")
      (node (ref "U47") (pin "16") (pinfunction "1C_16") (pintype "unspecified"))
      (node (ref "U48") (pin "2") (pinfunction "2_2") (pintype "unspecified"))
    )
    (net (code "248") (name "M16.PIN3") (class "Default")
      (node (ref "U47") (pin "10") (pinfunction "7C_10") (pintype "unspecified"))
      (node (ref "U48") (pin "3") (pinfunction "3_3") (pintype "unspecified"))
    )
    (net (code "249") (name "M16.PIN4") (class "Default")
      (node (ref "U47") (pin "15") (pinfunction "2C_15") (pintype "unspecified"))
      (node (ref "U48") (pin "4") (pinfunction "4_4") (pintype "unspecified"))
    )
    (net (code "250") (name "M16.PIN6") (class "Default")
      (node (ref "U47") (pin "14") (pinfunction "3C_14") (pintype "unspecified"))
      (node (ref "U48") (pin "6") (pinfunction "6_6") (pintype "unspecified"))
    )
    (net (code "251") (name "M16.PIN8") (class "Default")
      (node (ref "U47") (pin "13") (pinfunction "4C_13") (pintype "unspecified"))
      (node (ref "U48") (pin "8") (pinfunction "8_8") (pintype "unspecified"))
    )
    (net (code "252") (name "M16.PIN9") (class "Default")
      (node (ref "U47") (pin "12") (pinfunction "5C_12") (pintype "unspecified"))
      (node (ref "U48") (pin "9") (pinfunction "9_9") (pintype "unspecified"))
    )
    (net (code "253") (name "M16.PIN11") (class "Default")
      (node (ref "U47") (pin "11") (pinfunction "6C_11") (pintype "unspecified"))
      (node (ref "U48") (pin "11") (pinfunction "11_11") (pintype "unspecified"))
    )
    (net (code "254") (name "MAIN_BST") (class "Default")
      (node (ref "C33") (pin "2") (pinfunction "2_2") (pintype "unspecified"))
      (node (ref "U49") (pin "1") (pinfunction "BST_1") (pintype "unspecified"))
    )
    (net (code "255") (name "MAIN_FB") (class "Default")
      (node (ref "C72") (pin "2") (pinfunction "2_2") (pintype "unspecified"))
      (node (ref "R7") (pin "2") (pinfunction "2_2") (pintype "unspecified"))
      (node (ref "R8") (pin "2") (pinfunction "2_2") (pintype "input"))
      (node (ref "U49") (pin "7") (pinfunction "FB_7") (pintype "unspecified"))
    )
    (net (code "256") (name "MAIN_ILIM") (class "Default")
      (node (ref "R1") (pin "2") (pinfunction "2_2") (pintype "unspecified"))
      (node (ref "U49") (pin "3") (pinfunction "CS_3") (pintype "unspecified"))
    )
    (net (code "257") (name "MAIN_MODE") (class "Default")
      (node (ref "R38") (pin "2") (pinfunction "2_2") (pintype "input"))
      (node (ref "U49") (pin "4") (pinfunction "MODE_4") (pintype "unspecified"))
    )
    (net (code "258") (name "MAIN_SS") (class "Default")
      (node (ref "C34") (pin "2") (pinfunction "2_2") (pintype "unspecified"))
      (node (ref "U49") (pin "5") (pinfunction "REF/TRK_5") (pintype "unspecified"))
    )
    (net (code "259") (name "MAIN_SW") (class "Default")
      (node (ref "C33") (pin "1") (pinfunction "1_1") (pintype "unspecified"))
      (node (ref "L1") (pin "1") (pinfunction "1_1") (pintype "unspecified"))
      (node (ref "U49") (pin "20") (pinfunction "SW_20") (pintype "unspecified"))
    )
    (net (code "260") (name "MAIN_VCC_INT") (class "Default")
      (node (ref "C71") (pin "1") (pinfunction "1_1") (pintype "unspecified"))
      (node (ref "U49") (pin "19") (pinfunction "VCC_19") (pintype "unspecified"))
    )
    (net (code "261") (name "OE#") (class "Default")
      (node (ref "J_test") (pin "18") (pinfunction "18_18") (pintype "unspecified"))
      (node (ref "R11") (pin "1") (pinfunction "1_1") (pintype "input"))
      (node (ref "U1") (pin "13") (pinfunction "OE#_13") (pintype "unspecified"))
      (node (ref "U10") (pin "13") (pinfunction "OE#_13") (pintype "unspecified"))
      (node (ref "U11") (pin "13") (pinfunction "OE#_13") (pintype "unspecified"))
      (node (ref "U12") (pin "13") (pinfunction "OE#_13") (pintype "unspecified"))
      (node (ref "U13") (pin "13") (pinfunction "OE#_13") (pintype "unspecified"))
      (node (ref "U14") (pin "13") (pinfunction "OE#_13") (pintype "unspecified"))
      (node (ref "U15") (pin "13") (pinfunction "OE#_13") (pintype "unspecified"))
      (node (ref "U2") (pin "13") (pinfunction "OE#_13") (pintype "unspecified"))
      (node (ref "U3") (pin "13") (pinfunction "OE#_13") (pintype "unspecified"))
      (node (ref "U4") (pin "13") (pinfunction "OE#_13") (pintype "unspecified"))
      (node (ref "U46") (pin "13") (pinfunction "OE#_13") (pintype "unspecified"))
      (node (ref "U5") (pin "13") (pinfunction "OE#_13") (pintype "unspecified"))
      (node (ref "U54") (pin "5") (pinfunction "S2_5") (pintype "unspecified"))
      (node (ref "U6") (pin "13") (pinfunction "OE#_13") (pintype "unspecified"))
      (node (ref "U7") (pin "13") (pinfunction "OE#_13") (pintype "unspecified"))
      (node (ref "U8") (pin "13") (pinfunction "OE#_13") (pintype "unspecified"))
      (node (ref "U9") (pin "13") (pinfunction "OE#_13") (pintype "unspecified"))
    )
    (net (code "262") (name "OE_GATE_MID") (class "Default")
      (node (ref "U54") (pin "6") (pinfunction "D2_6") (pintype "unspecified"))
      (node (ref "U54") (pin "9") (pinfunction "S3_9") (pintype "unspecified"))
    )
    (net (code "263") (name "PGOOD") (class "Default")
      (node (ref "J_ESP_L") (pin "20") (pinfunction "20_20") (pintype "unspecified"))
      (node (ref "J_test") (pin "21") (pinfunction "21_21") (pintype "unspecified"))
      (node (ref "R32") (pin "1") (pinfunction "1_1") (pintype "input"))
      (node (ref "U49") (pin "9") (pinfunction "PGOOD_9") (pintype "unspecified"))
      (node (ref "U54") (pin "11") (pinfunction "D4_11") (pintype "unspecified"))
    )
    (net (code "264") (name "RCLK") (class "Default")
      (node (ref "J_test") (pin "16") (pinfunction "16_16") (pintype "unspecified"))
      (node (ref "R14") (pin "2") (pinfunction "2_2") (pintype "unspecified"))
      (node (ref "R42") (pin "1") (pinfunction "1_1") (pintype "input"))
      (node (ref "U1") (pin "12") (pinfunction "RCLK_12") (pintype "unspecified"))
      (node (ref "U10") (pin "12") (pinfunction "RCLK_12") (pintype "unspecified"))
      (node (ref "U11") (pin "12") (pinfunction "RCLK_12") (pintype "unspecified"))
      (node (ref "U12") (pin "12") (pinfunction "RCLK_12") (pintype "unspecified"))
      (node (ref "U13") (pin "12") (pinfunction "RCLK_12") (pintype "unspecified"))
      (node (ref "U14") (pin "12") (pinfunction "RCLK_12") (pintype "unspecified"))
      (node (ref "U15") (pin "12") (pinfunction "RCLK_12") (pintype "unspecified"))
      (node (ref "U2") (pin "12") (pinfunction "RCLK_12") (pintype "unspecified"))
      (node (ref "U3") (pin "12") (pinfunction "RCLK_12") (pintype "unspecified"))
      (node (ref "U4") (pin "12") (pinfunction "RCLK_12") (pintype "unspecified"))
      (node (ref "U46") (pin "12") (pinfunction "RCLK_12") (pintype "unspecified"))
      (node (ref "U5") (pin "12") (pinfunction "RCLK_12") (pintype "unspecified"))
      (node (ref "U6") (pin "12") (pinfunction "RCLK_12") (pintype "unspecified"))
      (node (ref "U7") (pin "12") (pinfunction "RCLK_12") (pintype "unspecified"))
      (node (ref "U8") (pin "12") (pinfunction "RCLK_12") (pintype "unspecified"))
      (node (ref "U9") (pin "12") (pinfunction "RCLK_12") (pintype "unspecified"))
    )
    (net (code "265") (name "REVERSE_GATE") (class "Default")
      (node (ref "Q1") (pin "4") (pinfunction "G_4") (pintype "unspecified"))
      (node (ref "R2") (pin "2") (pinfunction "2_2") (pintype "unspecified"))
    )
    (net (code "266") (name "RUN_LED_A") (class "Default")
      (node (ref "D2") (pin "2") (pinfunction "A_2") (pintype "unspecified"))
      (node (ref "R25") (pin "1") (pinfunction "1_1") (pintype "unspecified"))
    )
    (net (code "267") (name "SER_02") (class "Default")
      (node (ref "U1") (pin "9") (pinfunction "QH#_9") (pintype "unspecified"))
      (node (ref "U2") (pin "14") (pinfunction "SER_14") (pintype "unspecified"))
    )
    (net (code "268") (name "SER_03") (class "Default")
      (node (ref "U2") (pin "9") (pinfunction "QH#_9") (pintype "unspecified"))
      (node (ref "U3") (pin "14") (pinfunction "SER_14") (pintype "unspecified"))
    )
    (net (code "269") (name "SER_04") (class "Default")
      (node (ref "U3") (pin "9") (pinfunction "QH#_9") (pintype "unspecified"))
      (node (ref "U4") (pin "14") (pinfunction "SER_14") (pintype "unspecified"))
    )
    (net (code "270") (name "SER_05") (class "Default")
      (node (ref "U4") (pin "9") (pinfunction "QH#_9") (pintype "unspecified"))
      (node (ref "U5") (pin "14") (pinfunction "SER_14") (pintype "unspecified"))
    )
    (net (code "271") (name "SER_06") (class "Default")
      (node (ref "U5") (pin "9") (pinfunction "QH#_9") (pintype "unspecified"))
      (node (ref "U6") (pin "14") (pinfunction "SER_14") (pintype "unspecified"))
    )
    (net (code "272") (name "SER_07") (class "Default")
      (node (ref "U6") (pin "9") (pinfunction "QH#_9") (pintype "unspecified"))
      (node (ref "U7") (pin "14") (pinfunction "SER_14") (pintype "unspecified"))
    )
    (net (code "273") (name "SER_08") (class "Default")
      (node (ref "U7") (pin "9") (pinfunction "QH#_9") (pintype "unspecified"))
      (node (ref "U8") (pin "14") (pinfunction "SER_14") (pintype "unspecified"))
    )
    (net (code "274") (name "SER_09") (class "Default")
      (node (ref "U8") (pin "9") (pinfunction "QH#_9") (pintype "unspecified"))
      (node (ref "U9") (pin "14") (pinfunction "SER_14") (pintype "unspecified"))
    )
    (net (code "275") (name "SER_10") (class "Default")
      (node (ref "U10") (pin "14") (pinfunction "SER_14") (pintype "unspecified"))
      (node (ref "U9") (pin "9") (pinfunction "QH#_9") (pintype "unspecified"))
    )
    (net (code "276") (name "SER_11") (class "Default")
      (node (ref "U10") (pin "9") (pinfunction "QH#_9") (pintype "unspecified"))
      (node (ref "U11") (pin "14") (pinfunction "SER_14") (pintype "unspecified"))
    )
    (net (code "277") (name "SER_12") (class "Default")
      (node (ref "U11") (pin "9") (pinfunction "QH#_9") (pintype "unspecified"))
      (node (ref "U12") (pin "14") (pinfunction "SER_14") (pintype "unspecified"))
    )
    (net (code "278") (name "SER_13") (class "Default")
      (node (ref "U12") (pin "9") (pinfunction "QH#_9") (pintype "unspecified"))
      (node (ref "U13") (pin "14") (pinfunction "SER_14") (pintype "unspecified"))
    )
    (net (code "279") (name "SER_14") (class "Default")
      (node (ref "U13") (pin "9") (pinfunction "QH#_9") (pintype "unspecified"))
      (node (ref "U14") (pin "14") (pinfunction "SER_14") (pintype "unspecified"))
    )
    (net (code "280") (name "SER_15") (class "Default")
      (node (ref "U14") (pin "9") (pinfunction "QH#_9") (pintype "unspecified"))
      (node (ref "U15") (pin "14") (pinfunction "SER_14") (pintype "unspecified"))
    )
    (net (code "281") (name "SER_16") (class "Default")
      (node (ref "U15") (pin "9") (pinfunction "QH#_9") (pintype "unspecified"))
      (node (ref "U46") (pin "14") (pinfunction "SER_14") (pintype "unspecified"))
    )
    (net (code "282") (name "SMA_BST") (class "Default")
      (node (ref "C35") (pin "1") (pinfunction "1_1") (pintype "unspecified"))
      (node (ref "U50") (pin "6") (pinfunction "BOOT_6") (pintype "unspecified"))
    )
    (net (code "283") (name "SMA_FB") (class "Default")
      (node (ref "R10") (pin "1") (pinfunction "1_1") (pintype "input"))
      (node (ref "R9") (pin "2") (pinfunction "2_2") (pintype "input"))
      (node (ref "U50") (pin "4") (pinfunction "FB_4") (pintype "unspecified"))
    )
    (net (code "284") (name "SMA_SW") (class "Default")
      (node (ref "C35") (pin "2") (pinfunction "2_2") (pintype "unspecified"))
      (node (ref "L2") (pin "2") (pinfunction "2_2") (pintype "unspecified"))
      (node (ref "U50") (pin "2") (pinfunction "SW_2") (pintype "unspecified"))
    )
    (net (code "285") (name "SRCLK") (class "Default")
      (node (ref "J_test") (pin "11") (pinfunction "11_11") (pintype "unspecified"))
      (node (ref "R13") (pin "2") (pinfunction "2_2") (pintype "unspecified"))
      (node (ref "R41") (pin "1") (pinfunction "1_1") (pintype "input"))
      (node (ref "U1") (pin "11") (pinfunction "SRCLK_11") (pintype "unspecified"))
      (node (ref "U10") (pin "11") (pinfunction "SRCLK_11") (pintype "unspecified"))
      (node (ref "U11") (pin "11") (pinfunction "SRCLK_11") (pintype "unspecified"))
      (node (ref "U12") (pin "11") (pinfunction "SRCLK_11") (pintype "unspecified"))
      (node (ref "U13") (pin "11") (pinfunction "SRCLK_11") (pintype "unspecified"))
      (node (ref "U14") (pin "11") (pinfunction "SRCLK_11") (pintype "unspecified"))
      (node (ref "U15") (pin "11") (pinfunction "SRCLK_11") (pintype "unspecified"))
      (node (ref "U2") (pin "11") (pinfunction "SRCLK_11") (pintype "unspecified"))
      (node (ref "U3") (pin "11") (pinfunction "SRCLK_11") (pintype "unspecified"))
      (node (ref "U4") (pin "11") (pinfunction "SRCLK_11") (pintype "unspecified"))
      (node (ref "U46") (pin "11") (pinfunction "SRCLK_11") (pintype "unspecified"))
      (node (ref "U5") (pin "11") (pinfunction "SRCLK_11") (pintype "unspecified"))
      (node (ref "U6") (pin "11") (pinfunction "SRCLK_11") (pintype "unspecified"))
      (node (ref "U7") (pin "11") (pinfunction "SRCLK_11") (pintype "unspecified"))
      (node (ref "U8") (pin "11") (pinfunction "SRCLK_11") (pintype "unspecified"))
      (node (ref "U9") (pin "11") (pinfunction "SRCLK_11") (pintype "unspecified"))
    )
    (net (code "286") (name "SRCLR#") (class "Default")
      (node (ref "J_ESP_L") (pin "12") (pinfunction "12_12") (pintype "unspecified"))
      (node (ref "J_test") (pin "20") (pinfunction "20_20") (pintype "unspecified"))
      (node (ref "R12") (pin "1") (pinfunction "1_1") (pintype "input"))
      (node (ref "U1") (pin "10") (pinfunction "SRCLR#_10") (pintype "unspecified"))
      (node (ref "U10") (pin "10") (pinfunction "SRCLR#_10") (pintype "unspecified"))
      (node (ref "U11") (pin "10") (pinfunction "SRCLR#_10") (pintype "unspecified"))
      (node (ref "U12") (pin "10") (pinfunction "SRCLR#_10") (pintype "unspecified"))
      (node (ref "U13") (pin "10") (pinfunction "SRCLR#_10") (pintype "unspecified"))
      (node (ref "U14") (pin "10") (pinfunction "SRCLR#_10") (pintype "unspecified"))
      (node (ref "U15") (pin "10") (pinfunction "SRCLR#_10") (pintype "unspecified"))
      (node (ref "U2") (pin "10") (pinfunction "SRCLR#_10") (pintype "unspecified"))
      (node (ref "U3") (pin "10") (pinfunction "SRCLR#_10") (pintype "unspecified"))
      (node (ref "U4") (pin "10") (pinfunction "SRCLR#_10") (pintype "unspecified"))
      (node (ref "U46") (pin "10") (pinfunction "SRCLR#_10") (pintype "unspecified"))
      (node (ref "U5") (pin "10") (pinfunction "SRCLR#_10") (pintype "unspecified"))
      (node (ref "U6") (pin "10") (pinfunction "SRCLR#_10") (pintype "unspecified"))
      (node (ref "U7") (pin "10") (pinfunction "SRCLR#_10") (pintype "unspecified"))
      (node (ref "U8") (pin "10") (pinfunction "SRCLR#_10") (pintype "unspecified"))
      (node (ref "U9") (pin "10") (pinfunction "SRCLR#_10") (pintype "unspecified"))
    )
    (net (code "287") (name "SWITCHED_VBAT") (class "Default")
      (node (ref "C87") (pin "1") (pinfunction "1_1") (pintype "unspecified"))
      (node (ref "R34") (pin "1") (pinfunction "1_1") (pintype "unspecified"))
      (node (ref "R6") (pin "1") (pinfunction "1_1") (pintype "unspecified"))
      (node (ref "SW2") (pin "2") (pinfunction "2_2") (pintype "unspecified"))
      (node (ref "U55") (pin "5") (pinfunction "VDD_5") (pintype "unspecified"))
    )
    (net (code "288") (name "U1.SER") (class "Default")
      (node (ref "J_test") (pin "13") (pinfunction "13_13") (pintype "unspecified"))
      (node (ref "R40") (pin "1") (pinfunction "1_1") (pintype "input"))
      (node (ref "R5") (pin "2") (pinfunction "2_2") (pintype "unspecified"))
      (node (ref "U1") (pin "14") (pinfunction "SER_14") (pintype "unspecified"))
    )
    (net (code "289") (name "USB_CC1") (class "Default")
      (node (ref "J1") (pin "A5") (pinfunction "CC1_A5") (pintype "unspecified"))
      (node (ref "R16") (pin "2") (pinfunction "2_2") (pintype "unspecified"))
    )
    (net (code "290") (name "USB_CC2") (class "Default")
      (node (ref "J1") (pin "B5") (pinfunction "CC2_B5") (pintype "unspecified"))
      (node (ref "R17") (pin "2") (pinfunction "2_2") (pintype "unspecified"))
    )
    (net (code "291") (name "UV_SENSE") (class "Default")
      (node (ref "C88") (pin "1") (pinfunction "1_1") (pintype "input"))
      (node (ref "R34") (pin "2") (pinfunction "2_2") (pintype "unspecified"))
      (node (ref "R35") (pin "1") (pinfunction "1_1") (pintype "input"))
      (node (ref "R36") (pin "2") (pinfunction "2_2") (pintype "unspecified"))
      (node (ref "U55") (pin "3") (pinfunction "INA+_3") (pintype "unspecified"))
    )
    (net (code "292") (name "V5S") (class "Default")
      (node (ref "C89") (pin "1") (pinfunction "1_1") (pintype "unspecified"))
      (node (ref "J_ESP_L") (pin "21") (pinfunction "21_21") (pintype "unspecified"))
      (node (ref "J_test") (pin "10") (pinfunction "10_10") (pintype "unspecified"))
      (node (ref "U52") (pin "3") (pinfunction "CE#_3") (pintype "unspecified"))
      (node (ref "U52") (pin "6") (pinfunction "VOUT_6") (pintype "unspecified"))
    )
    (net (code "293") (name "VBAT") (class "Default")
      (node (ref "C36") (pin "1") (pinfunction "1_1") (pintype "unspecified"))
      (node (ref "C59") (pin "2") (pinfunction "2_2") (pintype "unspecified"))
      (node (ref "C60") (pin "2") (pinfunction "2_2") (pintype "unspecified"))
      (node (ref "C61") (pin "1") (pinfunction "1_1") (pintype "unspecified"))
      (node (ref "C62") (pin "2") (pinfunction "2_2") (pintype "unspecified"))
      (node (ref "C63") (pin "2") (pinfunction "2_2") (pintype "unspecified"))
      (node (ref "C80") (pin "1") (pinfunction "1_1") (pintype "input"))
      (node (ref "C91") (pin "1") (pinfunction "1_1") (pintype "unspecified"))
      (node (ref "J_test") (pin "7") (pinfunction "7_7") (pintype "unspecified"))
      (node (ref "Q1") (pin "1") (pinfunction "S_1") (pintype "unspecified"))
      (node (ref "Q1") (pin "2") (pinfunction "S_2") (pintype "unspecified"))
      (node (ref "Q1") (pin "3") (pinfunction "S_3") (pintype "unspecified"))
      (node (ref "R30") (pin "2") (pinfunction "2_2") (pintype "unspecified"))
      (node (ref "SW2") (pin "3") (pinfunction "3_3") (pintype "unspecified"))
      (node (ref "U49") (pin "10") (pinfunction "VIN_10") (pintype "unspecified"))
      (node (ref "U49") (pin "21") (pinfunction "VIN_21") (pintype "unspecified"))
      (node (ref "U50") (pin "3") (pinfunction "VIN_3") (pintype "unspecified"))
      (node (ref "U51") (pin "12") (pinfunction "VIN_12") (pintype "unspecified"))
      (node (ref "U51") (pin "13") (pinfunction "VIN_13") (pintype "unspecified"))
    )
    (net (code "294") (name "VBAT_DIV") (class "Default")
      (node (ref "C40") (pin "1") (pinfunction "1_1") (pintype "unspecified"))
      (node (ref "R15") (pin "2") (pinfunction "2_2") (pintype "unspecified"))
      (node (ref "R30") (pin "1") (pinfunction "1_1") (pintype "unspecified"))
      (node (ref "U54") (pin "2") (pinfunction "S1_2") (pintype "unspecified"))
    )
    (net (code "295") (name "VCC") (class "Default")
      (node (ref "C32") (pin "2") (pinfunction "2_2") (pintype "input"))
      (node (ref "C44") (pin "2") (pinfunction "2_2") (pintype "input"))
      (node (ref "C45") (pin "2") (pinfunction "2_2") (pintype "input"))
      (node (ref "C46") (pin "2") (pinfunction "2_2") (pintype "input"))
      (node (ref "C47") (pin "2") (pinfunction "2_2") (pintype "input"))
      (node (ref "C48") (pin "2") (pinfunction "2_2") (pintype "input"))
      (node (ref "C49") (pin "2") (pinfunction "2_2") (pintype "input"))
      (node (ref "C50") (pin "2") (pinfunction "2_2") (pintype "input"))
      (node (ref "C51") (pin "2") (pinfunction "2_2") (pintype "input"))
      (node (ref "C52") (pin "2") (pinfunction "2_2") (pintype "input"))
      (node (ref "C53") (pin "2") (pinfunction "2_2") (pintype "input"))
      (node (ref "C54") (pin "2") (pinfunction "2_2") (pintype "input"))
      (node (ref "C55") (pin "2") (pinfunction "2_2") (pintype "input"))
      (node (ref "C56") (pin "2") (pinfunction "2_2") (pintype "input"))
      (node (ref "C57") (pin "2") (pinfunction "2_2") (pintype "input"))
      (node (ref "C58") (pin "2") (pinfunction "2_2") (pintype "input"))
      (node (ref "C72") (pin "1") (pinfunction "1_1") (pintype "unspecified"))
      (node (ref "C74") (pin "1") (pinfunction "1_1") (pintype "input"))
      (node (ref "C75") (pin "1") (pinfunction "1_1") (pintype "input"))
      (node (ref "C76") (pin "1") (pinfunction "1_1") (pintype "input"))
      (node (ref "C77") (pin "1") (pinfunction "1_1") (pintype "input"))
      (node (ref "C78") (pin "1") (pinfunction "1_1") (pintype "input"))
      (node (ref "C79") (pin "1") (pinfunction "1_1") (pintype "input"))
      (node (ref "J_test") (pin "1") (pinfunction "1_1") (pintype "unspecified"))
      (node (ref "L1") (pin "2") (pinfunction "2_2") (pintype "unspecified"))
      (node (ref "R7") (pin "1") (pinfunction "1_1") (pintype "unspecified"))
      (node (ref "U16") (pin "9") (pinfunction "COM_9") (pintype "unspecified"))
      (node (ref "U17") (pin "9") (pinfunction "COM_9") (pintype "unspecified"))
      (node (ref "U18") (pin "9") (pinfunction "COM_9") (pintype "unspecified"))
      (node (ref "U19") (pin "9") (pinfunction "COM_9") (pintype "unspecified"))
      (node (ref "U20") (pin "9") (pinfunction "COM_9") (pintype "unspecified"))
      (node (ref "U21") (pin "9") (pinfunction "COM_9") (pintype "unspecified"))
      (node (ref "U22") (pin "9") (pinfunction "COM_9") (pintype "unspecified"))
      (node (ref "U23") (pin "9") (pinfunction "COM_9") (pintype "unspecified"))
      (node (ref "U24") (pin "9") (pinfunction "COM_9") (pintype "unspecified"))
      (node (ref "U25") (pin "9") (pinfunction "COM_9") (pintype "unspecified"))
      (node (ref "U26") (pin "9") (pinfunction "COM_9") (pintype "unspecified"))
      (node (ref "U27") (pin "9") (pinfunction "COM_9") (pintype "unspecified"))
      (node (ref "U28") (pin "9") (pinfunction "COM_9") (pintype "unspecified"))
      (node (ref "U29") (pin "9") (pinfunction "COM_9") (pintype "unspecified"))
      (node (ref "U30") (pin "9") (pinfunction "COM_9") (pintype "unspecified"))
      (node (ref "U31") (pin "1") (pinfunction "1_1") (pintype "unspecified"))
      (node (ref "U31") (pin "10") (pinfunction "10_10") (pintype "unspecified"))
      (node (ref "U31") (pin "5") (pinfunction "5_5") (pintype "unspecified"))
      (node (ref "U31") (pin "7") (pinfunction "7_7") (pintype "unspecified"))
      (node (ref "U32") (pin "1") (pinfunction "1_1") (pintype "unspecified"))
      (node (ref "U32") (pin "10") (pinfunction "10_10") (pintype "unspecified"))
      (node (ref "U32") (pin "5") (pinfunction "5_5") (pintype "unspecified"))
      (node (ref "U32") (pin "7") (pinfunction "7_7") (pintype "unspecified"))
      (node (ref "U33") (pin "1") (pinfunction "1_1") (pintype "unspecified"))
      (node (ref "U33") (pin "10") (pinfunction "10_10") (pintype "unspecified"))
      (node (ref "U33") (pin "5") (pinfunction "5_5") (pintype "unspecified"))
      (node (ref "U33") (pin "7") (pinfunction "7_7") (pintype "unspecified"))
      (node (ref "U34") (pin "1") (pinfunction "1_1") (pintype "unspecified"))
      (node (ref "U34") (pin "10") (pinfunction "10_10") (pintype "unspecified"))
      (node (ref "U34") (pin "5") (pinfunction "5_5") (pintype "unspecified"))
      (node (ref "U34") (pin "7") (pinfunction "7_7") (pintype "unspecified"))
      (node (ref "U35") (pin "1") (pinfunction "1_1") (pintype "unspecified"))
      (node (ref "U35") (pin "10") (pinfunction "10_10") (pintype "unspecified"))
      (node (ref "U35") (pin "5") (pinfunction "5_5") (pintype "unspecified"))
      (node (ref "U35") (pin "7") (pinfunction "7_7") (pintype "unspecified"))
      (node (ref "U36") (pin "1") (pinfunction "1_1") (pintype "unspecified"))
      (node (ref "U36") (pin "10") (pinfunction "10_10") (pintype "unspecified"))
      (node (ref "U36") (pin "5") (pinfunction "5_5") (pintype "unspecified"))
      (node (ref "U36") (pin "7") (pinfunction "7_7") (pintype "unspecified"))
      (node (ref "U37") (pin "1") (pinfunction "1_1") (pintype "unspecified"))
      (node (ref "U37") (pin "10") (pinfunction "10_10") (pintype "unspecified"))
      (node (ref "U37") (pin "5") (pinfunction "5_5") (pintype "unspecified"))
      (node (ref "U37") (pin "7") (pinfunction "7_7") (pintype "unspecified"))
      (node (ref "U38") (pin "1") (pinfunction "1_1") (pintype "unspecified"))
      (node (ref "U38") (pin "10") (pinfunction "10_10") (pintype "unspecified"))
      (node (ref "U38") (pin "5") (pinfunction "5_5") (pintype "unspecified"))
      (node (ref "U38") (pin "7") (pinfunction "7_7") (pintype "unspecified"))
      (node (ref "U39") (pin "1") (pinfunction "1_1") (pintype "unspecified"))
      (node (ref "U39") (pin "10") (pinfunction "10_10") (pintype "unspecified"))
      (node (ref "U39") (pin "5") (pinfunction "5_5") (pintype "unspecified"))
      (node (ref "U39") (pin "7") (pinfunction "7_7") (pintype "unspecified"))
      (node (ref "U40") (pin "1") (pinfunction "1_1") (pintype "unspecified"))
      (node (ref "U40") (pin "10") (pinfunction "10_10") (pintype "unspecified"))
      (node (ref "U40") (pin "5") (pinfunction "5_5") (pintype "unspecified"))
      (node (ref "U40") (pin "7") (pinfunction "7_7") (pintype "unspecified"))
      (node (ref "U41") (pin "1") (pinfunction "1_1") (pintype "unspecified"))
      (node (ref "U41") (pin "10") (pinfunction "10_10") (pintype "unspecified"))
      (node (ref "U41") (pin "5") (pinfunction "5_5") (pintype "unspecified"))
      (node (ref "U41") (pin "7") (pinfunction "7_7") (pintype "unspecified"))
      (node (ref "U42") (pin "1") (pinfunction "1_1") (pintype "unspecified"))
      (node (ref "U42") (pin "10") (pinfunction "10_10") (pintype "unspecified"))
      (node (ref "U42") (pin "5") (pinfunction "5_5") (pintype "unspecified"))
      (node (ref "U42") (pin "7") (pinfunction "7_7") (pintype "unspecified"))
      (node (ref "U43") (pin "1") (pinfunction "1_1") (pintype "unspecified"))
      (node (ref "U43") (pin "10") (pinfunction "10_10") (pintype "unspecified"))
      (node (ref "U43") (pin "5") (pinfunction "5_5") (pintype "unspecified"))
      (node (ref "U43") (pin "7") (pinfunction "7_7") (pintype "unspecified"))
      (node (ref "U44") (pin "1") (pinfunction "1_1") (pintype "unspecified"))
      (node (ref "U44") (pin "10") (pinfunction "10_10") (pintype "unspecified"))
      (node (ref "U44") (pin "5") (pinfunction "5_5") (pintype "unspecified"))
      (node (ref "U44") (pin "7") (pinfunction "7_7") (pintype "unspecified"))
      (node (ref "U45") (pin "1") (pinfunction "1_1") (pintype "unspecified"))
      (node (ref "U45") (pin "10") (pinfunction "10_10") (pintype "unspecified"))
      (node (ref "U45") (pin "5") (pinfunction "5_5") (pintype "unspecified"))
      (node (ref "U45") (pin "7") (pinfunction "7_7") (pintype "unspecified"))
      (node (ref "U47") (pin "9") (pinfunction "COM_9") (pintype "unspecified"))
      (node (ref "U48") (pin "1") (pinfunction "1_1") (pintype "unspecified"))
      (node (ref "U48") (pin "10") (pinfunction "10_10") (pintype "unspecified"))
      (node (ref "U48") (pin "5") (pinfunction "5_5") (pintype "unspecified"))
      (node (ref "U48") (pin "7") (pinfunction "7_7") (pintype "unspecified"))
    )
    (net (code "296") (name "VCCS") (class "Default")
      (node (ref "C41") (pin "1") (pinfunction "1_1") (pintype "unspecified"))
      (node (ref "J_test") (pin "3") (pinfunction "3_3") (pintype "unspecified"))
      (node (ref "L2") (pin "1") (pinfunction "1_1") (pintype "unspecified"))
      (node (ref "R18") (pin "1") (pinfunction "1_1") (pintype "unspecified"))
      (node (ref "R9") (pin "1") (pinfunction "1_1") (pintype "input"))
      (node (ref "U31") (pin "12") (pinfunction "12_12") (pintype "unspecified"))
      (node (ref "U32") (pin "12") (pinfunction "12_12") (pintype "unspecified"))
      (node (ref "U33") (pin "12") (pinfunction "12_12") (pintype "unspecified"))
      (node (ref "U34") (pin "12") (pinfunction "12_12") (pintype "unspecified"))
      (node (ref "U35") (pin "12") (pinfunction "12_12") (pintype "unspecified"))
      (node (ref "U36") (pin "12") (pinfunction "12_12") (pintype "unspecified"))
      (node (ref "U37") (pin "12") (pinfunction "12_12") (pintype "unspecified"))
      (node (ref "U38") (pin "12") (pinfunction "12_12") (pintype "unspecified"))
      (node (ref "U39") (pin "12") (pinfunction "12_12") (pintype "unspecified"))
      (node (ref "U40") (pin "12") (pinfunction "12_12") (pintype "unspecified"))
      (node (ref "U41") (pin "12") (pinfunction "12_12") (pintype "unspecified"))
      (node (ref "U42") (pin "12") (pinfunction "12_12") (pintype "unspecified"))
      (node (ref "U43") (pin "12") (pinfunction "12_12") (pintype "unspecified"))
      (node (ref "U44") (pin "12") (pinfunction "12_12") (pintype "unspecified"))
      (node (ref "U45") (pin "12") (pinfunction "12_12") (pintype "unspecified"))
      (node (ref "U48") (pin "12") (pinfunction "12_12") (pintype "unspecified"))
    )
    (net (code "297") (name "VCC_LOGIC") (class "Default")
      (node (ref "C1") (pin "1") (pinfunction "1_1") (pintype "unspecified"))
      (node (ref "C10") (pin "1") (pinfunction "1_1") (pintype "unspecified"))
      (node (ref "C11") (pin "1") (pinfunction "1_1") (pintype "unspecified"))
      (node (ref "C12") (pin "1") (pinfunction "1_1") (pintype "unspecified"))
      (node (ref "C13") (pin "1") (pinfunction "1_1") (pintype "unspecified"))
      (node (ref "C14") (pin "1") (pinfunction "1_1") (pintype "unspecified"))
      (node (ref "C15") (pin "1") (pinfunction "1_1") (pintype "unspecified"))
      (node (ref "C2") (pin "1") (pinfunction "1_1") (pintype "unspecified"))
      (node (ref "C3") (pin "1") (pinfunction "1_1") (pintype "unspecified"))
      (node (ref "C31") (pin "1") (pinfunction "1_1") (pintype "unspecified"))
      (node (ref "C4") (pin "1") (pinfunction "1_1") (pintype "unspecified"))
      (node (ref "C5") (pin "1") (pinfunction "1_1") (pintype "unspecified"))
      (node (ref "C6") (pin "1") (pinfunction "1_1") (pintype "unspecified"))
      (node (ref "C7") (pin "1") (pinfunction "1_1") (pintype "unspecified"))
      (node (ref "C8") (pin "1") (pinfunction "1_1") (pintype "unspecified"))
      (node (ref "C86") (pin "1") (pinfunction "1_1") (pintype "input"))
      (node (ref "C9") (pin "1") (pinfunction "1_1") (pintype "unspecified"))
      (node (ref "J_test") (pin "5") (pinfunction "5_5") (pintype "unspecified"))
      (node (ref "R11") (pin "2") (pinfunction "2_2") (pintype "input"))
      (node (ref "R12") (pin "2") (pinfunction "2_2") (pintype "input"))
      (node (ref "R19") (pin "1") (pinfunction "1_1") (pintype "unspecified"))
      (node (ref "R25") (pin "2") (pinfunction "2_2") (pintype "unspecified"))
      (node (ref "U1") (pin "16") (pinfunction "VCC_16") (pintype "unspecified"))
      (node (ref "U10") (pin "16") (pinfunction "VCC_16") (pintype "unspecified"))
      (node (ref "U11") (pin "16") (pinfunction "VCC_16") (pintype "unspecified"))
      (node (ref "U12") (pin "16") (pinfunction "VCC_16") (pintype "unspecified"))
      (node (ref "U13") (pin "16") (pinfunction "VCC_16") (pintype "unspecified"))
      (node (ref "U14") (pin "16") (pinfunction "VCC_16") (pintype "unspecified"))
      (node (ref "U15") (pin "16") (pinfunction "VCC_16") (pintype "unspecified"))
      (node (ref "U2") (pin "16") (pinfunction "VCC_16") (pintype "unspecified"))
      (node (ref "U3") (pin "16") (pinfunction "VCC_16") (pintype "unspecified"))
      (node (ref "U4") (pin "16") (pinfunction "VCC_16") (pintype "unspecified"))
      (node (ref "U46") (pin "16") (pinfunction "VCC_16") (pintype "unspecified"))
      (node (ref "U5") (pin "16") (pinfunction "VCC_16") (pintype "unspecified"))
      (node (ref "U6") (pin "16") (pinfunction "VCC_16") (pintype "unspecified"))
      (node (ref "U7") (pin "16") (pinfunction "VCC_16") (pintype "unspecified"))
      (node (ref "U8") (pin "16") (pinfunction "VCC_16") (pintype "unspecified"))
      (node (ref "U9") (pin "16") (pinfunction "VCC_16") (pintype "unspecified"))
    )
    (net (code "298") (name "VIN_C") (class "Default")
      (node (ref "C65") (pin "1") (pinfunction "1_1") (pintype "unspecified"))
      (node (ref "C66") (pin "1") (pinfunction "1_1") (pintype "unspecified"))
      (node (ref "J1") (pin "A9") (pinfunction "VBUS_A9") (pintype "unspecified"))
      (node (ref "J1") (pin "B9") (pinfunction "VBUS_B9") (pintype "unspecified"))
      (node (ref "J_test") (pin "8") (pinfunction "8_8") (pintype "unspecified"))
      (node (ref "L4") (pin "2") (pinfunction "2_2") (pintype "unspecified"))
      (node (ref "R23") (pin "2") (pinfunction "2_2") (pintype "unspecified"))
    )
    (net (code "299") (name "unconnected-(J_ESP_L-Pad3)") (class "Default")
      (node (ref "J_ESP_L") (pin "3") (pinfunction "3_3") (pintype "unspecified+no_connect"))
    )
    (net (code "300") (name "unconnected-(J_ESP_L-Pad7)") (class "Default")
      (node (ref "J_ESP_L") (pin "7") (pinfunction "7_7") (pintype "unspecified+no_connect"))
    )
    (net (code "301") (name "unconnected-(J_ESP_L-Pad8)") (class "Default")
      (node (ref "J_ESP_L") (pin "8") (pinfunction "8_8") (pintype "unspecified+no_connect"))
    )
    (net (code "302") (name "unconnected-(J_ESP_L-Pad9)") (class "Default")
      (node (ref "J_ESP_L") (pin "9") (pinfunction "9_9") (pintype "unspecified+no_connect"))
    )
    (net (code "303") (name "unconnected-(J_ESP_L-Pad10)") (class "Default")
      (node (ref "J_ESP_L") (pin "10") (pinfunction "10_10") (pintype "unspecified+no_connect"))
    )
    (net (code "304") (name "unconnected-(J_ESP_L-Pad11)") (class "Default")
      (node (ref "J_ESP_L") (pin "11") (pinfunction "11_11") (pintype "unspecified+no_connect"))
    )
    (net (code "305") (name "unconnected-(J_ESP_L-Pad13)") (class "Default")
      (node (ref "J_ESP_L") (pin "13") (pinfunction "13_13") (pintype "unspecified+no_connect"))
    )
    (net (code "306") (name "unconnected-(J_ESP_L-Pad14)") (class "Default")
      (node (ref "J_ESP_L") (pin "14") (pinfunction "14_14") (pintype "unspecified+no_connect"))
    )
    (net (code "307") (name "unconnected-(J_ESP_R-Pad2)") (class "Default")
      (node (ref "J_ESP_R") (pin "2") (pinfunction "2_2") (pintype "unspecified+no_connect"))
    )
    (net (code "308") (name "unconnected-(J_ESP_R-Pad3)") (class "Default")
      (node (ref "J_ESP_R") (pin "3") (pinfunction "3_3") (pintype "unspecified+no_connect"))
    )
    (net (code "309") (name "unconnected-(J_ESP_R-Pad4)") (class "Default")
      (node (ref "J_ESP_R") (pin "4") (pinfunction "4_4") (pintype "unspecified+no_connect"))
    )
    (net (code "310") (name "unconnected-(J_ESP_R-Pad5)") (class "Default")
      (node (ref "J_ESP_R") (pin "5") (pinfunction "5_5") (pintype "unspecified+no_connect"))
    )
    (net (code "311") (name "unconnected-(J_ESP_R-Pad6)") (class "Default")
      (node (ref "J_ESP_R") (pin "6") (pinfunction "6_6") (pintype "unspecified+no_connect"))
    )
    (net (code "312") (name "unconnected-(J_ESP_R-Pad7)") (class "Default")
      (node (ref "J_ESP_R") (pin "7") (pinfunction "7_7") (pintype "unspecified+no_connect"))
    )
    (net (code "313") (name "unconnected-(J_ESP_R-Pad8)") (class "Default")
      (node (ref "J_ESP_R") (pin "8") (pinfunction "8_8") (pintype "unspecified+no_connect"))
    )
    (net (code "314") (name "unconnected-(J_ESP_R-Pad9)") (class "Default")
      (node (ref "J_ESP_R") (pin "9") (pinfunction "9_9") (pintype "unspecified+no_connect"))
    )
    (net (code "315") (name "unconnected-(J_ESP_R-Pad10)") (class "Default")
      (node (ref "J_ESP_R") (pin "10") (pinfunction "10_10") (pintype "unspecified+no_connect"))
    )
    (net (code "316") (name "unconnected-(J_ESP_R-Pad11)") (class "Default")
      (node (ref "J_ESP_R") (pin "11") (pinfunction "11_11") (pintype "unspecified+no_connect"))
    )
    (net (code "317") (name "unconnected-(J_ESP_R-Pad12)") (class "Default")
      (node (ref "J_ESP_R") (pin "12") (pinfunction "12_12") (pintype "unspecified+no_connect"))
    )
    (net (code "318") (name "unconnected-(J_ESP_R-Pad13)") (class "Default")
      (node (ref "J_ESP_R") (pin "13") (pinfunction "13_13") (pintype "unspecified+no_connect"))
    )
    (net (code "319") (name "unconnected-(J_ESP_R-Pad14)") (class "Default")
      (node (ref "J_ESP_R") (pin "14") (pinfunction "14_14") (pintype "unspecified+no_connect"))
    )
    (net (code "320") (name "unconnected-(J_ESP_R-Pad15)") (class "Default")
      (node (ref "J_ESP_R") (pin "15") (pinfunction "15_15") (pintype "unspecified+no_connect"))
    )
    (net (code "321") (name "unconnected-(J_ESP_R-Pad16)") (class "Default")
      (node (ref "J_ESP_R") (pin "16") (pinfunction "16_16") (pintype "unspecified+no_connect"))
    )
    (net (code "322") (name "unconnected-(J_ESP_R-Pad17)") (class "Default")
      (node (ref "J_ESP_R") (pin "17") (pinfunction "17_17") (pintype "unspecified+no_connect"))
    )
    (net (code "323") (name "unconnected-(J_ESP_R-Pad18)") (class "Default")
      (node (ref "J_ESP_R") (pin "18") (pinfunction "18_18") (pintype "unspecified+no_connect"))
    )
    (net (code "324") (name "unconnected-(J_ESP_R-Pad19)") (class "Default")
      (node (ref "J_ESP_R") (pin "19") (pinfunction "19_19") (pintype "unspecified+no_connect"))
    )
    (net (code "325") (name "unconnected-(J_ESP_R-Pad20)") (class "Default")
      (node (ref "J_ESP_R") (pin "20") (pinfunction "20_20") (pintype "unspecified+no_connect"))
    )
    (net (code "326") (name "unconnected-(J_ESP_R-Pad21)") (class "Default")
      (node (ref "J_ESP_R") (pin "21") (pinfunction "21_21") (pintype "unspecified+no_connect"))
    )
    (net (code "327") (name "unconnected-(J_ESP_R-Pad22)") (class "Default")
      (node (ref "J_ESP_R") (pin "22") (pinfunction "22_22") (pintype "unspecified+no_connect"))
    )
    (net (code "328") (name "unconnected-(SW1-Pad2)") (class "Default")
      (node (ref "SW1") (pin "2") (pinfunction "2_2") (pintype "unspecified+no_connect"))
    )
    (net (code "329") (name "unconnected-(SW1-Pad4)") (class "Default")
      (node (ref "SW1") (pin "4") (pinfunction "4_4") (pintype "unspecified+no_connect"))
    )
    (net (code "330") (name "unconnected-(U1-QH-Pad7)") (class "Default")
      (node (ref "U1") (pin "7") (pinfunction "QH_7") (pintype "unspecified+no_connect"))
    )
    (net (code "331") (name "unconnected-(U2-QH-Pad7)") (class "Default")
      (node (ref "U2") (pin "7") (pinfunction "QH_7") (pintype "unspecified+no_connect"))
    )
    (net (code "332") (name "unconnected-(U3-QH-Pad7)") (class "Default")
      (node (ref "U3") (pin "7") (pinfunction "QH_7") (pintype "unspecified+no_connect"))
    )
    (net (code "333") (name "unconnected-(U4-QH-Pad7)") (class "Default")
      (node (ref "U4") (pin "7") (pinfunction "QH_7") (pintype "unspecified+no_connect"))
    )
    (net (code "334") (name "unconnected-(U5-QH-Pad7)") (class "Default")
      (node (ref "U5") (pin "7") (pinfunction "QH_7") (pintype "unspecified+no_connect"))
    )
    (net (code "335") (name "unconnected-(U6-QH-Pad7)") (class "Default")
      (node (ref "U6") (pin "7") (pinfunction "QH_7") (pintype "unspecified+no_connect"))
    )
    (net (code "336") (name "unconnected-(U7-QH-Pad7)") (class "Default")
      (node (ref "U7") (pin "7") (pinfunction "QH_7") (pintype "unspecified+no_connect"))
    )
    (net (code "337") (name "unconnected-(U8-QH-Pad7)") (class "Default")
      (node (ref "U8") (pin "7") (pinfunction "QH_7") (pintype "unspecified+no_connect"))
    )
    (net (code "338") (name "unconnected-(U9-QH-Pad7)") (class "Default")
      (node (ref "U9") (pin "7") (pinfunction "QH_7") (pintype "unspecified+no_connect"))
    )
    (net (code "339") (name "unconnected-(U10-QH-Pad7)") (class "Default")
      (node (ref "U10") (pin "7") (pinfunction "QH_7") (pintype "unspecified+no_connect"))
    )
    (net (code "340") (name "unconnected-(U11-QH-Pad7)") (class "Default")
      (node (ref "U11") (pin "7") (pinfunction "QH_7") (pintype "unspecified+no_connect"))
    )
    (net (code "341") (name "unconnected-(U12-QH-Pad7)") (class "Default")
      (node (ref "U12") (pin "7") (pinfunction "QH_7") (pintype "unspecified+no_connect"))
    )
    (net (code "342") (name "unconnected-(U13-QH-Pad7)") (class "Default")
      (node (ref "U13") (pin "7") (pinfunction "QH_7") (pintype "unspecified+no_connect"))
    )
    (net (code "343") (name "unconnected-(U14-QH-Pad7)") (class "Default")
      (node (ref "U14") (pin "7") (pinfunction "QH_7") (pintype "unspecified+no_connect"))
    )
    (net (code "344") (name "unconnected-(U15-QH-Pad7)") (class "Default")
      (node (ref "U15") (pin "7") (pinfunction "QH_7") (pintype "unspecified+no_connect"))
    )
    (net (code "345") (name "unconnected-(U46-QH-Pad7)") (class "Default")
      (node (ref "U46") (pin "7") (pinfunction "QH_7") (pintype "unspecified+no_connect"))
    )
    (net (code "346") (name "unconnected-(U51-FB2-Pad6)") (class "Default")
      (node (ref "U51") (pin "6") (pinfunction "FB2_6") (pintype "unspecified+no_connect"))
    )
    (net (code "347") (name "unconnected-(U51-PG-Pad2)") (class "Default")
      (node (ref "U51") (pin "2") (pinfunction "PG_2") (pintype "unspecified+no_connect"))
    )
    (net (code "348") (name "unconnected-(U53-BAT_STAT-Pad5)") (class "Default")
      (node (ref "U53") (pin "5") (pinfunction "BAT_STAT_5") (pintype "unspecified+no_connect"))
    )
    (net (code "349") (name "unconnected-(U53-CON_SEL-Pad10)") (class "Default")
      (node (ref "U53") (pin "10") (pinfunction "CON_SEL_10") (pintype "unspecified+no_connect"))
    )
    (net (code "350") (name "unconnected-(U53-DM-Pad1)") (class "Default")
      (node (ref "U53") (pin "1") (pinfunction "DM_1") (pintype "unspecified+no_connect"))
    )
    (net (code "351") (name "unconnected-(U53-DP-Pad2)") (class "Default")
      (node (ref "U53") (pin "2") (pinfunction "DP_2") (pintype "unspecified+no_connect"))
    )
    (net (code "352") (name "unconnected-(U53-VBATM-Pad23)") (class "Default")
      (node (ref "U53") (pin "23") (pinfunction "VBATM_23") (pintype "unspecified+no_connect"))
    )
    (net (code "353") (name "unconnected-(U53-VBAT_GND-Pad24)") (class "Default")
      (node (ref "U53") (pin "24") (pinfunction "VBAT_GND_24") (pintype "unspecified+no_connect"))
    )
    (net (code "354") (name "unconnected-(U53-VIN_OVSET-Pad9)") (class "Default")
      (node (ref "U53") (pin "9") (pinfunction "VIN_OVSET_9") (pintype "unspecified+no_connect"))
    )
    (net (code "355") (name "unconnected-(U55-OUTB-Pad6)") (class "Default")
      (node (ref "U55") (pin "6") (pinfunction "OUTB_6") (pintype "unspecified+no_connect"))
    )
  )
)
